# STM32-PROX.net
KiCad netlist of a schematic drawn in EAGLE
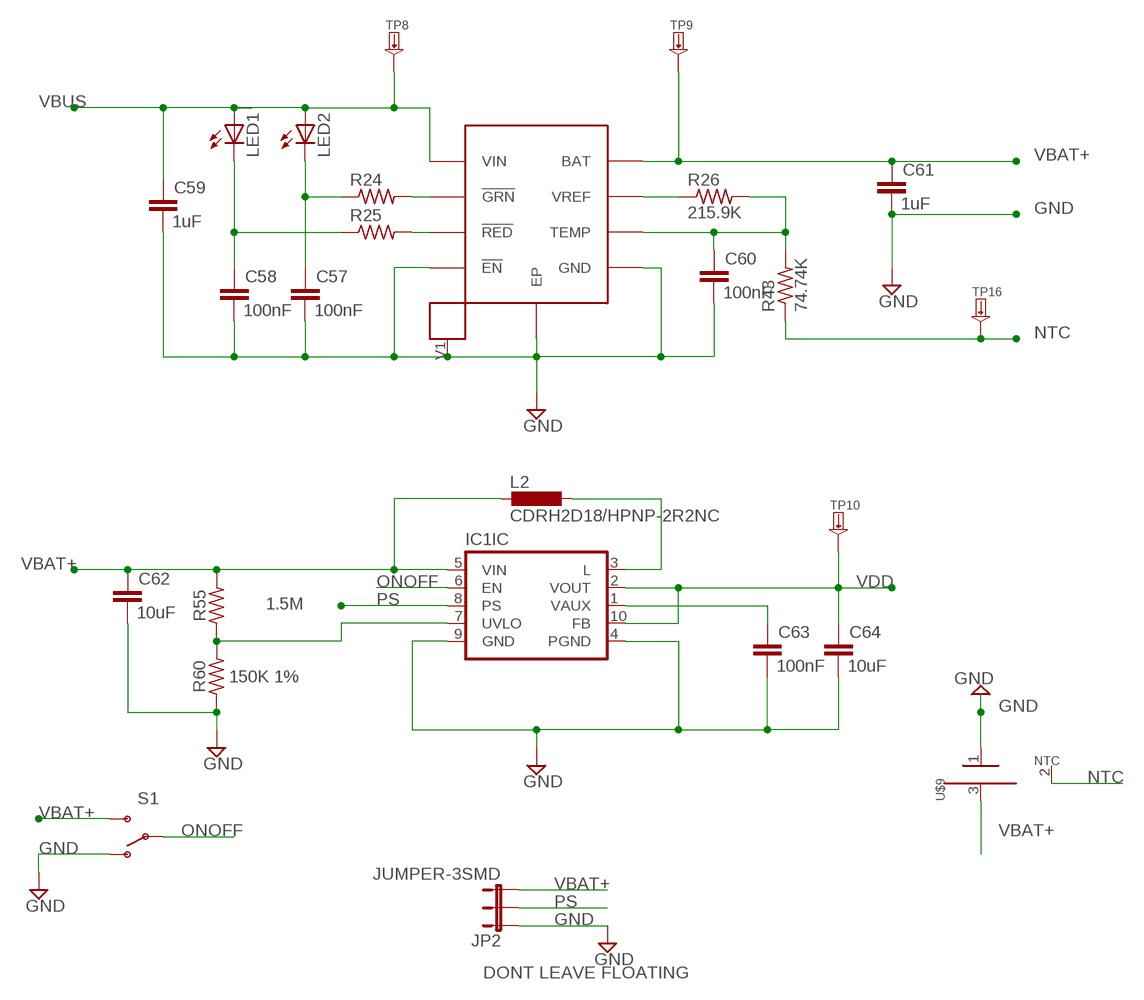
[diagram p0: schematic, sheet 1]
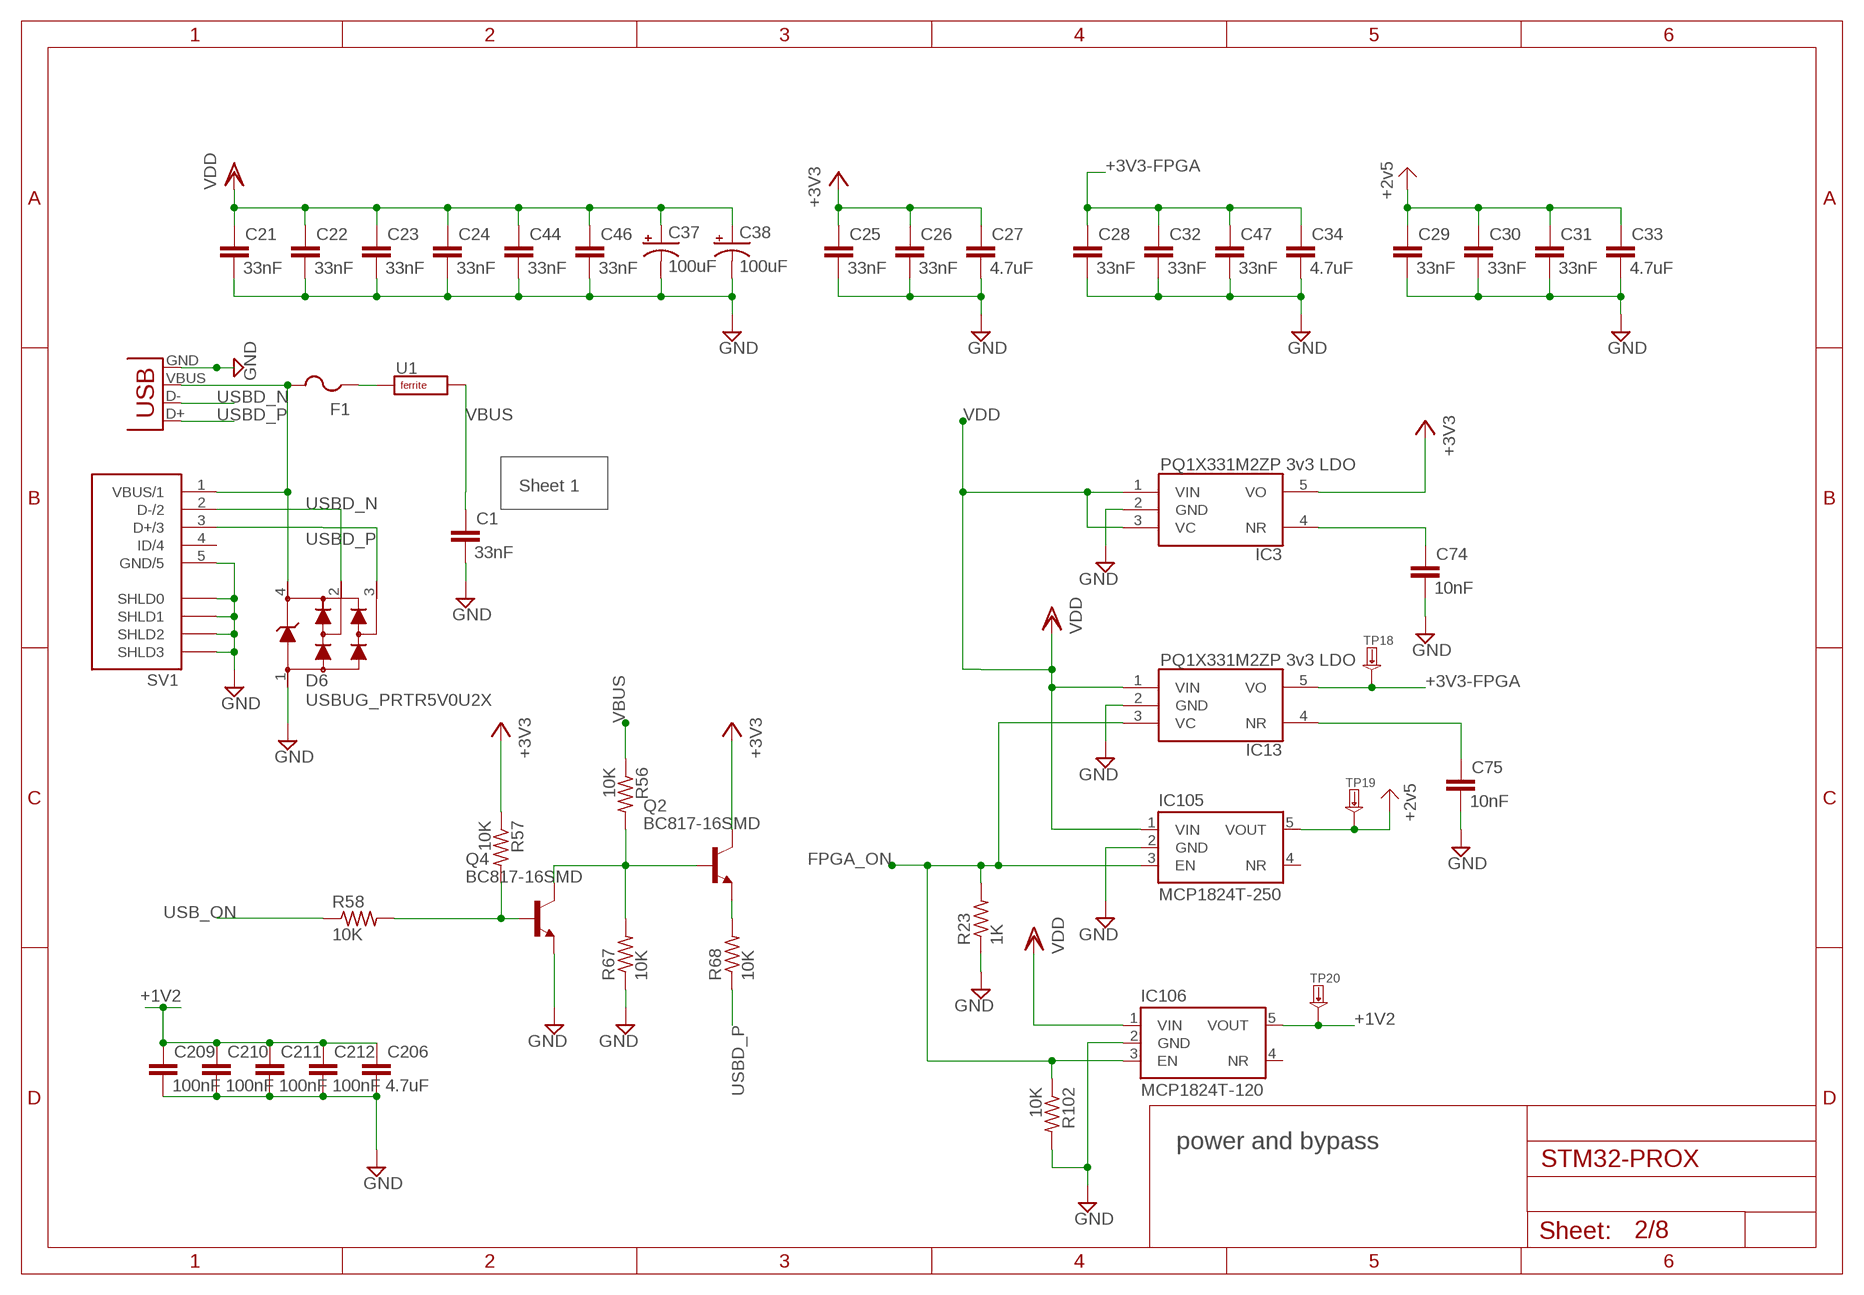
[diagram p1: schematic, sheet 2]
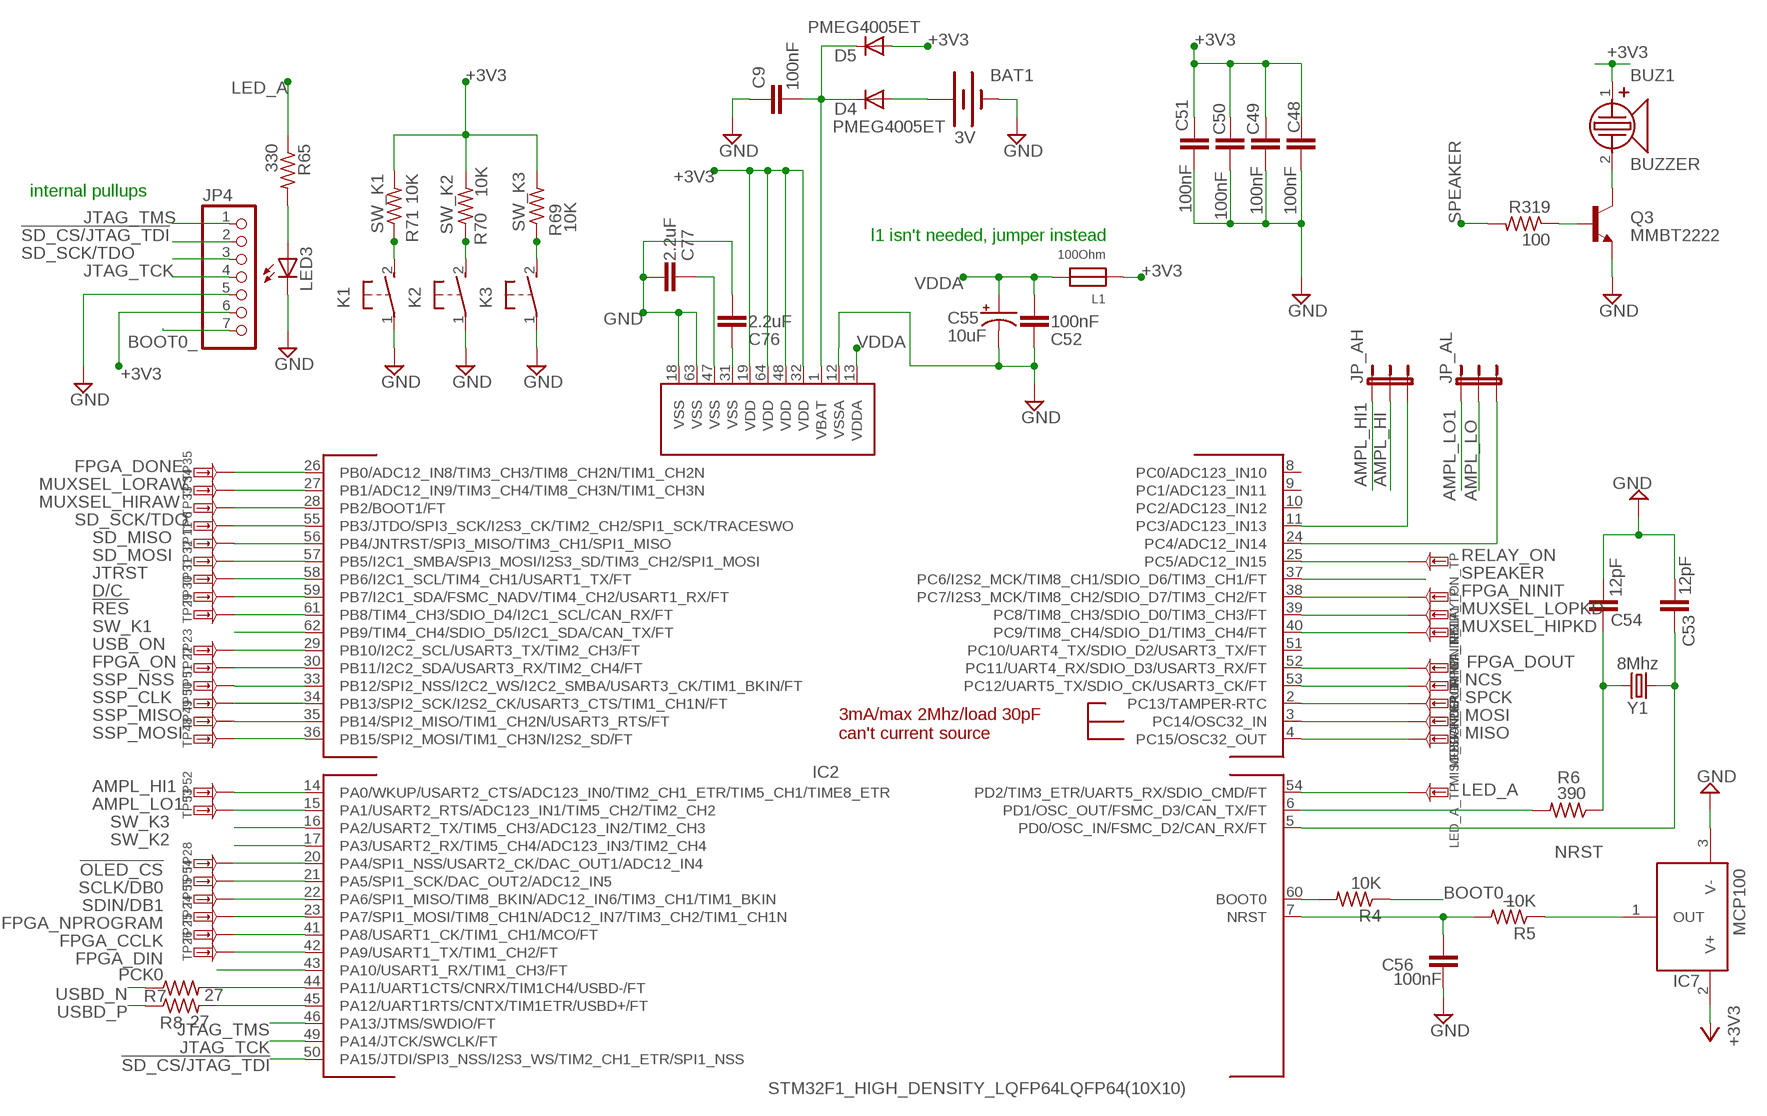
[diagram p2: schematic, sheet 3]
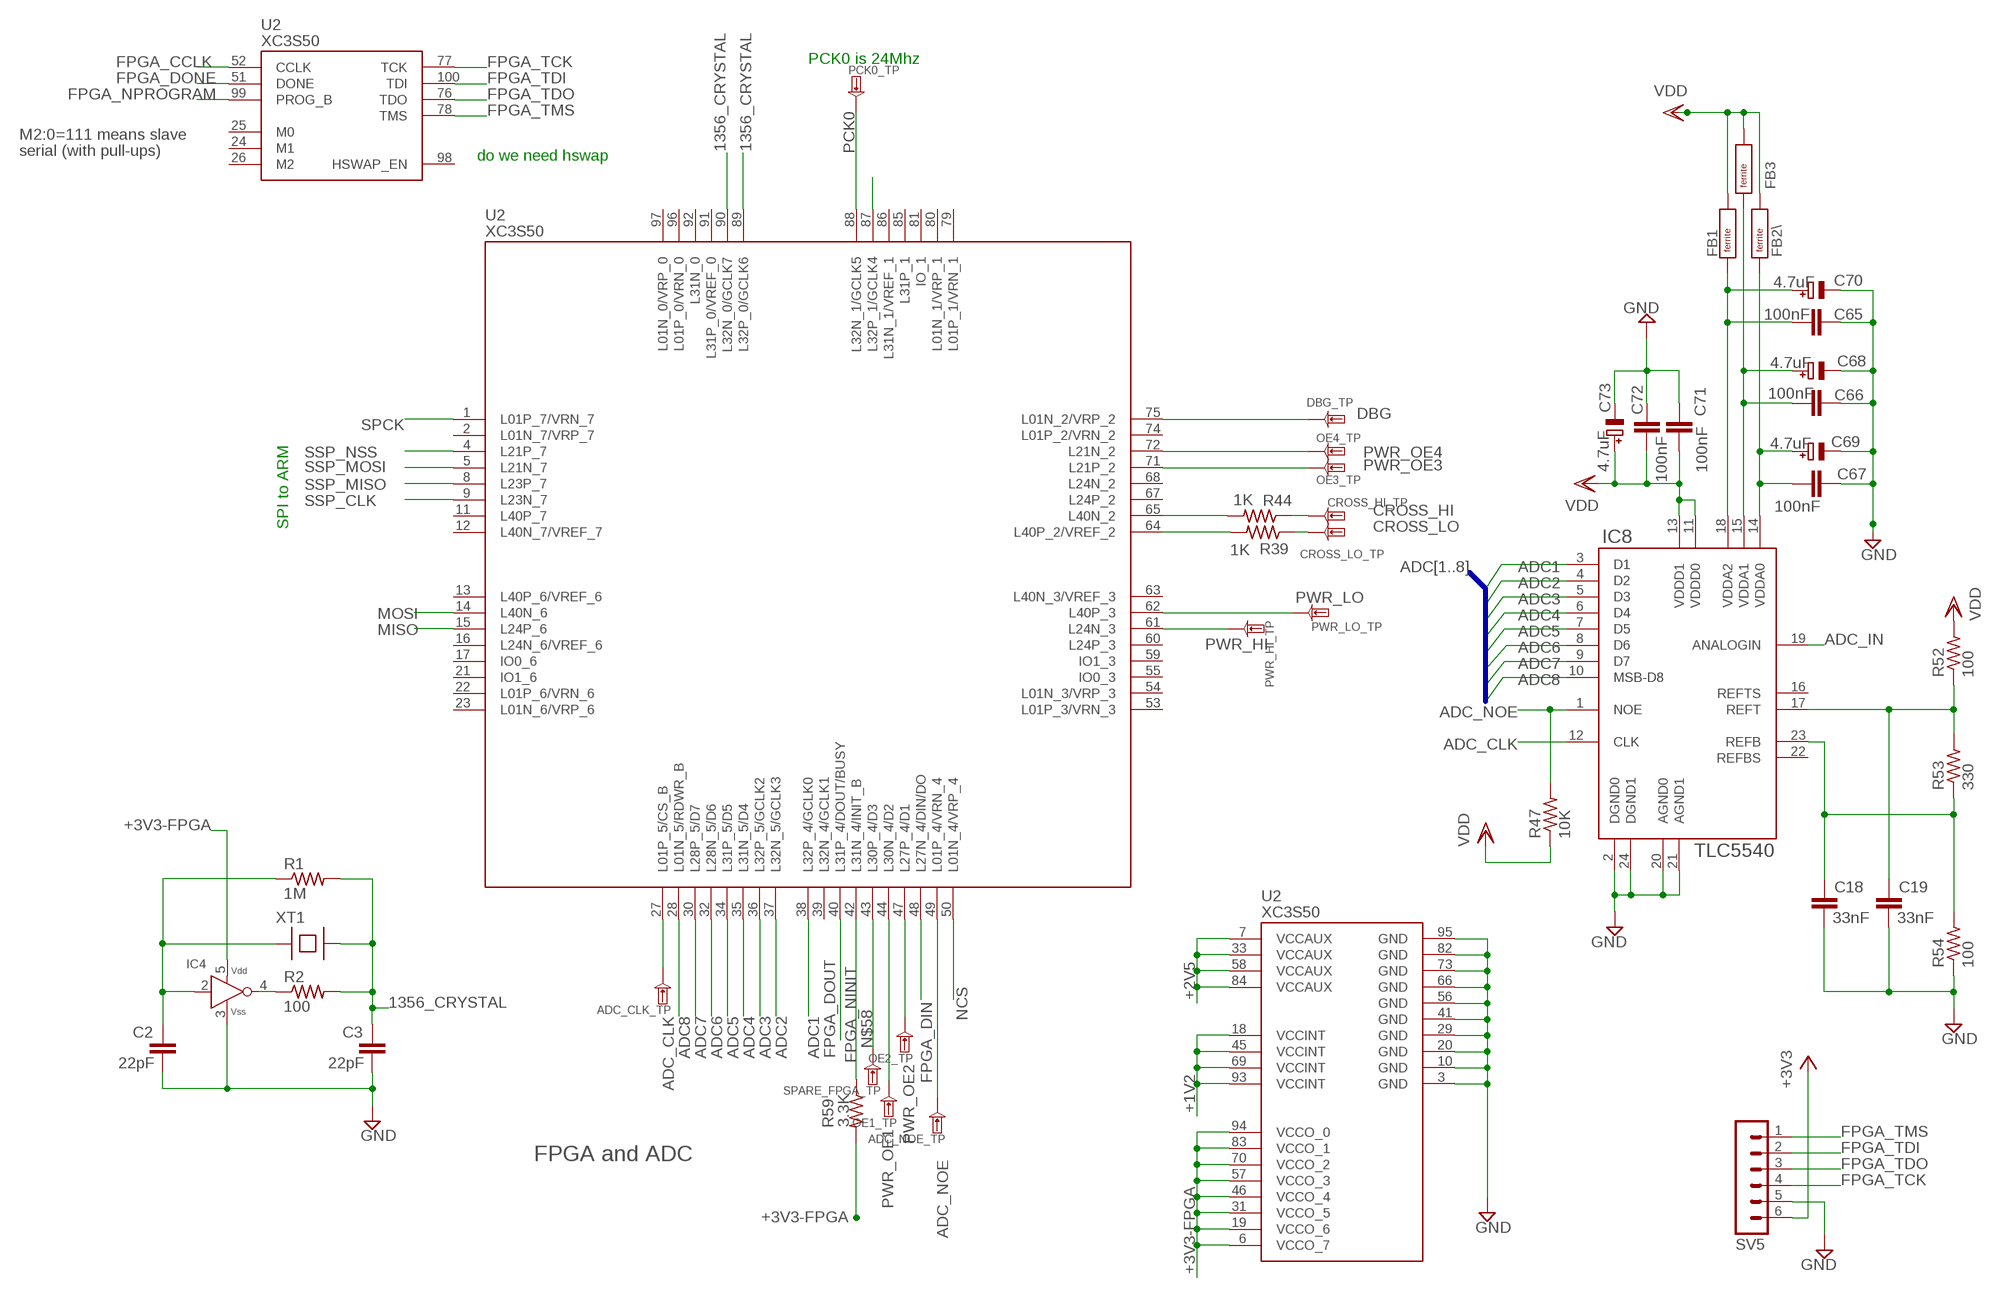
[diagram p3: schematic, sheet 4]
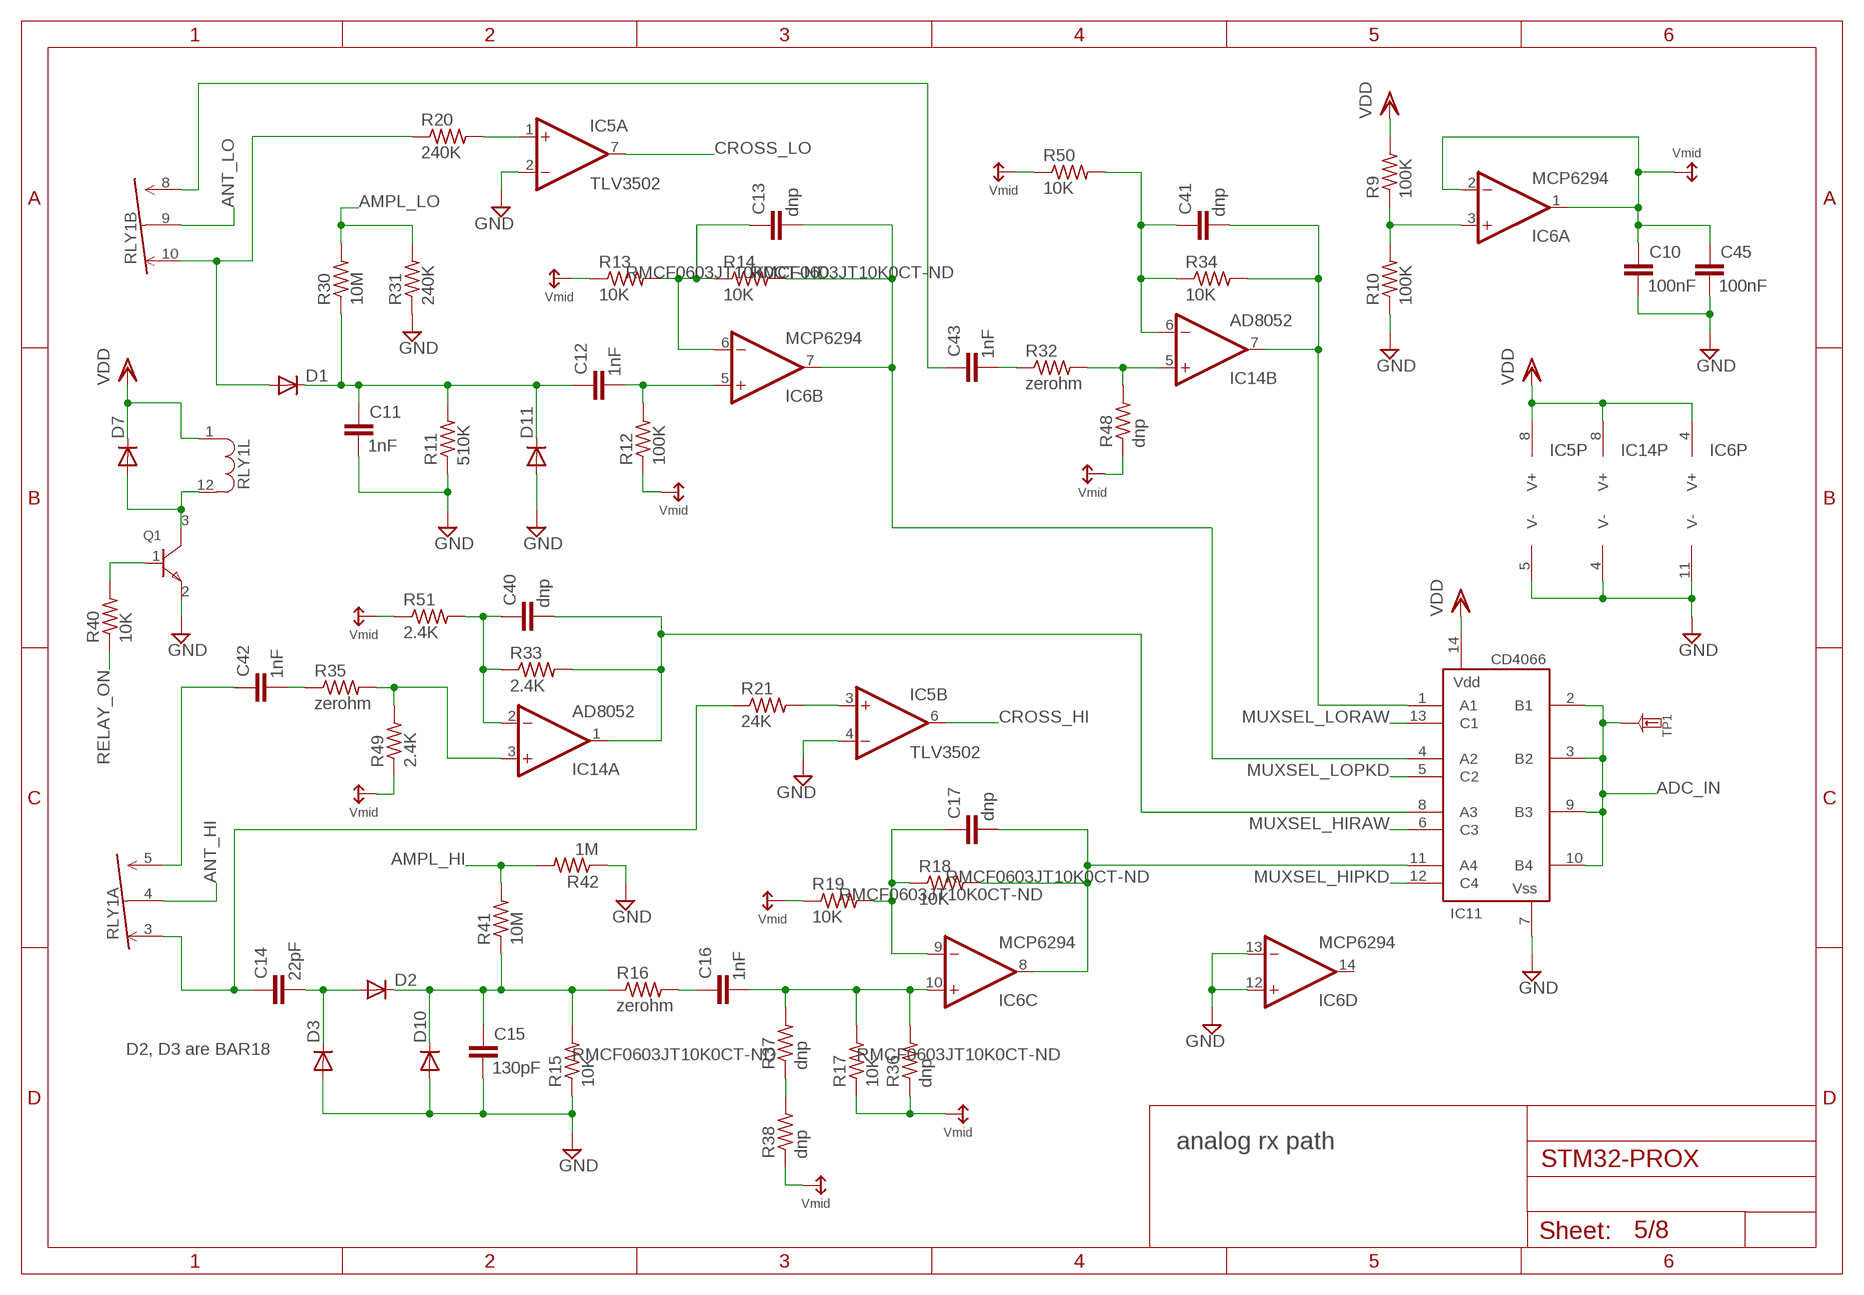
[diagram p4: schematic, sheet 5]
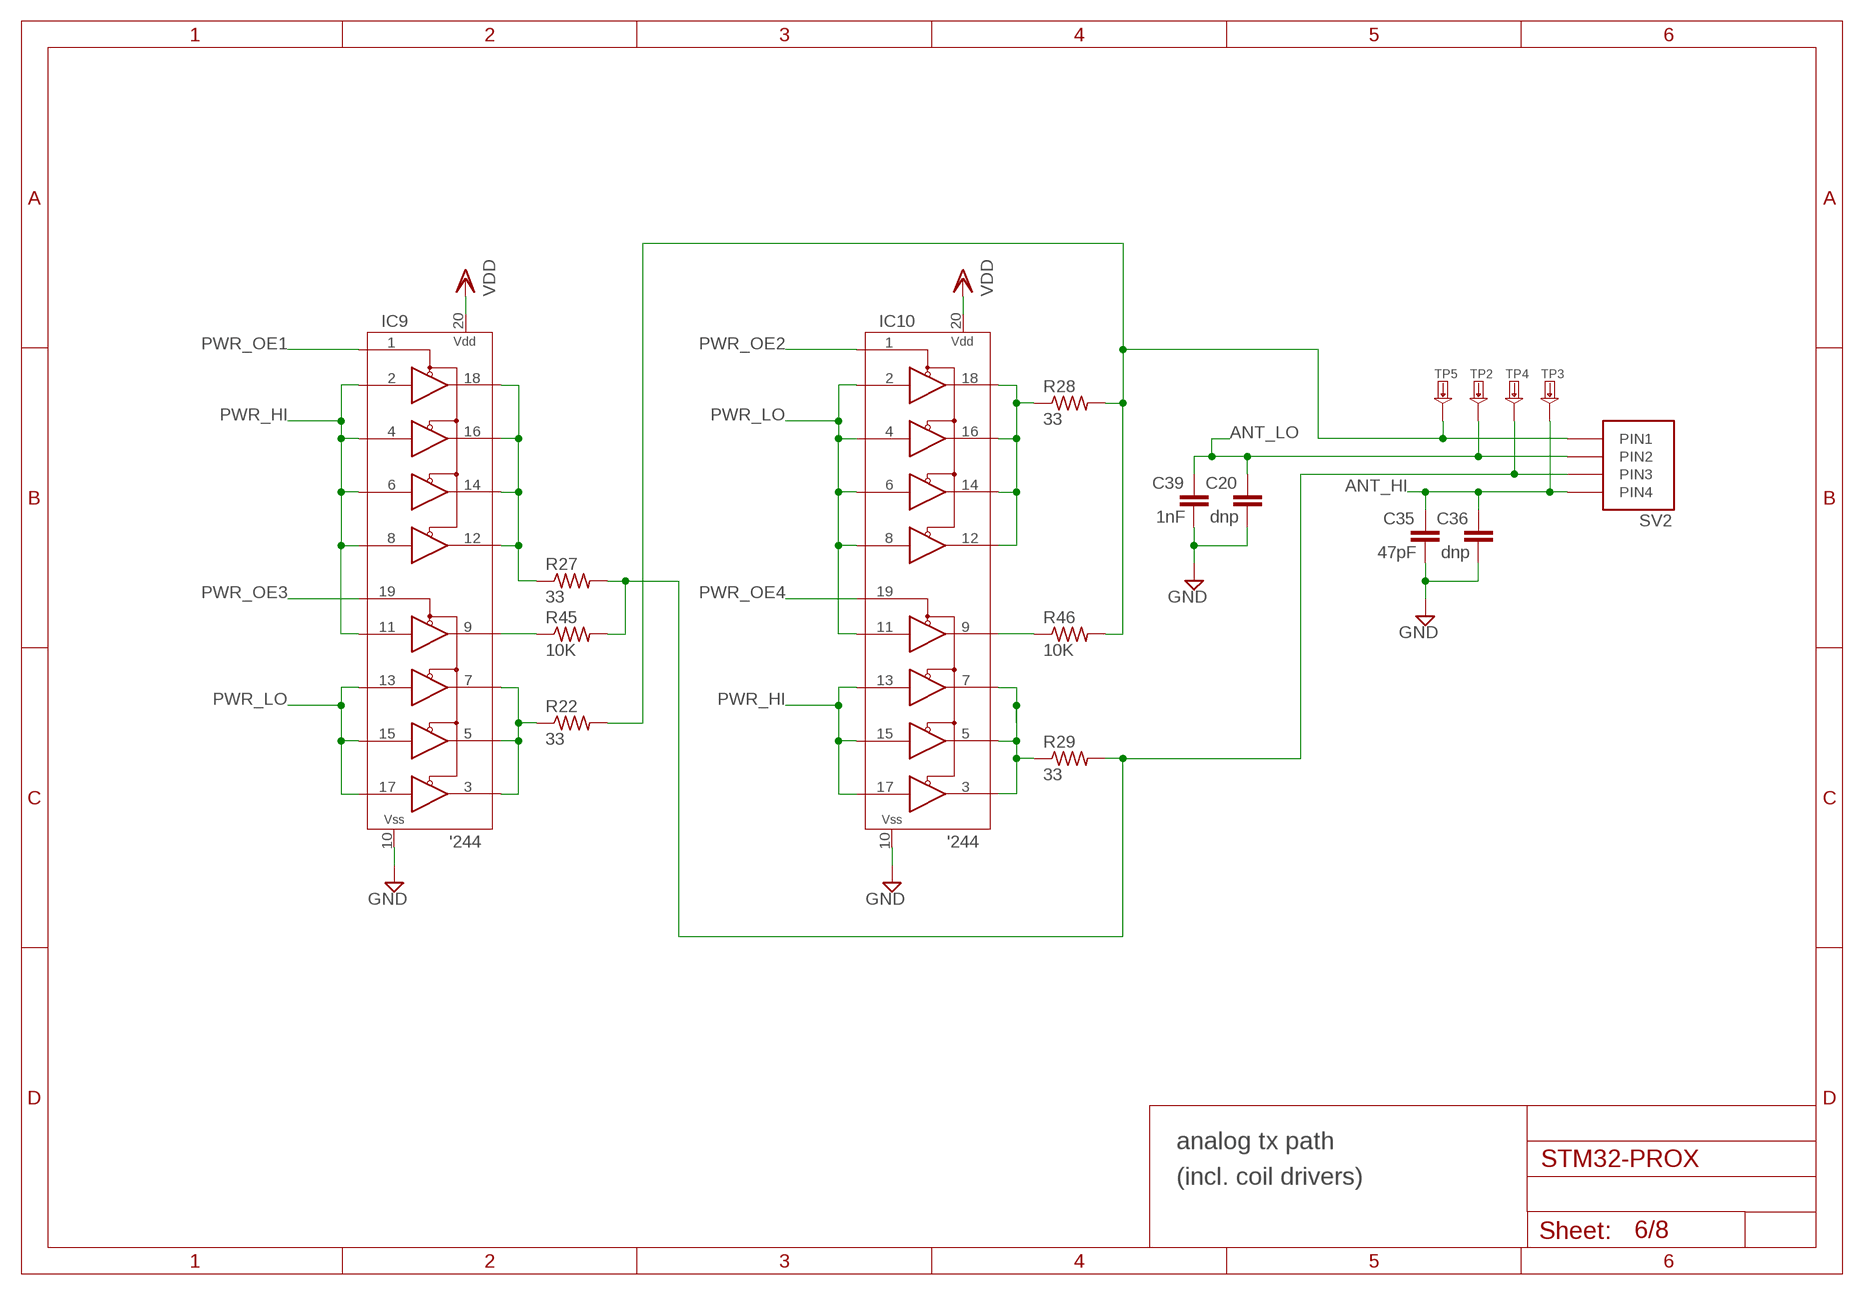
[diagram p5: schematic, sheet 6]
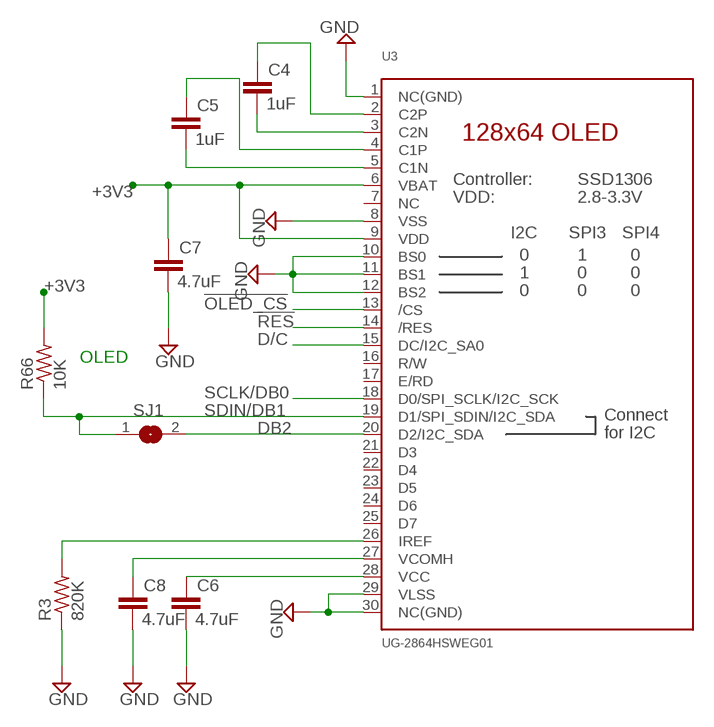
[diagram p6: schematic, sheet 7]
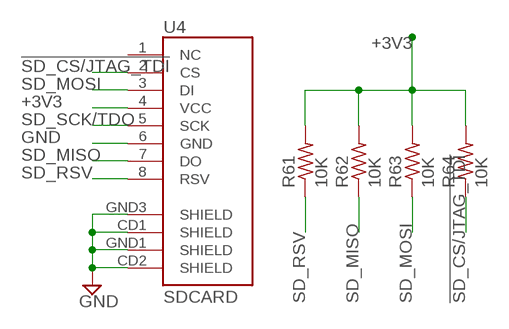
[diagram p7: schematic, sheet 8]

(export (version "E")
  (design (tool "Eeschema 10.0.6"))
  (components
    (comp (ref "BAT1")
      (value "3V")
      (footprint "eagle-import:NSL_SPARKFUN_BATTCON_12MM")
      (fields (field (name "MPN") "BK-885-TR"))
      (libsource (lib "eagle-import") (part "NSL_SPARKFUN_BATTERY12MM"))
    )
    (comp (ref "BUZ1")
      (value "BUZZER")
      (footprint "eagle-import:BUZZER")
      (fields (field (name "MF") "CCV-084B16"))
      (libsource (lib "eagle-import") (part "BUZZER"))
    )
    (comp (ref "C9")
      (value "100nF")
      (footprint "eagle-import:RLC_0603")
      (fields (field (name "MPN") "CL21F104ZBCNNNC"))
      (libsource (lib "eagle-import") (part "CAPACITORRLC_0603"))
    )
    (comp (ref "C48")
      (value "100nF")
      (footprint "eagle-import:RLC_0603")
      (fields (field (name "MPN") "CL21F104ZBCNNNC"))
      (libsource (lib "eagle-import") (part "CAPACITORRLC_0603"))
    )
    (comp (ref "C49")
      (value "100nF")
      (footprint "eagle-import:RLC_0603")
      (fields (field (name "MPN") "CL21F104ZBCNNNC"))
      (libsource (lib "eagle-import") (part "CAPACITORRLC_0603"))
    )
    (comp (ref "C50")
      (value "100nF")
      (footprint "eagle-import:RLC_0603")
      (fields (field (name "MPN") "CL21F104ZBCNNNC"))
      (libsource (lib "eagle-import") (part "CAPACITORRLC_0603"))
    )
    (comp (ref "C51")
      (value "100nF")
      (footprint "eagle-import:RLC_0603")
      (fields (field (name "MPN") "CL21F104ZBCNNNC"))
      (libsource (lib "eagle-import") (part "CAPACITORRLC_0603"))
    )
    (comp (ref "C52")
      (value "100nF")
      (footprint "eagle-import:RLC_0603")
      (fields (field (name "MPN") "CL21F104ZBCNNNC"))
      (libsource (lib "eagle-import") (part "CAPACITORRLC_0603"))
    )
    (comp (ref "C53")
      (value "12pF")
      (footprint "eagle-import:RLC_0603")
      (fields (field (name "MPN") "CL21C120JBANNNC"))
      (libsource (lib "eagle-import") (part "CAPACITORRLC_0603"))
    )
    (comp (ref "C54")
      (value "12pF")
      (footprint "eagle-import:RLC_0603")
      (fields (field (name "MPN") "CL21C120JBANNNC"))
      (libsource (lib "eagle-import") (part "CAPACITORRLC_0603"))
    )
    (comp (ref "C55")
      (value "10uF")
      (footprint "eagle-import:EIA3216-KIT")
      (fields (field (name "MF") "TAJA106M006RNJ"))
      (libsource (lib "eagle-import") (part "CAP_POL1206-KIT"))
    )
    (comp (ref "C56")
      (value "100nF")
      (footprint "eagle-import:RLC_0603")
      (fields (field (name "MPN") "CL21F104ZBCNNNC"))
      (libsource (lib "eagle-import") (part "CAPACITORRLC_0603"))
    )
    (comp (ref "C76")
      (value "2.2uF")
      (footprint "eagle-import:RLC_0603")
      (fields (field (name "MPN") "CL21F104ZBCNNNC"))
      (libsource (lib "eagle-import") (part "CAPACITORRLC_0603"))
    )
    (comp (ref "C77")
      (value "2.2uF")
      (footprint "eagle-import:RLC_0603")
      (fields (field (name "MPN") "CL21F104ZBCNNNC"))
      (libsource (lib "eagle-import") (part "CAPACITORRLC_0603"))
    )
    (comp (ref "D4")
      (value "PMEG4005ET")
      (footprint "eagle-import:SOT23-3")
      (fields (field (name "MPN") "PMEG4005ET,215"))
      (libsource (lib "eagle-import") (part "DIODESOT23"))
    )
    (comp (ref "D5")
      (value "PMEG4005ET")
      (footprint "eagle-import:SOT23-3")
      (fields (field (name "MPN") "PMEG4005ET,215"))
      (libsource (lib "eagle-import") (part "DIODESOT23"))
    )
    (comp (ref "FPGA_DOUT_TP")
      (value "TESTPAD")
      (footprint "eagle-import:SMD-TESTPOINT")
      (libsource (lib "eagle-import") (part "TESTPAD"))
    )
    (comp (ref "FPGA_NINIT_TP")
      (value "TESTPAD")
      (footprint "eagle-import:SMD-TESTPOINT")
      (libsource (lib "eagle-import") (part "TESTPAD"))
    )
    (comp (ref "FPGA_NINIT_TP1")
      (value "TESTPAD")
      (footprint "eagle-import:SMD-TESTPOINT")
      (libsource (lib "eagle-import") (part "TESTPAD"))
    )
    (comp (ref "FPGA_NINIT_TP2")
      (value "TESTPAD")
      (footprint "eagle-import:SMD-TESTPOINT")
      (libsource (lib "eagle-import") (part "TESTPAD"))
    )
    (comp (ref "IC2")
      (value "STM32F1_HIGH_DENSITY_LQFP64LQFP64(10X10)")
      (footprint "eagle-import:LQFP64A_PACKAGE")
      (libsource (lib "eagle-import") (part "STM32F1_HIGH_DENSITY_LQFP64LQFP64(10X10)"))
    )
    (comp (ref "IC7")
      (value "MCP100")
      (footprint "eagle-import:SOT23-3LEAD")
      (fields (field (name "MPN") "MCP100T-270I/TT"))
      (libsource (lib "eagle-import") (part "MCP100"))
    )
    (comp (ref "JP4")
      (value "HEADER-1X7ROUND")
      (footprint "eagle-import:1X07_ROUND")
      (libsource (lib "eagle-import") (part "HEADER-1X7ROUND"))
    )
    (comp (ref "JP_AH")
      (value "JUMPER-3SMD")
      (footprint "eagle-import:SJ_3")
      (libsource (lib "eagle-import") (part "JUMPER-3SMD"))
    )
    (comp (ref "JP_AL")
      (value "JUMPER-3SMD")
      (footprint "eagle-import:SJ_3")
      (libsource (lib "eagle-import") (part "JUMPER-3SMD"))
    )
    (comp (ref "K1")
      (value "5-XX")
      (footprint "eagle-import:B3F-5XX")
      (fields (field (name "MF") "PTS635SL50 LFS"))
      (libsource (lib "eagle-import") (part "5-XX"))
    )
    (comp (ref "K2")
      (value "5-XX")
      (footprint "eagle-import:B3F-5XX")
      (fields (field (name "MF") "PTS635SL50 LFS"))
      (libsource (lib "eagle-import") (part "5-XX"))
    )
    (comp (ref "K3")
      (value "5-XX")
      (footprint "eagle-import:B3F-5XX")
      (fields (field (name "MF") "PTS635SL50 LFS"))
      (libsource (lib "eagle-import") (part "5-XX"))
    )
    (comp (ref "L1")
      (value "100Ohm")
      (footprint "eagle-import:0603")
      (fields (field (name "MPN") "NONE"))
      (libsource (lib "eagle-import") (part "FERRITE1"))
    )
    (comp (ref "LED3")
      (value "LED_LEDSML0603")
      (footprint "eagle-import:LED_SML0603")
      (fields (field (name "MF") "LY Q976-P1S2-36"))
      (libsource (lib "eagle-import") (part "LED_LEDSML0603"))
    )
    (comp (ref "LED_A_TP")
      (value "TESTPAD")
      (footprint "eagle-import:SMD-TESTPOINT")
      (libsource (lib "eagle-import") (part "TESTPAD"))
    )
    (comp (ref "MISO_TP")
      (value "TESTPAD")
      (footprint "eagle-import:SMD-TESTPOINT")
      (libsource (lib "eagle-import") (part "TESTPAD"))
    )
    (comp (ref "MOSI_TP")
      (value "TESTPAD")
      (footprint "eagle-import:SMD-TESTPOINT")
      (libsource (lib "eagle-import") (part "TESTPAD"))
    )
    (comp (ref "NCS_TP")
      (value "TESTPAD")
      (footprint "eagle-import:SMD-TESTPOINT")
      (libsource (lib "eagle-import") (part "TESTPAD"))
    )
    (comp (ref "Q3")
      (value "MMBT2222")
      (footprint "eagle-import:SOT-23-3")
      (fields (field (name "MPN") "MMBT2222A-7-F"))
      (libsource (lib "eagle-import") (part "TRANSISTOR_NPNSOT23"))
    )
    (comp (ref "R4")
      (value "10K")
      (footprint "eagle-import:RLC_0603@1")
      (fields (field (name "DIGIKEY") "RMCF0603JT10K0CT-ND") (field (name "MPN") "RMCF0603JT10K0"))
      (libsource (lib "eagle-import") (part "RESISTORRLC_0603"))
    )
    (comp (ref "R5")
      (value "10K")
      (footprint "eagle-import:RLC_0603@1")
      (fields (field (name "DIGIKEY") "RMCF0603JT10K0CT-ND") (field (name "MPN") "RMCF0603JT10K0"))
      (libsource (lib "eagle-import") (part "RESISTORRLC_0603"))
    )
    (comp (ref "R6")
      (value "390")
      (footprint "eagle-import:RLC_0603@1")
      (fields (field (name "MPN") "RMCF0603JT390R"))
      (libsource (lib "eagle-import") (part "RESISTORRLC_0603"))
    )
    (comp (ref "R7")
      (value "27")
      (footprint "eagle-import:RLC_0603@1")
      (fields (field (name "MPN") "RMCF0603JT27R0"))
      (libsource (lib "eagle-import") (part "RESISTORRLC_0603"))
    )
    (comp (ref "R8")
      (value "27")
      (footprint "eagle-import:RLC_0603@1")
      (fields (field (name "MPN") "RMCF0603JT27R0"))
      (libsource (lib "eagle-import") (part "RESISTORRLC_0603"))
    )
    (comp (ref "R65")
      (value "330")
      (footprint "eagle-import:RLC_0603@1")
      (fields (field (name "MPN") "RMCF0603JT330R"))
      (libsource (lib "eagle-import") (part "RESISTORRLC_0603"))
    )
    (comp (ref "R69")
      (value "10K")
      (footprint "eagle-import:RLC_0603@1")
      (fields (field (name "MPN") "RMCF0603JT10K0"))
      (libsource (lib "eagle-import") (part "RESISTORRLC_0603"))
    )
    (comp (ref "R70")
      (value "10K")
      (footprint "eagle-import:RLC_0603@1")
      (fields (field (name "MPN") "RMCF0603JT10K0"))
      (libsource (lib "eagle-import") (part "RESISTORRLC_0603"))
    )
    (comp (ref "R71")
      (value "10K")
      (footprint "eagle-import:RLC_0603@1")
      (fields (field (name "MPN") "RMCF0603JT10K0"))
      (libsource (lib "eagle-import") (part "RESISTORRLC_0603"))
    )
    (comp (ref "R319")
      (value "100")
      (footprint "eagle-import:RLC_0603@1")
      (fields (field (name "MPN") "RMCF0603JT100R"))
      (libsource (lib "eagle-import") (part "RESISTORRLC_0603"))
    )
    (comp (ref "RELAY_ON_TP")
      (value "TESTPAD")
      (footprint "eagle-import:SMD-TESTPOINT")
      (libsource (lib "eagle-import") (part "TESTPAD"))
    )
    (comp (ref "SPCK_TP")
      (value "TESTPAD")
      (footprint "eagle-import:SMD-TESTPOINT")
      (libsource (lib "eagle-import") (part "TESTPAD"))
    )
    (comp (ref "TP6")
      (value "TESTPAD")
      (footprint "eagle-import:SMD-TESTPOINT")
      (libsource (lib "eagle-import") (part "TESTPAD"))
    )
    (comp (ref "TP11")
      (value "TESTPAD")
      (footprint "eagle-import:SMD-TESTPOINT")
      (libsource (lib "eagle-import") (part "TESTPAD"))
    )
    (comp (ref "TP22")
      (value "TESTPAD")
      (footprint "eagle-import:SMD-TESTPOINT")
      (libsource (lib "eagle-import") (part "TESTPAD"))
    )
    (comp (ref "TP23")
      (value "TESTPAD")
      (footprint "eagle-import:SMD-TESTPOINT")
      (libsource (lib "eagle-import") (part "TESTPAD"))
    )
    (comp (ref "TP24")
      (value "TESTPAD")
      (footprint "eagle-import:SMD-TESTPOINT")
      (libsource (lib "eagle-import") (part "TESTPAD"))
    )
    (comp (ref "TP25")
      (value "TESTPAD")
      (footprint "eagle-import:SMD-TESTPOINT")
      (libsource (lib "eagle-import") (part "TESTPAD"))
    )
    (comp (ref "TP26")
      (value "TESTPAD")
      (footprint "eagle-import:SMD-TESTPOINT")
      (libsource (lib "eagle-import") (part "TESTPAD"))
    )
    (comp (ref "TP28")
      (value "TESTPAD")
      (footprint "eagle-import:SMD-TESTPOINT")
      (libsource (lib "eagle-import") (part "TESTPAD"))
    )
    (comp (ref "TP29")
      (value "TESTPAD")
      (footprint "eagle-import:SMD-TESTPOINT")
      (libsource (lib "eagle-import") (part "TESTPAD"))
    )
    (comp (ref "TP30")
      (value "TESTPAD")
      (footprint "eagle-import:SMD-TESTPOINT")
      (libsource (lib "eagle-import") (part "TESTPAD"))
    )
    (comp (ref "TP31")
      (value "TESTPAD")
      (footprint "eagle-import:SMD-TESTPOINT")
      (libsource (lib "eagle-import") (part "TESTPAD"))
    )
    (comp (ref "TP32")
      (value "TESTPAD")
      (footprint "eagle-import:SMD-TESTPOINT")
      (libsource (lib "eagle-import") (part "TESTPAD"))
    )
    (comp (ref "TP33")
      (value "TESTPAD")
      (footprint "eagle-import:SMD-TESTPOINT")
      (libsource (lib "eagle-import") (part "TESTPAD"))
    )
    (comp (ref "TP34")
      (value "TESTPAD")
      (footprint "eagle-import:SMD-TESTPOINT")
      (libsource (lib "eagle-import") (part "TESTPAD"))
    )
    (comp (ref "TP35")
      (value "TESTPAD")
      (footprint "eagle-import:SMD-TESTPOINT")
      (libsource (lib "eagle-import") (part "TESTPAD"))
    )
    (comp (ref "TP48")
      (value "TESTPAD")
      (footprint "eagle-import:SMD-TESTPOINT")
      (libsource (lib "eagle-import") (part "TESTPAD"))
    )
    (comp (ref "TP49")
      (value "TESTPAD")
      (footprint "eagle-import:SMD-TESTPOINT")
      (libsource (lib "eagle-import") (part "TESTPAD"))
    )
    (comp (ref "TP50")
      (value "TESTPAD")
      (footprint "eagle-import:SMD-TESTPOINT")
      (libsource (lib "eagle-import") (part "TESTPAD"))
    )
    (comp (ref "TP51")
      (value "TESTPAD")
      (footprint "eagle-import:SMD-TESTPOINT")
      (libsource (lib "eagle-import") (part "TESTPAD"))
    )
    (comp (ref "TP52")
      (value "TESTPAD")
      (footprint "eagle-import:SMD-TESTPOINT")
      (libsource (lib "eagle-import") (part "TESTPAD"))
    )
    (comp (ref "TP53")
      (value "TESTPAD")
      (footprint "eagle-import:SMD-TESTPOINT")
      (libsource (lib "eagle-import") (part "TESTPAD"))
    )
    (comp (ref "TP54")
      (value "TESTPAD")
      (footprint "eagle-import:SMD-TESTPOINT")
      (libsource (lib "eagle-import") (part "TESTPAD"))
    )
    (comp (ref "TP55")
      (value "TESTPAD")
      (footprint "eagle-import:SMD-TESTPOINT")
      (libsource (lib "eagle-import") (part "TESTPAD"))
    )
    (comp (ref "Y1")
      (value "8Mhz")
      (footprint "eagle-import:CRYSTAL-TXC-7A")
      (fields (field (name "MPN") "7A-8.000MAAE-T"))
      (libsource (lib "eagle-import") (part "CRYSTALTXC-7A"))
    )
    (comp (ref "C20")
      (value "dnp")
      (footprint "eagle-import:RLC_0603")
      (libsource (lib "eagle-import") (part "CAPACITORRLC_0603"))
    )
    (comp (ref "C35")
      (value "47pF")
      (footprint "eagle-import:RLC_0603")
      (fields (field (name "MPN") "CL10C470JB8NNNC"))
      (libsource (lib "eagle-import") (part "CAPACITORRLC_0603"))
    )
    (comp (ref "C36")
      (value "dnp")
      (footprint "eagle-import:RLC_0603")
      (libsource (lib "eagle-import") (part "CAPACITORRLC_0603"))
    )
    (comp (ref "C39")
      (value "1nF")
      (footprint "eagle-import:RLC_0603")
      (fields (field (name "MPN") "GRM188R71H102KA01D"))
      (libsource (lib "eagle-import") (part "CAPACITORRLC_0603"))
    )
    (comp (ref "IC9")
      (value "74XX244")
      (footprint "eagle-import:TSSOP-20")
      (fields (field (name "MF") "74AC244TTR"))
      (libsource (lib "eagle-import") (part "74XX244-OCTAL-TRISTATE-BUFFERS"))
    )
    (comp (ref "IC10")
      (value "74XX244")
      (footprint "eagle-import:TSSOP-20")
      (fields (field (name "MF") "74AC244TTR"))
      (libsource (lib "eagle-import") (part "74XX244-OCTAL-TRISTATE-BUFFERS"))
    )
    (comp (ref "R22")
      (value "33")
      (footprint "eagle-import:RLC_0603@1")
      (fields (field (name "MPN") "RC0603JR-0733RL"))
      (libsource (lib "eagle-import") (part "RESISTORRLC_0603"))
    )
    (comp (ref "R27")
      (value "33")
      (footprint "eagle-import:RLC_0603@1")
      (fields (field (name "MPN") "RC0603JR-0733RL"))
      (libsource (lib "eagle-import") (part "RESISTORRLC_0603"))
    )
    (comp (ref "R28")
      (value "33")
      (footprint "eagle-import:RLC_0603@1")
      (fields (field (name "MPN") "RC0603JR-0733RL"))
      (libsource (lib "eagle-import") (part "RESISTORRLC_0603"))
    )
    (comp (ref "R29")
      (value "33")
      (footprint "eagle-import:RLC_0603@1")
      (fields (field (name "MPN") "RC0603JR-0733RL"))
      (libsource (lib "eagle-import") (part "RESISTORRLC_0603"))
    )
    (comp (ref "R45")
      (value "10K")
      (footprint "eagle-import:RLC_0603@1")
      (fields (field (name "MPN") "RMCF0603JT10K0"))
      (libsource (lib "eagle-import") (part "RESISTORRLC_0603"))
    )
    (comp (ref "R46")
      (value "10K")
      (footprint "eagle-import:RLC_0603@1")
      (fields (field (name "MPN") "RMCF0603JT10K0"))
      (libsource (lib "eagle-import") (part "RESISTORRLC_0603"))
    )
    (comp (ref "SV2")
      (value "HIROSE-MQ172-4POS")
      (footprint "eagle-import:HIROSE-MQ172-4POS")
      (fields (field (name "MF") "MQ172X-4PA(66)"))
      (libsource (lib "eagle-import") (part "HIROSE-MQ172-4POS"))
    )
    (comp (ref "TP2")
      (value "TESTPADKEYSTONE-SMD")
      (footprint "eagle-import:KEYSTONE-SMD-TESTPOINT-5015")
      (libsource (lib "eagle-import") (part "TESTPADKEYSTONE-SMD"))
    )
    (comp (ref "TP3")
      (value "TESTPADKEYSTONE-SMD")
      (footprint "eagle-import:KEYSTONE-SMD-TESTPOINT-5015")
      (libsource (lib "eagle-import") (part "TESTPADKEYSTONE-SMD"))
    )
    (comp (ref "TP4")
      (value "TESTPADKEYSTONE-SMD")
      (footprint "eagle-import:KEYSTONE-SMD-TESTPOINT-5015")
      (libsource (lib "eagle-import") (part "TESTPADKEYSTONE-SMD"))
    )
    (comp (ref "TP5")
      (value "TESTPADKEYSTONE-SMD")
      (footprint "eagle-import:KEYSTONE-SMD-TESTPOINT-5015")
      (libsource (lib "eagle-import") (part "TESTPADKEYSTONE-SMD"))
    )
    (comp (ref "C57")
      (value "100nF")
      (footprint "eagle-import:RLC_0603")
      (fields (field (name "MPN") "CL10B104KO8NNNC"))
      (libsource (lib "eagle-import") (part "CAPACITORRLC_0603"))
    )
    (comp (ref "C58")
      (value "100nF")
      (footprint "eagle-import:RLC_0603")
      (fields (field (name "MPN") "CL10B104KO8NNNC"))
      (libsource (lib "eagle-import") (part "CAPACITORRLC_0603"))
    )
    (comp (ref "C59")
      (value "1uF")
      (footprint "eagle-import:RLC_0603")
      (fields (field (name "MPN") "CC0603ZRY5V7BB105"))
      (libsource (lib "eagle-import") (part "CAPACITORRLC_0603"))
    )
    (comp (ref "C60")
      (value "100nF")
      (footprint "eagle-import:RLC_0603")
      (fields (field (name "MPN") "CL10B104KO8NNNC"))
      (libsource (lib "eagle-import") (part "CAPACITORRLC_0603"))
    )
    (comp (ref "C61")
      (value "1uF")
      (footprint "eagle-import:RLC_0603")
      (fields (field (name "MPN") "CC0603ZRY5V7BB105"))
      (libsource (lib "eagle-import") (part "CAPACITORRLC_0603"))
    )
    (comp (ref "C62")
      (value "10uF")
      (footprint "eagle-import:RLC_0603")
      (fields (field (name "MPN") "C1608X5R1C106M080AB"))
      (libsource (lib "eagle-import") (part "CAPACITORRLC_0603"))
    )
    (comp (ref "C63")
      (value "100nF")
      (footprint "eagle-import:RLC_0603")
      (fields (field (name "MPN") "CL10B104KO8NNNC"))
      (libsource (lib "eagle-import") (part "CAPACITORRLC_0603"))
    )
    (comp (ref "C64")
      (value "10uF")
      (footprint "eagle-import:RLC_0603")
      (fields (field (name "MPN") "C1608X5R1C106M080AB"))
      (libsource (lib "eagle-import") (part "CAPACITORRLC_0603"))
    )
    (comp (ref "IC1")
      (value "IC_TPS6120XQFN10")
      (footprint "eagle-import:QFN-10")
      (fields (field (name "MPN") "TPS61202DRCT"))
      (libsource (lib "eagle-import") (part "IC_TPS6120XQFN10"))
    )
    (comp (ref "JP2")
      (value "JUMPER-3SMD")
      (footprint "eagle-import:SJ_3")
      (fields (field (name "MPN") "NONE"))
      (libsource (lib "eagle-import") (part "JUMPER-3SMD"))
    )
    (comp (ref "L2")
      (value "CDRH2D18/HPNP-2R2NC")
      (footprint "eagle-import:CDRH2D18")
      (libsource (lib "eagle-import") (part "CDRH2D18"))
    )
    (comp (ref "LED1")
      (value "LED_LEDSML0603")
      (footprint "eagle-import:LED_SML0603")
      (fields (field (name "MF") "LG Q971-KN-1"))
      (libsource (lib "eagle-import") (part "LED_LEDSML0603"))
    )
    (comp (ref "LED2")
      (value "LED_LEDSML0603")
      (footprint "eagle-import:LED_SML0603")
      (fields (field (name "MF") "LS Q971-KN-1"))
      (libsource (lib "eagle-import") (part "LED_LEDSML0603"))
    )
    (comp (ref "R24")
      (value "RESISTORRLC_0603")
      (footprint "eagle-import:RLC_0603@1")
      (libsource (lib "eagle-import") (part "RESISTORRLC_0603"))
    )
    (comp (ref "R25")
      (value "RESISTORRLC_0603")
      (footprint "eagle-import:RLC_0603@1")
      (libsource (lib "eagle-import") (part "RESISTORRLC_0603"))
    )
    (comp (ref "R26")
      (value "215.9K")
      (footprint "eagle-import:RLC_0603@1")
      (fields (field (name "MPN") "CRCW0603215KFKEA"))
      (libsource (lib "eagle-import") (part "RESISTORRLC_0603"))
    )
    (comp (ref "R43")
      (value "74.74K")
      (footprint "eagle-import:RLC_0603@1")
      (fields (field (name "MPN") "RMCF0603JT75K0"))
      (libsource (lib "eagle-import") (part "RESISTORRLC_0603"))
    )
    (comp (ref "R55")
      (value "1.5M")
      (footprint "eagle-import:RLC_0603@1")
      (fields (field (name "MPN") "ESR03EZPJ155") (field (name "TOLERANCE") "5%"))
      (libsource (lib "eagle-import") (part "RESISTORRLC_0603"))
    )
    (comp (ref "R60")
      (value "150K 1%")
      (footprint "eagle-import:RLC_0603@1")
      (fields (field (name "MPN") "ESR03EZPF1503") (field (name "TOLERANCE") "1%"))
      (libsource (lib "eagle-import") (part "RESISTORRLC_0603"))
    )
    (comp (ref "S1")
      (value "SWITCH-SPDT-SMD-A")
      (footprint "eagle-import:SWITCH-SPST-SMD-A")
      (libsource (lib "eagle-import") (part "SWITCH-SPDT-SMD-A"))
    )
    (comp (ref "TP8")
      (value "TESTPAD0.7MM-ROUND-DRILLED")
      (footprint "eagle-import:TESTPAD-PTH-0.7MM")
      (fields (field (name "MPN") "NONE"))
      (libsource (lib "eagle-import") (part "TESTPAD0.7MM-ROUND-DRILLED"))
    )
    (comp (ref "TP9")
      (value "TESTPADKEYSTONE-SMD")
      (footprint "eagle-import:--MERGED_KEYSTONE-SMD-TESTPOINT-5015")
      (fields (field (name "MPN") "NONE"))
      (libsource (lib "eagle-import") (part "--MERGED_TESTPADKEYSTONE-SMD"))
    )
    (comp (ref "TP10")
      (value "TESTPADKEYSTONE-SMD")
      (footprint "eagle-import:--MERGED_KEYSTONE-SMD-TESTPOINT-5015")
      (fields (field (name "MPN") "NONE"))
      (libsource (lib "eagle-import") (part "--MERGED_TESTPADKEYSTONE-SMD"))
    )
    (comp (ref "TP16")
      (value "TESTPAD")
      (footprint "eagle-import:SMD-TESTPOINT")
      (libsource (lib "eagle-import") (part "TESTPAD"))
    )
    (comp (ref "U$7")
      (value "MC34674")
      (footprint "eagle-import:UDFN-EP")
      (fields
        (field (name "DIGIKEY") "MC34674AEPR2TR-ND")
        (field (name "MF") "MC34674AEPR2")
        (field (name "MOUSER") "841-MC34674AEPR2")
        (field (name "MPN") "MC34674AEPR2")
        (field (name "OC_NEWARK") "unknown")
        (field (name "PARTNO") "MC34674AEPR2")
      )
      (libsource (lib "eagle-import") (part "MC34674"))
    )
    (comp (ref "U$9")
      (value "BATT")
      (footprint "eagle-import:BATT")
      (fields (field (name "MF") "MC34674AEPR2"))
      (libsource (lib "eagle-import") (part "BATT"))
    )
    (comp (ref "ADC_CLK_TP")
      (value "TESTPAD")
      (footprint "eagle-import:SMD-TESTPOINT")
      (libsource (lib "eagle-import") (part "TESTPAD"))
    )
    (comp (ref "ADC_NOE_TP")
      (value "TESTPAD")
      (footprint "eagle-import:SMD-TESTPOINT")
      (libsource (lib "eagle-import") (part "TESTPAD"))
    )
    (comp (ref "C2")
      (value "22pF")
      (footprint "eagle-import:RLC_0603")
      (fields (field (name "MPN") "C1608C0G1H220J080AA"))
      (libsource (lib "eagle-import") (part "CAPACITORRLC_0603"))
    )
    (comp (ref "C3")
      (value "22pF")
      (footprint "eagle-import:RLC_0603")
      (fields (field (name "MPN") "C1608C0G1H220J080AA"))
      (libsource (lib "eagle-import") (part "CAPACITORRLC_0603"))
    )
    (comp (ref "C18")
      (value "33nF")
      (footprint "eagle-import:RLC_0603")
      (fields (field (name "MPN") "CC0603KRX7R9BB333"))
      (libsource (lib "eagle-import") (part "CAPACITORRLC_0603"))
    )
    (comp (ref "C19")
      (value "33nF")
      (footprint "eagle-import:RLC_0603")
      (fields (field (name "MPN") "CC0603KRX7R9BB333"))
      (libsource (lib "eagle-import") (part "CAPACITORRLC_0603"))
    )
    (comp (ref "C65")
      (value "100nF")
      (footprint "eagle-import:RLC_0603")
      (fields (field (name "MPN") "CC0603KRX7R9BB333"))
      (libsource (lib "eagle-import") (part "CAPACITORRLC_0603"))
    )
    (comp (ref "C66")
      (value "100nF")
      (footprint "eagle-import:RLC_0603")
      (fields (field (name "MPN") "CC0603KRX7R9BB333"))
      (libsource (lib "eagle-import") (part "CAPACITORRLC_0603"))
    )
    (comp (ref "C67")
      (value "100nF")
      (footprint "eagle-import:RLC_0603")
      (fields (field (name "MPN") "CC0603KRX7R9BB333"))
      (libsource (lib "eagle-import") (part "CAPACITORRLC_0603"))
    )
    (comp (ref "C68")
      (value "4.7uF")
      (footprint "eagle-import:EIA3216-18_A-R")
      (libsource (lib "eagle-import") (part "CAP_TANTALUMA/3216_REFLOW"))
    )
    (comp (ref "C69")
      (value "4.7uF")
      (footprint "eagle-import:EIA3216-18_A-R")
      (libsource (lib "eagle-import") (part "CAP_TANTALUMA/3216_REFLOW"))
    )
    (comp (ref "C70")
      (value "4.7uF")
      (footprint "eagle-import:EIA3216-18_A-R")
      (libsource (lib "eagle-import") (part "CAP_TANTALUMA/3216_REFLOW"))
    )
    (comp (ref "C71")
      (value "100nF")
      (footprint "eagle-import:RLC_0603")
      (fields (field (name "MPN") "CC0603KRX7R9BB333"))
      (libsource (lib "eagle-import") (part "CAPACITORRLC_0603"))
    )
    (comp (ref "C72")
      (value "100nF")
      (footprint "eagle-import:RLC_0603")
      (fields (field (name "MPN") "CC0603KRX7R9BB333"))
      (libsource (lib "eagle-import") (part "CAPACITORRLC_0603"))
    )
    (comp (ref "C73")
      (value "4.7uF")
      (footprint "eagle-import:EIA3216-18_A-R")
      (libsource (lib "eagle-import") (part "CAP_TANTALUMA/3216_REFLOW"))
    )
    (comp (ref "CROSS_HI_TP")
      (value "TESTPAD")
      (footprint "eagle-import:SMD-TESTPOINT")
      (libsource (lib "eagle-import") (part "TESTPAD"))
    )
    (comp (ref "CROSS_LO_TP")
      (value "TESTPAD")
      (footprint "eagle-import:SMD-TESTPOINT")
      (libsource (lib "eagle-import") (part "TESTPAD"))
    )
    (comp (ref "DBG_TP")
      (value "TESTPAD")
      (footprint "eagle-import:SMD-TESTPOINT")
      (libsource (lib "eagle-import") (part "TESTPAD"))
    )
    (comp (ref "FB1")
      (value "FERRITERLC_0603")
      (footprint "eagle-import:RLC_0603@1")
      (fields (field (name "PARTNO") "CIM10J601NC"))
      (libsource (lib "eagle-import") (part "FERRITERLC_0603"))
    )
    (comp (ref "FB2\\")
      (value "FERRITERLC_0603")
      (footprint "eagle-import:RLC_0603@1")
      (fields (field (name "PARTNO") "CIM10J601NC"))
      (libsource (lib "eagle-import") (part "FERRITERLC_0603"))
    )
    (comp (ref "FB3")
      (value "FERRITERLC_0603")
      (footprint "eagle-import:RLC_0603@1")
      (fields (field (name "PARTNO") "CIM10J601NC"))
      (libsource (lib "eagle-import") (part "FERRITERLC_0603"))
    )
    (comp (ref "IC4")
      (value "HCU-INVERTER")
      (footprint "eagle-import:SMV-5")
      (fields (field (name "MF") "NC7SZ04M5X"))
      (libsource (lib "eagle-import") (part "HCU-INVERTER"))
    )
    (comp (ref "IC8")
      (value "TLC5540")
      (footprint "eagle-import:TSSOP-24")
      (fields (field (name "MPN") "TLC5540IPW"))
      (libsource (lib "eagle-import") (part "TLC5540"))
    )
    (comp (ref "OE1_TP")
      (value "TESTPAD")
      (footprint "eagle-import:SMD-TESTPOINT")
      (libsource (lib "eagle-import") (part "TESTPAD"))
    )
    (comp (ref "OE2_TP")
      (value "TESTPAD")
      (footprint "eagle-import:SMD-TESTPOINT")
      (libsource (lib "eagle-import") (part "TESTPAD"))
    )
    (comp (ref "OE3_TP")
      (value "TESTPAD")
      (footprint "eagle-import:SMD-TESTPOINT")
      (libsource (lib "eagle-import") (part "TESTPAD"))
    )
    (comp (ref "OE4_TP")
      (value "TESTPAD")
      (footprint "eagle-import:SMD-TESTPOINT")
      (libsource (lib "eagle-import") (part "TESTPAD"))
    )
    (comp (ref "PCK0_TP")
      (value "TESTPAD")
      (footprint "eagle-import:SMD-TESTPOINT")
      (libsource (lib "eagle-import") (part "TESTPAD"))
    )
    (comp (ref "PWR_HI_TP")
      (value "TESTPAD")
      (footprint "eagle-import:SMD-TESTPOINT")
      (libsource (lib "eagle-import") (part "TESTPAD"))
    )
    (comp (ref "PWR_LO_TP")
      (value "TESTPAD")
      (footprint "eagle-import:SMD-TESTPOINT")
      (libsource (lib "eagle-import") (part "TESTPAD"))
    )
    (comp (ref "R1")
      (value "1M")
      (footprint "eagle-import:RLC_0603@1")
      (fields (field (name "MPN") "RC0603JR-071ML"))
      (libsource (lib "eagle-import") (part "RESISTORRLC_0603"))
    )
    (comp (ref "R2")
      (value "100")
      (footprint "eagle-import:RLC_0603@1")
      (fields (field (name "MPN") "RMCF0603JT100R"))
      (libsource (lib "eagle-import") (part "RESISTORRLC_0603"))
    )
    (comp (ref "R39")
      (value "1K")
      (footprint "eagle-import:RLC_0603@1")
      (fields (field (name "MPN") "RMCF0603JT1K00"))
      (libsource (lib "eagle-import") (part "RESISTORRLC_0603"))
    )
    (comp (ref "R44")
      (value "1K")
      (footprint "eagle-import:RLC_0603@1")
      (fields (field (name "MPN") "RMCF0603JT1K00"))
      (libsource (lib "eagle-import") (part "RESISTORRLC_0603"))
    )
    (comp (ref "R47")
      (value "10K")
      (footprint "eagle-import:RLC_0603@1")
      (fields (field (name "MPN") "RMCF0603JT10K0"))
      (libsource (lib "eagle-import") (part "RESISTORRLC_0603"))
    )
    (comp (ref "R52")
      (value "100")
      (footprint "eagle-import:RLC_0603@1")
      (fields (field (name "MPN") "RMCF0603JT100R"))
      (libsource (lib "eagle-import") (part "RESISTORRLC_0603"))
    )
    (comp (ref "R53")
      (value "330")
      (footprint "eagle-import:RLC_0603@1")
      (fields (field (name "MPN") "RMCF0603JT330R"))
      (libsource (lib "eagle-import") (part "RESISTORRLC_0603"))
    )
    (comp (ref "R54")
      (value "100")
      (footprint "eagle-import:RLC_0603@1")
      (fields (field (name "MPN") "RMCF0603JT100R"))
      (libsource (lib "eagle-import") (part "RESISTORRLC_0603"))
    )
    (comp (ref "R59")
      (value "3.3K")
      (footprint "eagle-import:RLC_0603@1")
      (fields (field (name "MPN") "RMCF0603JT3K30"))
      (libsource (lib "eagle-import") (part "RESISTORRLC_0603"))
    )
    (comp (ref "SPARE_FPGA_TP")
      (value "TESTPAD")
      (footprint "eagle-import:SMD-TESTPOINT")
      (libsource (lib "eagle-import") (part "TESTPAD"))
    )
    (comp (ref "SV5")
      (value "HEADER-MALE-6X1")
      (footprint "eagle-import:HEADER-MALE-6X1-0.100-UNKEYED")
      (libsource (lib "eagle-import") (part "HEADER-MALE-6X1"))
    )
    (comp (ref "U2")
      (value "XC3S50")
      (footprint "eagle-import:VQ100")
      (fields
        (field (name "MPN") "XC3S50-5VQ100C (not on bom)")
        (field (name "OC_NEWARK") "unknown")
        (field (name "PARTNO") "XC3S50-5VQ100C (not on bom)")
      )
      (libsource (lib "eagle-import") (part "XC3S50"))
    )
    (comp (ref "XT1")
      (value "XTAL-SMD-CITIZEN-CS10")
      (footprint "eagle-import:XTAL-SMD-CITIZEN-CS10")
      (fields (field (name "MF") "ABM3-13.560MHZ-B2-T"))
      (libsource (lib "eagle-import") (part "XTAL-SMD-CITIZEN-CS10"))
    )
    (comp (ref "C1")
      (value "33nF")
      (footprint "eagle-import:RLC_0603")
      (fields (field (name "MPN") "CC0603KRX7R9BB333"))
      (libsource (lib "eagle-import") (part "CAPACITORRLC_0603"))
    )
    (comp (ref "C21")
      (value "33nF")
      (footprint "eagle-import:RLC_0603")
      (fields (field (name "MPN") "CC0603KRX7R9BB333"))
      (libsource (lib "eagle-import") (part "CAPACITORRLC_0603"))
    )
    (comp (ref "C22")
      (value "33nF")
      (footprint "eagle-import:RLC_0603")
      (fields (field (name "MPN") "CC0603KRX7R9BB333"))
      (libsource (lib "eagle-import") (part "CAPACITORRLC_0603"))
    )
    (comp (ref "C23")
      (value "33nF")
      (footprint "eagle-import:RLC_0603")
      (fields (field (name "MPN") "CC0603KRX7R9BB333"))
      (libsource (lib "eagle-import") (part "CAPACITORRLC_0603"))
    )
    (comp (ref "C24")
      (value "33nF")
      (footprint "eagle-import:RLC_0603")
      (fields (field (name "MPN") "CC0603KRX7R9BB333"))
      (libsource (lib "eagle-import") (part "CAPACITORRLC_0603"))
    )
    (comp (ref "C25")
      (value "33nF")
      (footprint "eagle-import:RLC_0603")
      (fields (field (name "MPN") "CC0603KRX7R9BB333"))
      (libsource (lib "eagle-import") (part "CAPACITORRLC_0603"))
    )
    (comp (ref "C26")
      (value "33nF")
      (footprint "eagle-import:RLC_0603")
      (fields (field (name "MPN") "CC0603KRX7R9BB333"))
      (libsource (lib "eagle-import") (part "CAPACITORRLC_0603"))
    )
    (comp (ref "C27")
      (value "4.7uF")
      (footprint "eagle-import:RLC_1210")
      (fields (field (name "MPN") "CL32B475KOINNNE"))
      (libsource (lib "eagle-import") (part "CAPACITOR1210"))
    )
    (comp (ref "C28")
      (value "33nF")
      (footprint "eagle-import:RLC_0603")
      (fields (field (name "MPN") "CC0603KRX7R9BB333"))
      (libsource (lib "eagle-import") (part "CAPACITORRLC_0603"))
    )
    (comp (ref "C29")
      (value "33nF")
      (footprint "eagle-import:RLC_0603")
      (fields (field (name "MPN") "CC0603KRX7R9BB333"))
      (libsource (lib "eagle-import") (part "CAPACITORRLC_0603"))
    )
    (comp (ref "C30")
      (value "33nF")
      (footprint "eagle-import:RLC_0603")
      (fields (field (name "MPN") "CC0603KRX7R9BB333"))
      (libsource (lib "eagle-import") (part "CAPACITORRLC_0603"))
    )
    (comp (ref "C31")
      (value "33nF")
      (footprint "eagle-import:RLC_0603")
      (fields (field (name "MPN") "CC0603KRX7R9BB333"))
      (libsource (lib "eagle-import") (part "CAPACITORRLC_0603"))
    )
    (comp (ref "C32")
      (value "33nF")
      (footprint "eagle-import:RLC_0603")
      (fields (field (name "MPN") "CC0603KRX7R9BB333"))
      (libsource (lib "eagle-import") (part "CAPACITORRLC_0603"))
    )
    (comp (ref "C33")
      (value "4.7uF")
      (footprint "eagle-import:RLC_1210")
      (fields (field (name "MPN") "CL32B475KOINNNE"))
      (libsource (lib "eagle-import") (part "CAPACITOR1210"))
    )
    (comp (ref "C34")
      (value "4.7uF")
      (footprint "eagle-import:RLC_1210")
      (fields (field (name "MPN") "CL32B475KOINNNE"))
      (libsource (lib "eagle-import") (part "CAPACITOR1210"))
    )
    (comp (ref "C37")
      (value "100uF")
      (footprint "eagle-import:D_7343-31R")
      (fields (field (name "MPN") "T491D107K010AT"))
      (libsource (lib "eagle-import") (part "CPOL-USD/7343-31R"))
    )
    (comp (ref "C38")
      (value "100uF")
      (footprint "eagle-import:D_7343-31R")
      (fields (field (name "MPN") "T491D107K010AT"))
      (libsource (lib "eagle-import") (part "CPOL-USD/7343-31R"))
    )
    (comp (ref "C44")
      (value "33nF")
      (footprint "eagle-import:RLC_0603")
      (fields (field (name "MPN") "CC0603KRX7R9BB333"))
      (libsource (lib "eagle-import") (part "CAPACITORRLC_0603"))
    )
    (comp (ref "C46")
      (value "33nF")
      (footprint "eagle-import:RLC_0603")
      (fields (field (name "MPN") "CC0603KRX7R9BB333"))
      (libsource (lib "eagle-import") (part "CAPACITORRLC_0603"))
    )
    (comp (ref "C47")
      (value "33nF")
      (footprint "eagle-import:RLC_0603")
      (fields (field (name "MPN") "CC0603KRX7R9BB333"))
      (libsource (lib "eagle-import") (part "CAPACITORRLC_0603"))
    )
    (comp (ref "C74")
      (value "10nF")
      (footprint "eagle-import:RLC_0603")
      (fields (field (name "MPN") "CC0603KRX7R9BB333"))
      (libsource (lib "eagle-import") (part "CAPACITORRLC_0603"))
    )
    (comp (ref "C75")
      (value "10nF")
      (footprint "eagle-import:RLC_0603")
      (fields (field (name "MPN") "CC0603KRX7R9BB333"))
      (libsource (lib "eagle-import") (part "CAPACITORRLC_0603"))
    )
    (comp (ref "C206")
      (value "4.7uF")
      (footprint "eagle-import:RLC_0603")
      (fields (field (name "MPN") "EMK107ABJ475KA-T"))
      (libsource (lib "eagle-import") (part "CAPACITORRLC_0603"))
    )
    (comp (ref "C209")
      (value "100nF")
      (footprint "eagle-import:RLC_0603")
      (fields (field (name "MPN") "CL10B104KO8NNNC"))
      (libsource (lib "eagle-import") (part "CAPACITORRLC_0603"))
    )
    (comp (ref "C210")
      (value "100nF")
      (footprint "eagle-import:RLC_0603")
      (fields (field (name "MPN") "CL10B104KO8NNNC"))
      (libsource (lib "eagle-import") (part "CAPACITORRLC_0603"))
    )
    (comp (ref "C211")
      (value "100nF")
      (footprint "eagle-import:RLC_0603")
      (fields (field (name "MPN") "CL10B104KO8NNNC"))
      (libsource (lib "eagle-import") (part "CAPACITORRLC_0603"))
    )
    (comp (ref "C212")
      (value "100nF")
      (footprint "eagle-import:RLC_0603")
      (fields (field (name "MPN") "CL10B104KO8NNNC"))
      (libsource (lib "eagle-import") (part "CAPACITORRLC_0603"))
    )
    (comp (ref "D6")
      (value "USBUG_PRTR5V0U2X")
      (footprint "eagle-import:USBUG_SOT143B")
      (libsource (lib "eagle-import") (part "USBUG_PRTR5V0U2X"))
    )
    (comp (ref "F1")
      (value "PTCFUSE-1812")
      (footprint "eagle-import:1812")
      (fields (field (name "MPN") "MICROSMD050F-2"))
      (libsource (lib "eagle-import") (part "PTCFUSE-1812"))
    )
    (comp (ref "IC3")
      (value "PQ1X331M2ZP-3V3-LDO-SOT-23-5")
      (footprint "eagle-import:SOT-23-5")
      (fields (field (name "MPN") "LP2985-33DBVR"))
      (libsource (lib "eagle-import") (part "PQ1X331M2ZP-3V3-LDO-SOT-23-5"))
    )
    (comp (ref "IC13")
      (value "PQ1X331M2ZP-3V3-LDO-SOT-23-5")
      (footprint "eagle-import:SOT-23-5")
      (fields (field (name "MPN") "LP2985-33DBVR"))
      (libsource (lib "eagle-import") (part "PQ1X331M2ZP-3V3-LDO-SOT-23-5"))
    )
    (comp (ref "IC105")
      (value "MCP1824T-250")
      (footprint "eagle-import:SOT-23-5")
      (fields (field (name "MPN") "MCP1824T-2502E/OT"))
      (libsource (lib "eagle-import") (part "TPS79925"))
    )
    (comp (ref "IC106")
      (value "MCP1824T-120")
      (footprint "eagle-import:SOT-23-5")
      (fields (field (name "MPN") "MCP1824T-1202E/OT"))
      (libsource (lib "eagle-import") (part "TPS79912"))
    )
    (comp (ref "Q2")
      (value "BC817-16SMD")
      (footprint "eagle-import:SOT23-BEC")
      (libsource (lib "eagle-import") (part "BC817SMD-16"))
    )
    (comp (ref "Q4")
      (value "BC817-16SMD")
      (footprint "eagle-import:SOT23-BEC")
      (libsource (lib "eagle-import") (part "BC817SMD-16"))
    )
    (comp (ref "R23")
      (value "1K")
      (footprint "eagle-import:RLC_0603@1")
      (fields (field (name "MPN") "RMCF0603JT1K00"))
      (libsource (lib "eagle-import") (part "RESISTORRLC_0603"))
    )
    (comp (ref "R56")
      (value "10K")
      (footprint "eagle-import:RLC_0603@1")
      (fields (field (name "MPN") "RMCF0603JT10K0"))
      (libsource (lib "eagle-import") (part "RESISTORRLC_0603"))
    )
    (comp (ref "R57")
      (value "10K")
      (footprint "eagle-import:RLC_0603@1")
      (fields (field (name "MPN") "RMCF0603JT10K0"))
      (libsource (lib "eagle-import") (part "RESISTORRLC_0603"))
    )
    (comp (ref "R58")
      (value "10K")
      (footprint "eagle-import:RLC_0603@1")
      (fields (field (name "MPN") "RMCF0603JT10K0"))
      (libsource (lib "eagle-import") (part "RESISTORRLC_0603"))
    )
    (comp (ref "R67")
      (value "10K")
      (footprint "eagle-import:RLC_0603@1")
      (fields (field (name "MPN") "RMCF0603JT10K0"))
      (libsource (lib "eagle-import") (part "RESISTORRLC_0603"))
    )
    (comp (ref "R68")
      (value "10K")
      (footprint "eagle-import:RLC_0603@1")
      (fields (field (name "MPN") "RMCF0603JT10K0"))
      (libsource (lib "eagle-import") (part "RESISTORRLC_0603"))
    )
    (comp (ref "R102")
      (value "10K")
      (footprint "eagle-import:RLC_0603@1")
      (fields (field (name "MPN") "RMCF0603JT10K0"))
      (libsource (lib "eagle-import") (part "RESISTORRLC_0603"))
    )
    (comp (ref "SV1")
      (value "USB-MINIB")
      (footprint "eagle-import:USB-MINIB-SMD")
      (libsource (lib "eagle-import") (part "USB-MINIB"))
    )
    (comp (ref "TP18")
      (value "TESTPAD")
      (footprint "eagle-import:SMD-TESTPOINT")
      (libsource (lib "eagle-import") (part "TESTPAD"))
    )
    (comp (ref "TP19")
      (value "TESTPAD")
      (footprint "eagle-import:SMD-TESTPOINT")
      (libsource (lib "eagle-import") (part "TESTPAD"))
    )
    (comp (ref "TP20")
      (value "TESTPAD")
      (footprint "eagle-import:SMD-TESTPOINT")
      (libsource (lib "eagle-import") (part "TESTPAD"))
    )
    (comp (ref "U1")
      (value "FERRITE0805")
      (footprint "eagle-import:RLC_0805")
      (fields (field (name "MF") "MPZ2012S300A"))
      (libsource (lib "eagle-import") (part "FERRITE0805"))
    )
    (comp (ref "USB-MICRO")
      (value "USB-MICROB")
      (footprint "eagle-import:USB-MICROB")
      (fields (field (name "MF") "1981568-1"))
      (libsource (lib "eagle-import") (part "USB-MICROB"))
    )
    (comp (ref "C10")
      (value "100nF")
      (footprint "eagle-import:RLC_0603")
      (fields (field (name "MPN") "CL10B104KO8NNNC"))
      (libsource (lib "eagle-import") (part "CAPACITORRLC_0603"))
    )
    (comp (ref "C11")
      (value "1nF")
      (footprint "eagle-import:RLC_0603")
      (fields (field (name "MPN") "GRM188R71H102KA01D"))
      (libsource (lib "eagle-import") (part "CAPACITORRLC_0603"))
    )
    (comp (ref "C12")
      (value "1nF")
      (footprint "eagle-import:RLC_0603")
      (fields (field (name "MPN") "GRM188R71H102KA01D"))
      (libsource (lib "eagle-import") (part "CAPACITORRLC_0603"))
    )
    (comp (ref "C13")
      (value "dnp")
      (footprint "eagle-import:RLC_0603")
      (libsource (lib "eagle-import") (part "CAPACITORRLC_0603"))
    )
    (comp (ref "C14")
      (value "22pF")
      (footprint "eagle-import:RLC_0603")
      (fields (field (name "MPN") "C1608C0G1H220J080AA"))
      (libsource (lib "eagle-import") (part "CAPACITORRLC_0603"))
    )
    (comp (ref "C15")
      (value "130pF")
      (footprint "eagle-import:RLC_0603")
      (fields (field (name "MPN") "GRM1885C1H131JA01D"))
      (libsource (lib "eagle-import") (part "CAPACITORRLC_0603"))
    )
    (comp (ref "C16")
      (value "1nF")
      (footprint "eagle-import:RLC_0603")
      (fields (field (name "MPN") "GRM188R71H102KA01D"))
      (libsource (lib "eagle-import") (part "CAPACITORRLC_0603"))
    )
    (comp (ref "C17")
      (value "dnp")
      (footprint "eagle-import:RLC_0603")
      (libsource (lib "eagle-import") (part "CAPACITORRLC_0603"))
    )
    (comp (ref "C40")
      (value "dnp")
      (footprint "eagle-import:RLC_0603")
      (libsource (lib "eagle-import") (part "CAPACITORRLC_0603"))
    )
    (comp (ref "C41")
      (value "dnp")
      (footprint "eagle-import:RLC_0603")
      (libsource (lib "eagle-import") (part "CAPACITORRLC_0603"))
    )
    (comp (ref "C42")
      (value "1nF")
      (footprint "eagle-import:RLC_0603")
      (fields (field (name "MPN") "GRM188R71H102KA01D"))
      (libsource (lib "eagle-import") (part "CAPACITORRLC_0603"))
    )
    (comp (ref "C43")
      (value "1nF")
      (footprint "eagle-import:RLC_0603")
      (fields (field (name "MPN") "GRM188R71H102KA01D"))
      (libsource (lib "eagle-import") (part "CAPACITORRLC_0603"))
    )
    (comp (ref "C45")
      (value "100nF")
      (footprint "eagle-import:RLC_0603")
      (fields (field (name "MPN") "CL10B104KO8NNNC"))
      (libsource (lib "eagle-import") (part "CAPACITORRLC_0603"))
    )
    (comp (ref "D1")
      (value "DIODE-SMD-SOT23")
      (footprint "eagle-import:SOT23-3LEAD")
      (fields (field (name "MF") "BAS 21 E6327"))
      (libsource (lib "eagle-import") (part "DIODE-SMD-SOT23"))
    )
    (comp (ref "D2")
      (value "DIODE-SMD-SOT23")
      (footprint "eagle-import:SOT23-3LEAD")
      (fields (field (name "MF") "BAS 21 E6327"))
      (libsource (lib "eagle-import") (part "DIODE-SMD-SOT23"))
    )
    (comp (ref "D3")
      (value "DIODE-SMD-SOT23")
      (footprint "eagle-import:SOT23-3LEAD")
      (fields (field (name "MF") "BAS 21 E6327"))
      (libsource (lib "eagle-import") (part "DIODE-SMD-SOT23"))
    )
    (comp (ref "D7")
      (value "DIODE-SMD-SOT23")
      (footprint "eagle-import:SOT23-3LEAD")
      (libsource (lib "eagle-import") (part "DIODE-SMD-SOT23"))
    )
    (comp (ref "D10")
      (value "DIODE-SMD-SOT23")
      (footprint "eagle-import:SOT23-3LEAD")
      (libsource (lib "eagle-import") (part "DIODE-SMD-SOT23"))
    )
    (comp (ref "D11")
      (value "DIODE-SMD-SOT23")
      (footprint "eagle-import:SOT23-3LEAD")
      (libsource (lib "eagle-import") (part "DIODE-SMD-SOT23"))
    )
    (comp (ref "IC5")
      (value "TLV3502")
      (footprint "eagle-import:SOT-23-8-OR-MSOP-8")
      (fields
        (field (name "DIGIKEY") "296-18147-1-ND")
        (field (name "MPN") "TLV3502AIDCNT")
        (field (name "OC_NEWARK") "unknown")
        (field (name "PARTNO") "TLV3502AIDCNT")
      )
      (libsource (lib "eagle-import") (part "COMP-TLV3502SOT-23-8-OR-MSOP-8"))
    )
    (comp (ref "IC6")
      (value "MCP6294")
      (footprint "eagle-import:TSSOP-14")
      (fields
        (field (name "DIGIKEY") "MCP6294-E/ST-ND")
        (field (name "MPN") "MCP6294-E/ST")
        (field (name "OC_NEWARK") "unknown")
        (field (name "PARTNO") "MCP6294-E/ST")
      )
      (libsource (lib "eagle-import") (part "OPAMP-TLC2274"))
    )
    (comp (ref "IC11")
      (value "CD4066")
      (footprint "eagle-import:TSSOP-14")
      (fields (field (name "MPN") "CD4066BPWR"))
      (libsource (lib "eagle-import") (part "CD4066"))
    )
    (comp (ref "IC14")
      (value "AD8052")
      (footprint "eagle-import:MSOP8")
      (fields
        (field (name "MPN") "AD8052ARMZ")
        (field (name "DIGIKEY") "AD8052ARMZ-ND")
        (field (name "OC_NEWARK") "unknown")
        (field (name "PARTNO") "AD8052ARMZ")
      )
      (libsource (lib "eagle-import") (part "OPAMP-AD8052"))
    )
    (comp (ref "Q1")
      (value "NPN-SOT23-2N3904")
      (footprint "eagle-import:SOT23-3LEAD")
      (fields (field (name "MF") "PMBT3904,215"))
      (libsource (lib "eagle-import") (part "NPN-SOT23-2N3904"))
    )
    (comp (ref "R9")
      (value "100K")
      (footprint "eagle-import:RLC_0603@1")
      (fields (field (name "MPN") "RC0603JR-07100KL"))
      (libsource (lib "eagle-import") (part "RESISTORRLC_0603"))
    )
    (comp (ref "R10")
      (value "100K")
      (footprint "eagle-import:RLC_0603@1")
      (fields (field (name "MPN") "RC0603JR-07100KL"))
      (libsource (lib "eagle-import") (part "RESISTORRLC_0603"))
    )
    (comp (ref "R11")
      (value "510K")
      (footprint "eagle-import:RLC_0603@1")
      (fields (field (name "MPN") "ERJ-3GEYJ514V"))
      (libsource (lib "eagle-import") (part "RESISTORRLC_0603"))
    )
    (comp (ref "R12")
      (value "100K")
      (footprint "eagle-import:RLC_0603@1")
      (fields (field (name "MPN") "RC0603JR-07100KL"))
      (libsource (lib "eagle-import") (part "RESISTORRLC_0603"))
    )
    (comp (ref "R13")
      (value "10K")
      (footprint "eagle-import:RLC_0603@1")
      (fields (field (name "DIGIKEY") "RMCF0603JT10K0CT-ND") (field (name "MPN") "RMCF0603JT10K0"))
      (libsource (lib "eagle-import") (part "RESISTORRLC_0603"))
    )
    (comp (ref "R14")
      (value "10K")
      (footprint "eagle-import:RLC_0603@1")
      (fields (field (name "DIGIKEY") "RMCF0603JT10K0CT-ND") (field (name "MPN") "RMCF0603JT10K0"))
      (libsource (lib "eagle-import") (part "RESISTORRLC_0603"))
    )
    (comp (ref "R15")
      (value "10K")
      (footprint "eagle-import:RLC_0603@1")
      (fields (field (name "DIGIKEY") "RMCF0603JT10K0CT-ND") (field (name "MPN") "RMCF0603JT10K0"))
      (libsource (lib "eagle-import") (part "RESISTORRLC_0603"))
    )
    (comp (ref "R16")
      (value "zerohm")
      (footprint "eagle-import:RLC_0603@1")
      (libsource (lib "eagle-import") (part "RESISTORRLC_0603"))
    )
    (comp (ref "R17")
      (value "10K")
      (footprint "eagle-import:RLC_0603@1")
      (fields (field (name "DIGIKEY") "RMCF0603JT10K0CT-ND") (field (name "MPN") "RMCF0603JT10K0"))
      (libsource (lib "eagle-import") (part "RESISTORRLC_0603"))
    )
    (comp (ref "R18")
      (value "10K")
      (footprint "eagle-import:RLC_0603@1")
      (fields (field (name "DIGIKEY") "RMCF0603JT10K0CT-ND") (field (name "MPN") "RMCF0603JT10K0"))
      (libsource (lib "eagle-import") (part "RESISTORRLC_0603"))
    )
    (comp (ref "R19")
      (value "10K")
      (footprint "eagle-import:RLC_0603@1")
      (fields (field (name "DIGIKEY") "RMCF0603JT10K0CT-ND") (field (name "MPN") "RMCF0603JT10K0"))
      (libsource (lib "eagle-import") (part "RESISTORRLC_0603"))
    )
    (comp (ref "R20")
      (value "240K")
      (footprint "eagle-import:RLC_0603@1")
      (fields (field (name "MPN") "RC1608J244CS"))
      (libsource (lib "eagle-import") (part "RESISTORRLC_0603"))
    )
    (comp (ref "R21")
      (value "24K")
      (footprint "eagle-import:RLC_0603@1")
      (fields (field (name "MPN") "RC0603JR-0724KL"))
      (libsource (lib "eagle-import") (part "RESISTORRLC_0603"))
    )
    (comp (ref "R30")
      (value "10M")
      (footprint "eagle-import:RLC_0603@1")
      (fields (field (name "MPN") "RC0603JR-0710ML"))
      (libsource (lib "eagle-import") (part "RESISTORRLC_0603"))
    )
    (comp (ref "R31")
      (value "240K")
      (footprint "eagle-import:RLC_0603@1")
      (fields (field (name "MPN") "RC1608J244CS"))
      (libsource (lib "eagle-import") (part "RESISTORRLC_0603"))
    )
    (comp (ref "R32")
      (value "zerohm")
      (footprint "eagle-import:RLC_0603@1")
      (libsource (lib "eagle-import") (part "RESISTORRLC_0603"))
    )
    (comp (ref "R33")
      (value "2.4K")
      (footprint "eagle-import:RLC_0603@1")
      (fields (field (name "MPN") "RC0603FR-072K4L"))
      (libsource (lib "eagle-import") (part "RESISTORRLC_0603"))
    )
    (comp (ref "R34")
      (value "10K")
      (footprint "eagle-import:RLC_0603@1")
      (fields (field (name "MPN") "RMCF0603JT10K0"))
      (libsource (lib "eagle-import") (part "RESISTORRLC_0603"))
    )
    (comp (ref "R35")
      (value "zerohm")
      (footprint "eagle-import:RLC_0603@1")
      (libsource (lib "eagle-import") (part "RESISTORRLC_0603"))
    )
    (comp (ref "R36")
      (value "dnp")
      (footprint "eagle-import:RLC_0603@1")
      (libsource (lib "eagle-import") (part "RESISTORRLC_0603"))
    )
    (comp (ref "R37")
      (value "dnp")
      (footprint "eagle-import:RLC_0603@1")
      (libsource (lib "eagle-import") (part "RESISTORRLC_0603"))
    )
    (comp (ref "R38")
      (value "dnp")
      (footprint "eagle-import:RLC_0603@1")
      (libsource (lib "eagle-import") (part "RESISTORRLC_0603"))
    )
    (comp (ref "R40")
      (value "10K")
      (footprint "eagle-import:RLC_0603@1")
      (fields (field (name "MPN") "RMCF0603JT10K0"))
      (libsource (lib "eagle-import") (part "RESISTORRLC_0603"))
    )
    (comp (ref "R41")
      (value "10M")
      (footprint "eagle-import:RLC_0603@1")
      (fields (field (name "MPN") "RC0603JR-0710ML"))
      (libsource (lib "eagle-import") (part "RESISTORRLC_0603"))
    )
    (comp (ref "R42")
      (value "1M")
      (footprint "eagle-import:RLC_0603@1")
      (fields (field (name "MPN") "RC0603JR-071ML"))
      (libsource (lib "eagle-import") (part "RESISTORRLC_0603"))
    )
    (comp (ref "R48")
      (value "dnp")
      (footprint "eagle-import:RLC_0603@1")
      (libsource (lib "eagle-import") (part "RESISTORRLC_0603"))
    )
    (comp (ref "R49")
      (value "2.4K")
      (footprint "eagle-import:RLC_0603@1")
      (fields (field (name "MPN") "RC0603FR-072K4L"))
      (libsource (lib "eagle-import") (part "RESISTORRLC_0603"))
    )
    (comp (ref "R50")
      (value "10K")
      (footprint "eagle-import:RLC_0603@1")
      (fields (field (name "MPN") "RMCF0603JT10K0"))
      (libsource (lib "eagle-import") (part "RESISTORRLC_0603"))
    )
    (comp (ref "R51")
      (value "2.4K")
      (footprint "eagle-import:RLC_0603@1")
      (fields (field (name "MPN") "RC0603FR-072K4L"))
      (libsource (lib "eagle-import") (part "RESISTORRLC_0603"))
    )
    (comp (ref "RLY1")
      (value "G6S-2H")
      (footprint "eagle-import:G6S-2F")
      (libsource (lib "eagle-import") (part "G6S-2H"))
    )
    (comp (ref "TP1")
      (value "TESTPAD")
      (footprint "eagle-import:SMD-TESTPOINT")
      (libsource (lib "eagle-import") (part "TESTPAD"))
    )
    (comp (ref "R61")
      (value "10K")
      (footprint "eagle-import:RLC_0603@1")
      (fields (field (name "MPN") "RMCF0603JT10K0"))
      (libsource (lib "eagle-import") (part "RESISTORRLC_0603"))
    )
    (comp (ref "R62")
      (value "10K")
      (footprint "eagle-import:RLC_0603@1")
      (fields (field (name "MPN") "RMCF0603JT10K0"))
      (libsource (lib "eagle-import") (part "RESISTORRLC_0603"))
    )
    (comp (ref "R63")
      (value "10K")
      (footprint "eagle-import:RLC_0603@1")
      (fields (field (name "MPN") "RMCF0603JT10K0"))
      (libsource (lib "eagle-import") (part "RESISTORRLC_0603"))
    )
    (comp (ref "R64")
      (value "10K")
      (footprint "eagle-import:RLC_0603@1")
      (fields (field (name "MPN") "RMCF0603JT10K0"))
      (libsource (lib "eagle-import") (part "RESISTORRLC_0603"))
    )
    (comp (ref "U4")
      (value "SDCARD")
      (footprint "eagle-import:MICRO-SD-SOCKET-PP")
      (libsource (lib "eagle-import") (part "USD-SOCKETNEW"))
    )
    (comp (ref "C4")
      (value "1uF")
      (footprint "eagle-import:RLC_0603")
      (fields (field (name "MPN") "CC0805ZRY5V8BB105"))
      (libsource (lib "eagle-import") (part "CAPACITORRLC_0603"))
    )
    (comp (ref "C5")
      (value "1uF")
      (footprint "eagle-import:RLC_0603")
      (fields (field (name "MPN") "CC0805ZRY5V8BB105"))
      (libsource (lib "eagle-import") (part "CAPACITORRLC_0603"))
    )
    (comp (ref "C6")
      (value "4.7uF")
      (footprint "eagle-import:RLC_0603")
      (fields (field (name "MPN") "CL21A475KOFNNNE"))
      (libsource (lib "eagle-import") (part "CAPACITORRLC_0603"))
    )
    (comp (ref "C7")
      (value "4.7uF")
      (footprint "eagle-import:RLC_0603")
      (fields (field (name "MPN") "CL21A475KOFNNNE"))
      (libsource (lib "eagle-import") (part "CAPACITORRLC_0603"))
    )
    (comp (ref "C8")
      (value "4.7uF")
      (footprint "eagle-import:RLC_0603")
      (fields (field (name "MPN") "CL21A475KOFNNNE"))
      (libsource (lib "eagle-import") (part "CAPACITORRLC_0603"))
    )
    (comp (ref "R3")
      (value "820K")
      (footprint "eagle-import:RLC_0603@1")
      (fields (field (name "MPN") "RC0603JR-07820KL"))
      (libsource (lib "eagle-import") (part "RESISTORRLC_0603"))
    )
    (comp (ref "R66")
      (value "10K")
      (footprint "eagle-import:RLC_0603@1")
      (fields (field (name "MPN") "RC0603JR-07820KL"))
      (libsource (lib "eagle-import") (part "RESISTORRLC_0603"))
    )
    (comp (ref "SJ1")
      (value "SOLDERJUMPERREFLOW")
      (footprint "eagle-import:SOLDERJUMPER_REFLOW")
      (fields (field (name "MPN") "NONE"))
      (libsource (lib "eagle-import") (part "SOLDERJUMPERREFLOW"))
    )
    (comp (ref "U3")
      (value "UG-2864HSWEG01")
      (footprint "eagle-import:MICROBUILDER_UG-2864HSWEG01_0.96IN_WRAPAROUND")
      (libsource (lib "eagle-import") (part "MICROBUILDER_DISP_OLED_UG-2864HSWEG010.96{dblquote}"))
    )
  )
  (nets
    (net (code "1") (name "+1V2") (class "Default")
      (node (ref "C206") (pin "1") (pinfunction "1_1") (pintype "passive"))
      (node (ref "C209") (pin "1") (pinfunction "1_1") (pintype "passive"))
      (node (ref "C210") (pin "1") (pinfunction "1_1") (pintype "passive"))
      (node (ref "C211") (pin "1") (pinfunction "1_1") (pintype "passive"))
      (node (ref "C212") (pin "1") (pinfunction "1_1") (pintype "passive"))
      (node (ref "IC106") (pin "5") (pinfunction "VOUT_5") (pintype "bidirectional"))
      (node (ref "TP20") (pin "1") (pinfunction "P$1_1") (pintype "bidirectional"))
      (node (ref "U2") (pin "18") (pinfunction "VCCINT_18") (pintype "power_in"))
      (node (ref "U2") (pin "45") (pinfunction "VCCINT_45") (pintype "power_in"))
      (node (ref "U2") (pin "69") (pinfunction "VCCINT_69") (pintype "power_in"))
      (node (ref "U2") (pin "93") (pinfunction "VCCINT_93") (pintype "power_in"))
    )
    (net (code "2") (name "+2V5") (class "Default")
      (node (ref "C29") (pin "1") (pinfunction "1_1") (pintype "passive"))
      (node (ref "C30") (pin "1") (pinfunction "1_1") (pintype "passive"))
      (node (ref "C31") (pin "1") (pinfunction "1_1") (pintype "passive"))
      (node (ref "C33") (pin "1") (pinfunction "1_1") (pintype "passive"))
      (node (ref "IC105") (pin "5") (pinfunction "VOUT_5") (pintype "bidirectional"))
      (node (ref "TP19") (pin "1") (pinfunction "P$1_1") (pintype "bidirectional"))
      (node (ref "U2") (pin "33") (pinfunction "VCCAUX_33") (pintype "power_in"))
      (node (ref "U2") (pin "58") (pinfunction "VCCAUX_58") (pintype "power_in"))
      (node (ref "U2") (pin "7") (pinfunction "VCCAUX_7") (pintype "power_in"))
      (node (ref "U2") (pin "84") (pinfunction "VCCAUX_84") (pintype "power_in"))
    )
    (net (code "3") (name "+3V3") (class "Default")
      (node (ref "BUZ1") (pin "1") (pinfunction "1_1") (pintype "passive"))
      (node (ref "C25") (pin "1") (pinfunction "1_1") (pintype "passive"))
      (node (ref "C26") (pin "1") (pinfunction "1_1") (pintype "passive"))
      (node (ref "C27") (pin "1") (pinfunction "1_1") (pintype "passive"))
      (node (ref "C48") (pin "1") (pinfunction "1_1") (pintype "passive"))
      (node (ref "C49") (pin "1") (pinfunction "1_1") (pintype "passive"))
      (node (ref "C50") (pin "1") (pinfunction "1_1") (pintype "passive"))
      (node (ref "C51") (pin "1") (pinfunction "1_1") (pintype "passive"))
      (node (ref "C7") (pin "1") (pinfunction "1_1") (pintype "passive"))
      (node (ref "D5") (pin "1") (pinfunction "A_1") (pintype "passive"))
      (node (ref "IC2") (pin "19") (pinfunction "VDD_19") (pintype "power_in"))
      (node (ref "IC2") (pin "32") (pinfunction "VDD_32") (pintype "power_in"))
      (node (ref "IC2") (pin "48") (pinfunction "VDD_48") (pintype "power_in"))
      (node (ref "IC2") (pin "64") (pinfunction "VDD_64") (pintype "power_in"))
      (node (ref "IC3") (pin "5") (pinfunction "VO_5") (pintype "bidirectional"))
      (node (ref "IC7") (pin "2") (pinfunction "V+_2") (pintype "bidirectional"))
      (node (ref "JP4") (pin "6") (pinfunction "6_6") (pintype "passive"))
      (node (ref "L1") (pin "1") (pinfunction "P$1_1") (pintype "bidirectional"))
      (node (ref "Q2") (pin "C") (pinfunction "C_C") (pintype "passive"))
      (node (ref "R57") (pin "1") (pinfunction "1_1") (pintype "passive"))
      (node (ref "R61") (pin "2") (pinfunction "2_2") (pintype "passive"))
      (node (ref "R62") (pin "2") (pinfunction "2_2") (pintype "passive"))
      (node (ref "R63") (pin "2") (pinfunction "2_2") (pintype "passive"))
      (node (ref "R64") (pin "2") (pinfunction "2_2") (pintype "passive"))
      (node (ref "R66") (pin "2") (pinfunction "2_2") (pintype "passive"))
      (node (ref "R69") (pin "2") (pinfunction "2_2") (pintype "passive"))
      (node (ref "R70") (pin "2") (pinfunction "2_2") (pintype "passive"))
      (node (ref "R71") (pin "2") (pinfunction "2_2") (pintype "passive"))
      (node (ref "SV5") (pin "6") (pinfunction "6_6") (pintype "passive"))
      (node (ref "U3") (pin "6") (pinfunction "VBAT_6") (pintype "input"))
      (node (ref "U3") (pin "9") (pinfunction "VDD_9") (pintype "power_in"))
      (node (ref "U4") (pin "4") (pinfunction "VCC_4") (pintype "bidirectional"))
    )
    (net (code "4") (name "+3V3-FPGA") (class "Default")
      (node (ref "C28") (pin "1") (pinfunction "1_1") (pintype "passive"))
      (node (ref "C32") (pin "1") (pinfunction "1_1") (pintype "passive"))
      (node (ref "C34") (pin "1") (pinfunction "1_1") (pintype "passive"))
      (node (ref "C47") (pin "1") (pinfunction "1_1") (pintype "passive"))
      (node (ref "IC13") (pin "5") (pinfunction "VO_5") (pintype "bidirectional"))
      (node (ref "IC4") (pin "5") (pinfunction "VDD_5") (pintype "bidirectional"))
      (node (ref "R59") (pin "2") (pinfunction "2_2") (pintype "passive"))
      (node (ref "TP18") (pin "1") (pinfunction "P$1_1") (pintype "bidirectional"))
      (node (ref "U2") (pin "19") (pinfunction "VCCO_6_19") (pintype "bidirectional"))
      (node (ref "U2") (pin "31") (pinfunction "VCCO_5_31") (pintype "bidirectional"))
      (node (ref "U2") (pin "46") (pinfunction "VCCO_4_46") (pintype "bidirectional"))
      (node (ref "U2") (pin "57") (pinfunction "VCCO_3_57") (pintype "bidirectional"))
      (node (ref "U2") (pin "6") (pinfunction "VCCO_7_6") (pintype "bidirectional"))
      (node (ref "U2") (pin "70") (pinfunction "VCCO_2_70") (pintype "bidirectional"))
      (node (ref "U2") (pin "83") (pinfunction "VCCO_1_83") (pintype "bidirectional"))
      (node (ref "U2") (pin "94") (pinfunction "VCCO_0_94") (pintype "bidirectional"))
    )
    (net (code "6") (name "1356_CRYSTAL") (class "Default")
      (node (ref "C3") (pin "1") (pinfunction "1_1") (pintype "passive"))
      (node (ref "R1") (pin "2") (pinfunction "2_2") (pintype "passive"))
      (node (ref "R2") (pin "2") (pinfunction "2_2") (pintype "passive"))
      (node (ref "U2") (pin "89") (pinfunction "L32P_0/GCLK6_89") (pintype "bidirectional"))
      (node (ref "U2") (pin "90") (pinfunction "L32N_0/GCLK7_90") (pintype "bidirectional"))
      (node (ref "XT1") (pin "B") (pinfunction "B_B") (pintype "bidirectional"))
    )
    (net (code "7") (name "ADC1") (class "Default")
      (node (ref "IC8") (pin "3") (pinfunction "D1_3") (pintype "bidirectional"))
      (node (ref "U2") (pin "38") (pinfunction "L32P_4/GCLK0_38") (pintype "bidirectional"))
    )
    (net (code "8") (name "ADC2") (class "Default")
      (node (ref "IC8") (pin "4") (pinfunction "D2_4") (pintype "bidirectional"))
      (node (ref "U2") (pin "37") (pinfunction "L32N_5/GCLK3_37") (pintype "bidirectional"))
    )
    (net (code "9") (name "ADC3") (class "Default")
      (node (ref "IC8") (pin "5") (pinfunction "D3_5") (pintype "bidirectional"))
      (node (ref "U2") (pin "36") (pinfunction "L32P_5/GCLK2_36") (pintype "bidirectional"))
    )
    (net (code "10") (name "ADC4") (class "Default")
      (node (ref "IC8") (pin "6") (pinfunction "D4_6") (pintype "bidirectional"))
      (node (ref "U2") (pin "35") (pinfunction "L31N_5/D4_35") (pintype "bidirectional"))
    )
    (net (code "11") (name "ADC5") (class "Default")
      (node (ref "IC8") (pin "7") (pinfunction "D5_7") (pintype "bidirectional"))
      (node (ref "U2") (pin "34") (pinfunction "L31P_5/D5_34") (pintype "bidirectional"))
    )
    (net (code "12") (name "ADC6") (class "Default")
      (node (ref "IC8") (pin "8") (pinfunction "D6_8") (pintype "bidirectional"))
      (node (ref "U2") (pin "32") (pinfunction "L28N_5/D6_32") (pintype "bidirectional"))
    )
    (net (code "13") (name "ADC7") (class "Default")
      (node (ref "IC8") (pin "9") (pinfunction "D7_9") (pintype "bidirectional"))
      (node (ref "U2") (pin "30") (pinfunction "L28P_5/D7_30") (pintype "bidirectional"))
    )
    (net (code "14") (name "ADC8") (class "Default")
      (node (ref "IC8") (pin "10") (pinfunction "MSB-D8_10") (pintype "bidirectional"))
      (node (ref "U2") (pin "28") (pinfunction "L01N_5/RDWR_B_28") (pintype "bidirectional"))
    )
    (net (code "15") (name "ADC_CLK") (class "Default")
      (node (ref "ADC_CLK_TP") (pin "1") (pinfunction "P$1_1") (pintype "bidirectional"))
      (node (ref "IC8") (pin "12") (pinfunction "CLK_12") (pintype "bidirectional"))
      (node (ref "U2") (pin "27") (pinfunction "L01P_5/CS_B_27") (pintype "bidirectional"))
    )
    (net (code "16") (name "ADC_IN") (class "Default")
      (node (ref "IC11") (pin "10") (pinfunction "B4_10") (pintype "passive"))
      (node (ref "IC11") (pin "2") (pinfunction "B1_2") (pintype "passive"))
      (node (ref "IC11") (pin "3") (pinfunction "B2_3") (pintype "passive"))
      (node (ref "IC11") (pin "9") (pinfunction "B3_9") (pintype "passive"))
      (node (ref "IC8") (pin "19") (pinfunction "ANALOGIN_19") (pintype "bidirectional"))
      (node (ref "TP1") (pin "1") (pinfunction "P$1_1") (pintype "bidirectional"))
    )
    (net (code "17") (name "ADC_NOE") (class "Default")
      (node (ref "ADC_NOE_TP") (pin "1") (pinfunction "P$1_1") (pintype "bidirectional"))
      (node (ref "IC8") (pin "1") (pinfunction "NOE_1") (pintype "bidirectional"))
      (node (ref "R47") (pin "2") (pinfunction "2_2") (pintype "passive"))
      (node (ref "U2") (pin "49") (pinfunction "L01P_4/VRN_4_49") (pintype "bidirectional"))
    )
    (net (code "18") (name "AMPL_HI") (class "Default")
      (node (ref "JP_AH") (pin "2") (pinfunction "2_2") (pintype "passive"))
      (node (ref "R41") (pin "2") (pinfunction "2_2") (pintype "passive"))
      (node (ref "R42") (pin "2") (pinfunction "2_2") (pintype "passive"))
    )
    (net (code "19") (name "AMPL_HI1") (class "Default")
      (node (ref "IC2") (pin "14") (pinfunction "PA0/WKUP/USART2_CTS/ADC123_IN0/TIM2_CH1_ETR/TIM5_CH1/TIME8_ETR_14") (pintype "bidirectional"))
      (node (ref "JP_AH") (pin "1") (pinfunction "1_1") (pintype "passive"))
      (node (ref "TP52") (pin "1") (pinfunction "P$1_1") (pintype "bidirectional"))
    )
    (net (code "20") (name "AMPL_LO") (class "Default")
      (node (ref "JP_AL") (pin "2") (pinfunction "2_2") (pintype "passive"))
      (node (ref "R30") (pin "2") (pinfunction "2_2") (pintype "passive"))
      (node (ref "R31") (pin "2") (pinfunction "2_2") (pintype "passive"))
    )
    (net (code "21") (name "AMPL_LO1") (class "Default")
      (node (ref "IC2") (pin "15") (pinfunction "PA1/USART2_RTS/ADC123_IN1/TIM5_CH2/TIM2_CH2_15") (pintype "bidirectional"))
      (node (ref "JP_AL") (pin "1") (pinfunction "1_1") (pintype "passive"))
      (node (ref "TP53") (pin "1") (pinfunction "P$1_1") (pintype "bidirectional"))
    )
    (net (code "22") (name "ANT_HI") (class "Default")
      (node (ref "C35") (pin "1") (pinfunction "1_1") (pintype "passive"))
      (node (ref "C36") (pin "1") (pinfunction "1_1") (pintype "passive"))
      (node (ref "RLY1") (pin "4") (pinfunction "COM_4") (pintype "passive"))
      (node (ref "SV2") (pin "4") (pinfunction "PIN4_4") (pintype "passive"))
      (node (ref "TP3") (pin "1") (pinfunction "P$1_1") (pintype "bidirectional"))
    )
    (net (code "23") (name "ANT_LO") (class "Default")
      (node (ref "C20") (pin "1") (pinfunction "1_1") (pintype "passive"))
      (node (ref "C39") (pin "1") (pinfunction "1_1") (pintype "passive"))
      (node (ref "RLY1") (pin "9") (pinfunction "COM_9") (pintype "passive"))
      (node (ref "SV2") (pin "2") (pinfunction "PIN2_2") (pintype "passive"))
      (node (ref "TP2") (pin "1") (pinfunction "P$1_1") (pintype "bidirectional"))
    )
    (net (code "24") (name "BOOT0_") (class "Default")
      (node (ref "JP4") (pin "7") (pinfunction "7_7") (pintype "passive"))
      (node (ref "R4") (pin "1") (pinfunction "1_1") (pintype "passive"))
    )
    (net (code "25") (name "CROSS_HI") (class "Default")
      (node (ref "CROSS_HI_TP") (pin "1") (pinfunction "P$1_1") (pintype "bidirectional"))
      (node (ref "IC5") (pin "6") (pinfunction "OUT_6") (pintype "output"))
      (node (ref "R44") (pin "1") (pinfunction "1_1") (pintype "passive"))
    )
    (net (code "26") (name "CROSS_LO") (class "Default")
      (node (ref "CROSS_LO_TP") (pin "1") (pinfunction "P$1_1") (pintype "bidirectional"))
      (node (ref "IC5") (pin "7") (pinfunction "OUT_7") (pintype "output"))
      (node (ref "R39") (pin "1") (pinfunction "1_1") (pintype "passive"))
    )
    (net (code "27") (name "DB2") (class "Default")
      (node (ref "SJ1") (pin "2") (pinfunction "2_2") (pintype "passive"))
      (node (ref "U3") (pin "20") (pinfunction "D2/I2C_SDA_20") (pintype "bidirectional"))
    )
    (net (code "28") (name "DBG") (class "Default")
      (node (ref "DBG_TP") (pin "1") (pinfunction "P$1_1") (pintype "bidirectional"))
      (node (ref "U2") (pin "75") (pinfunction "L01N_2/VRP_2_75") (pintype "bidirectional"))
    )
    (net (code "29") (name "D{slash}C") (class "Default")
      (node (ref "IC2") (pin "59") (pinfunction "PB7/I2C1_SDA/FSMC_NADV/TIM4_CH2/USART1_RX/FT_59") (pintype "bidirectional"))
      (node (ref "TP30") (pin "1") (pinfunction "P$1_1") (pintype "bidirectional"))
      (node (ref "U3") (pin "15") (pinfunction "DC/I2C_SA0_15") (pintype "input"))
    )
    (net (code "30") (name "FPGA_CCLK") (class "Default")
      (node (ref "IC2") (pin "41") (pinfunction "PA8/USART1_CK/TIM1_CH1/MCO/FT_41") (pintype "bidirectional"))
      (node (ref "TP25") (pin "1") (pinfunction "P$1_1") (pintype "bidirectional"))
      (node (ref "U2") (pin "52") (pinfunction "CCLK_52") (pintype "bidirectional"))
    )
    (net (code "31") (name "FPGA_DIN") (class "Default")
      (node (ref "IC2") (pin "42") (pinfunction "PA9/USART1_TX/TIM1_CH2/FT_42") (pintype "bidirectional"))
      (node (ref "TP26") (pin "1") (pinfunction "P$1_1") (pintype "bidirectional"))
      (node (ref "U2") (pin "48") (pinfunction "L27N_4/DIN/DO_48") (pintype "bidirectional"))
    )
    (net (code "32") (name "FPGA_DONE") (class "Default")
      (node (ref "IC2") (pin "26") (pinfunction "PB0/ADC12_IN8/TIM3_CH3/TIM8_CH2N/TIM1_CH2N_26") (pintype "bidirectional"))
      (node (ref "TP35") (pin "1") (pinfunction "P$1_1") (pintype "bidirectional"))
      (node (ref "U2") (pin "51") (pinfunction "DONE_51") (pintype "bidirectional"))
    )
    (net (code "33") (name "FPGA_DOUT") (class "Default")
      (node (ref "FPGA_DOUT_TP") (pin "1") (pinfunction "P$1_1") (pintype "bidirectional"))
      (node (ref "IC2") (pin "52") (pinfunction "PC11/UART4_RX/SDIO_D3/USART3_RX/FT_52") (pintype "bidirectional"))
      (node (ref "U2") (pin "40") (pinfunction "L31P_4/DOUT/BUSY_40") (pintype "bidirectional"))
    )
    (net (code "34") (name "FPGA_NINIT") (class "Default")
      (node (ref "FPGA_NINIT_TP") (pin "1") (pinfunction "P$1_1") (pintype "bidirectional"))
      (node (ref "IC2") (pin "38") (pinfunction "PC7/I2S3_MCK/TIM8_CH2/SDIO_D7/TIM3_CH2/FT_38") (pintype "bidirectional"))
      (node (ref "R59") (pin "1") (pinfunction "1_1") (pintype "passive"))
      (node (ref "U2") (pin "42") (pinfunction "L31N_4/INIT_B_42") (pintype "bidirectional"))
    )
    (net (code "35") (name "FPGA_NPROGRAM") (class "Default")
      (node (ref "IC2") (pin "23") (pinfunction "PA7/SPI1_MOSI/TIM8_CH1N/ADC12_IN7/TIM3_CH2/TIM1_CH1N_23") (pintype "bidirectional"))
      (node (ref "TP24") (pin "1") (pinfunction "P$1_1") (pintype "bidirectional"))
      (node (ref "U2") (pin "99") (pinfunction "PROG_B_99") (pintype "bidirectional"))
    )
    (net (code "36") (name "FPGA_ON") (class "Default")
      (node (ref "IC105") (pin "3") (pinfunction "EN_3") (pintype "bidirectional"))
      (node (ref "IC106") (pin "3") (pinfunction "EN_3") (pintype "bidirectional"))
      (node (ref "IC13") (pin "3") (pinfunction "VC_3") (pintype "bidirectional"))
      (node (ref "IC2") (pin "30") (pinfunction "PB11/I2C2_SDA/USART3_RX/TIM2_CH4/FT_30") (pintype "bidirectional"))
      (node (ref "R102") (pin "1") (pinfunction "1_1") (pintype "passive"))
      (node (ref "R23") (pin "2") (pinfunction "2_2") (pintype "passive"))
      (node (ref "TP22") (pin "1") (pinfunction "P$1_1") (pintype "bidirectional"))
    )
    (net (code "37") (name "FPGA_TCK") (class "Default")
      (node (ref "SV5") (pin "4") (pinfunction "4_4") (pintype "passive"))
      (node (ref "U2") (pin "77") (pinfunction "TCK_77") (pintype "bidirectional"))
    )
    (net (code "38") (name "FPGA_TDI") (class "Default")
      (node (ref "SV5") (pin "2") (pinfunction "2_2") (pintype "passive"))
      (node (ref "U2") (pin "100") (pinfunction "TDI_100") (pintype "bidirectional"))
    )
    (net (code "39") (name "FPGA_TDO") (class "Default")
      (node (ref "SV5") (pin "3") (pinfunction "3_3") (pintype "passive"))
      (node (ref "U2") (pin "76") (pinfunction "TDO_76") (pintype "bidirectional"))
    )
    (net (code "40") (name "FPGA_TMS") (class "Default")
      (node (ref "SV5") (pin "1") (pinfunction "1_1") (pintype "passive"))
      (node (ref "U2") (pin "78") (pinfunction "TMS_78") (pintype "bidirectional"))
    )
    (net (code "41") (name "GND") (class "Default")
      (node (ref "BAT1") (pin "GND") (pinfunction "-_GND") (pintype "power_in"))
      (node (ref "C1") (pin "2") (pinfunction "2_2") (pintype "passive"))
      (node (ref "C10") (pin "2") (pinfunction "2_2") (pintype "passive"))
      (node (ref "C11") (pin "2") (pinfunction "2_2") (pintype "passive"))
      (node (ref "C15") (pin "2") (pinfunction "2_2") (pintype "passive"))
      (node (ref "C18") (pin "2") (pinfunction "2_2") (pintype "passive"))
      (node (ref "C19") (pin "2") (pinfunction "2_2") (pintype "passive"))
      (node (ref "C2") (pin "2") (pinfunction "2_2") (pintype "passive"))
      (node (ref "C20") (pin "2") (pinfunction "2_2") (pintype "passive"))
      (node (ref "C206") (pin "2") (pinfunction "2_2") (pintype "passive"))
      (node (ref "C209") (pin "2") (pinfunction "2_2") (pintype "passive"))
      (node (ref "C21") (pin "2") (pinfunction "2_2") (pintype "passive"))
      (node (ref "C210") (pin "2") (pinfunction "2_2") (pintype "passive"))
      (node (ref "C211") (pin "2") (pinfunction "2_2") (pintype "passive"))
      (node (ref "C212") (pin "2") (pinfunction "2_2") (pintype "passive"))
      (node (ref "C22") (pin "2") (pinfunction "2_2") (pintype "passive"))
      (node (ref "C23") (pin "2") (pinfunction "2_2") (pintype "passive"))
      (node (ref "C24") (pin "2") (pinfunction "2_2") (pintype "passive"))
      (node (ref "C25") (pin "2") (pinfunction "2_2") (pintype "passive"))
      (node (ref "C26") (pin "2") (pinfunction "2_2") (pintype "passive"))
      (node (ref "C27") (pin "2") (pinfunction "2_2") (pintype "passive"))
      (node (ref "C28") (pin "2") (pinfunction "2_2") (pintype "passive"))
      (node (ref "C29") (pin "2") (pinfunction "2_2") (pintype "passive"))
      (node (ref "C3") (pin "2") (pinfunction "2_2") (pintype "passive"))
      (node (ref "C30") (pin "2") (pinfunction "2_2") (pintype "passive"))
      (node (ref "C31") (pin "2") (pinfunction "2_2") (pintype "passive"))
      (node (ref "C32") (pin "2") (pinfunction "2_2") (pintype "passive"))
      (node (ref "C33") (pin "2") (pinfunction "2_2") (pintype "passive"))
      (node (ref "C34") (pin "2") (pinfunction "2_2") (pintype "passive"))
      (node (ref "C35") (pin "2") (pinfunction "2_2") (pintype "passive"))
      (node (ref "C36") (pin "2") (pinfunction "2_2") (pintype "passive"))
      (node (ref "C37") (pin "-") (pinfunction "-_-") (pintype "passive"))
      (node (ref "C38") (pin "-") (pinfunction "-_-") (pintype "passive"))
      (node (ref "C39") (pin "2") (pinfunction "2_2") (pintype "passive"))
      (node (ref "C44") (pin "2") (pinfunction "2_2") (pintype "passive"))
      (node (ref "C45") (pin "2") (pinfunction "2_2") (pintype "passive"))
      (node (ref "C46") (pin "2") (pinfunction "2_2") (pintype "passive"))
      (node (ref "C47") (pin "2") (pinfunction "2_2") (pintype "passive"))
      (node (ref "C48") (pin "2") (pinfunction "2_2") (pintype "passive"))
      (node (ref "C49") (pin "2") (pinfunction "2_2") (pintype "passive"))
      (node (ref "C50") (pin "2") (pinfunction "2_2") (pintype "passive"))
      (node (ref "C51") (pin "2") (pinfunction "2_2") (pintype "passive"))
      (node (ref "C52") (pin "2") (pinfunction "2_2") (pintype "passive"))
      (node (ref "C53") (pin "1") (pinfunction "1_1") (pintype "passive"))
      (node (ref "C54") (pin "1") (pinfunction "1_1") (pintype "passive"))
      (node (ref "C55") (pin "C") (pinfunction "-_C") (pintype "passive"))
      (node (ref "C56") (pin "2") (pinfunction "2_2") (pintype "passive"))
      (node (ref "C57") (pin "2") (pinfunction "2_2") (pintype "passive"))
      (node (ref "C58") (pin "2") (pinfunction "2_2") (pintype "passive"))
      (node (ref "C59") (pin "2") (pinfunction "2_2") (pintype "passive"))
      (node (ref "C6") (pin "2") (pinfunction "2_2") (pintype "passive"))
      (node (ref "C60") (pin "2") (pinfunction "2_2") (pintype "passive"))
      (node (ref "C61") (pin "2") (pinfunction "2_2") (pintype "passive"))
      (node (ref "C62") (pin "2") (pinfunction "2_2") (pintype "passive"))
      (node (ref "C63") (pin "2") (pinfunction "2_2") (pintype "passive"))
      (node (ref "C64") (pin "2") (pinfunction "2_2") (pintype "passive"))
      (node (ref "C65") (pin "2") (pinfunction "2_2") (pintype "passive"))
      (node (ref "C66") (pin "2") (pinfunction "2_2") (pintype "passive"))
      (node (ref "C67") (pin "2") (pinfunction "2_2") (pintype "passive"))
      (node (ref "C68") (pin "-") (pinfunction "-_-") (pintype "passive"))
      (node (ref "C69") (pin "-") (pinfunction "-_-") (pintype "passive"))
      (node (ref "C7") (pin "2") (pinfunction "2_2") (pintype "passive"))
      (node (ref "C70") (pin "-") (pinfunction "-_-") (pintype "passive"))
      (node (ref "C71") (pin "2") (pinfunction "2_2") (pintype "passive"))
      (node (ref "C72") (pin "2") (pinfunction "2_2") (pintype "passive"))
      (node (ref "C73") (pin "-") (pinfunction "-_-") (pintype "passive"))
      (node (ref "C74") (pin "2") (pinfunction "2_2") (pintype "passive"))
      (node (ref "C75") (pin "2") (pinfunction "2_2") (pintype "passive"))
      (node (ref "C76") (pin "1") (pinfunction "1_1") (pintype "passive"))
      (node (ref "C77") (pin "1") (pinfunction "1_1") (pintype "passive"))
      (node (ref "C8") (pin "2") (pinfunction "2_2") (pintype "passive"))
      (node (ref "C9") (pin "1") (pinfunction "1_1") (pintype "passive"))
      (node (ref "D10") (pin "1") (pinfunction "A_1") (pintype "passive"))
      (node (ref "D11") (pin "1") (pinfunction "A_1") (pintype "passive"))
      (node (ref "D3") (pin "1") (pinfunction "A_1") (pintype "passive"))
      (node (ref "D6") (pin "1") (pinfunction "P$1_1") (pintype "passive"))
      (node (ref "IC1") (pin "4") (pinfunction "PGND_4") (pintype "power_in"))
      (node (ref "IC1") (pin "9") (pinfunction "GND_9") (pintype "power_in"))
      (node (ref "IC10") (pin "10") (pinfunction "VSS_10") (pintype "bidirectional"))
      (node (ref "IC105") (pin "2") (pinfunction "GND_2") (pintype "bidirectional"))
      (node (ref "IC106") (pin "2") (pinfunction "GND_2") (pintype "bidirectional"))
      (node (ref "IC11") (pin "7") (pinfunction "VSS_7") (pintype "bidirectional"))
      (node (ref "IC13") (pin "2") (pinfunction "GND_2") (pintype "bidirectional"))
      (node (ref "IC14") (pin "4") (pinfunction "V-_4") (pintype "bidirectional"))
      (node (ref "IC2") (pin "12") (pinfunction "VSSA_12") (pintype "power_in"))
      (node (ref "IC2") (pin "18") (pinfunction "VSS_18") (pintype "power_in"))
      (node (ref "IC2") (pin "63") (pinfunction "VSS_63") (pintype "power_in"))
      (node (ref "IC3") (pin "2") (pinfunction "GND_2") (pintype "bidirectional"))
      (node (ref "IC4") (pin "3") (pinfunction "VSS_3") (pintype "bidirectional"))
      (node (ref "IC5") (pin "2") (pinfunction "-IN_2") (pintype "input"))
      (node (ref "IC5") (pin "4") (pinfunction "-IN_4") (pintype "input"))
      (node (ref "IC5") (pin "5") (pinfunction "V-_5") (pintype "bidirectional"))
      (node (ref "IC6") (pin "11") (pinfunction "V-_11") (pintype "bidirectional"))
      (node (ref "IC6") (pin "12") (pinfunction "+IN_12") (pintype "input"))
      (node (ref "IC6") (pin "13") (pinfunction "-IN_13") (pintype "input"))
      (node (ref "IC7") (pin "3") (pinfunction "V-_3") (pintype "bidirectional"))
      (node (ref "IC8") (pin "2") (pinfunction "DGND0_2") (pintype "bidirectional"))
      (node (ref "IC8") (pin "20") (pinfunction "AGND0_20") (pintype "bidirectional"))
      (node (ref "IC8") (pin "21") (pinfunction "AGND1_21") (pintype "bidirectional"))
      (node (ref "IC8") (pin "24") (pinfunction "DGND1_24") (pintype "bidirectional"))
      (node (ref "IC9") (pin "10") (pinfunction "VSS_10") (pintype "bidirectional"))
      (node (ref "JP2") (pin "1") (pinfunction "1_1") (pintype "passive"))
      (node (ref "JP4") (pin "5") (pinfunction "5_5") (pintype "passive"))
      (node (ref "K1") (pin "1") (pinfunction "P_1") (pintype "passive"))
      (node (ref "K2") (pin "1") (pinfunction "P_1") (pintype "passive"))
      (node (ref "K3") (pin "1") (pinfunction "P_1") (pintype "passive"))
      (node (ref "LED3") (pin "C") (pinfunction "C_C") (pintype "passive"))
      (node (ref "Q1") (pin "2") (pinfunction "E_2") (pintype "bidirectional"))
      (node (ref "Q3") (pin "2") (pinfunction "E_2") (pintype "passive"))
      (node (ref "Q4") (pin "E") (pinfunction "E_E") (pintype "passive"))
      (node (ref "R10") (pin "1") (pinfunction "1_1") (pintype "passive"))
      (node (ref "R102") (pin "2") (pinfunction "2_2") (pintype "passive"))
      (node (ref "R11") (pin "1") (pinfunction "1_1") (pintype "passive"))
      (node (ref "R15") (pin "1") (pinfunction "1_1") (pintype "passive"))
      (node (ref "R23") (pin "1") (pinfunction "1_1") (pintype "passive"))
      (node (ref "R3") (pin "1") (pinfunction "1_1") (pintype "passive"))
      (node (ref "R31") (pin "1") (pinfunction "1_1") (pintype "passive"))
      (node (ref "R42") (pin "1") (pinfunction "1_1") (pintype "passive"))
      (node (ref "R54") (pin "1") (pinfunction "1_1") (pintype "passive"))
      (node (ref "R60") (pin "1") (pinfunction "1_1") (pintype "passive"))
      (node (ref "R67") (pin "1") (pinfunction "1_1") (pintype "passive"))
      (node (ref "S1") (pin "1") (pinfunction "O_1") (pintype "passive"))
      (node (ref "SV1") (pin "5") (pinfunction "GND/5_5") (pintype "bidirectional"))
      (node (ref "SV1") (pin "TAB0") (pinfunction "SHLD0_TAB0") (pintype "bidirectional"))
      (node (ref "SV1") (pin "TAB1") (pinfunction "SHLD1_TAB1") (pintype "bidirectional"))
      (node (ref "SV1") (pin "TAB2") (pinfunction "SHLD2_TAB2") (pintype "bidirectional"))
      (node (ref "SV1") (pin "TAB3") (pinfunction "SHLD3_TAB3") (pintype "bidirectional"))
      (node (ref "SV5") (pin "5") (pinfunction "5_5") (pintype "passive"))
      (node (ref "U$7") (pin "4") (pinfunction "~{EN}_4") (pintype "bidirectional"))
      (node (ref "U$7") (pin "5") (pinfunction "GND_5") (pintype "power_in"))
      (node (ref "U$7") (pin "9") (pinfunction "EP_9") (pintype "power_in"))
      (node (ref "U$7") (pin "V1") (pinfunction "V1_V1") (pintype "power_in"))
      (node (ref "U$9") (pin "1") (pinfunction "NEG_1") (pintype "power_in"))
      (node (ref "U2") (pin "10") (pinfunction "GND_10") (pintype "power_in"))
      (node (ref "U2") (pin "20") (pinfunction "GND_20") (pintype "power_in"))
      (node (ref "U2") (pin "29") (pinfunction "GND_29") (pintype "power_in"))
      (node (ref "U2") (pin "3") (pinfunction "GND_3") (pintype "power_in"))
      (node (ref "U2") (pin "41") (pinfunction "GND_41") (pintype "power_in"))
      (node (ref "U2") (pin "56") (pinfunction "GND_56") (pintype "power_in"))
      (node (ref "U2") (pin "66") (pinfunction "GND_66") (pintype "power_in"))
      (node (ref "U2") (pin "73") (pinfunction "GND_73") (pintype "power_in"))
      (node (ref "U2") (pin "82") (pinfunction "GND_82") (pintype "power_in"))
      (node (ref "U2") (pin "95") (pinfunction "GND_95") (pintype "power_in"))
      (node (ref "U3") (pin "1") (pinfunction "NC(GND)_1") (pintype "input"))
      (node (ref "U3") (pin "10") (pinfunction "BS0_10") (pintype "input"))
      (node (ref "U3") (pin "11") (pinfunction "BS1_11") (pintype "input"))
      (node (ref "U3") (pin "12") (pinfunction "BS2_12") (pintype "input"))
      (node (ref "U3") (pin "29") (pinfunction "VLSS_29") (pintype "power_in"))
      (node (ref "U3") (pin "30") (pinfunction "NC(GND)_30") (pintype "input"))
      (node (ref "U3") (pin "8") (pinfunction "VSS_8") (pintype "power_in"))
      (node (ref "U4") (pin "6") (pinfunction "GND_6") (pintype "bidirectional"))
      (node (ref "U4") (pin "CD1") (pinfunction "SHIELD_CD1") (pintype "bidirectional"))
      (node (ref "U4") (pin "CD2") (pinfunction "SHIELD_CD2") (pintype "bidirectional"))
      (node (ref "U4") (pin "GND1") (pinfunction "SHIELD_GND1") (pintype "bidirectional"))
      (node (ref "U4") (pin "GND3") (pinfunction "SHIELD_GND3") (pintype "bidirectional"))
      (node (ref "USB-MICRO") (pin "GND") (pinfunction "GND_GND") (pintype "bidirectional"))
    )
    (net (code "42") (name "JTAG_TCK") (class "Default")
      (node (ref "IC2") (pin "49") (pinfunction "PA14/JTCK/SWCLK/FT_49") (pintype "input"))
      (node (ref "JP4") (pin "4") (pinfunction "4_4") (pintype "passive"))
    )
    (net (code "43") (name "JTAG_TMS") (class "Default")
      (node (ref "IC2") (pin "46") (pinfunction "PA13/JTMS/SWDIO/FT_46") (pintype "input"))
      (node (ref "JP4") (pin "1") (pinfunction "1_1") (pintype "passive"))
    )
    (net (code "44") (name "JTRST") (class "Default")
      (node (ref "IC2") (pin "58") (pinfunction "PB6/I2C1_SCL/TIM4_CH1/USART1_TX/FT_58") (pintype "bidirectional"))
      (node (ref "TP31") (pin "1") (pinfunction "P$1_1") (pintype "bidirectional"))
    )
    (net (code "45") (name "LED_A") (class "Default")
      (node (ref "IC2") (pin "54") (pinfunction "PD2/TIM3_ETR/UART5_RX/SDIO_CMD/FT_54") (pintype "bidirectional"))
      (node (ref "LED_A_TP") (pin "1") (pinfunction "P$1_1") (pintype "bidirectional"))
      (node (ref "R65") (pin "1") (pinfunction "1_1") (pintype "passive"))
    )
    (net (code "46") (name "MISO") (class "Default")
      (node (ref "IC2") (pin "4") (pinfunction "PC15/OSC32_OUT_4") (pintype "bidirectional"))
      (node (ref "MISO_TP") (pin "1") (pinfunction "P$1_1") (pintype "bidirectional"))
      (node (ref "U2") (pin "15") (pinfunction "L24P_6_15") (pintype "bidirectional"))
    )
    (net (code "47") (name "MOSI") (class "Default")
      (node (ref "IC2") (pin "3") (pinfunction "PC14/OSC32_IN_3") (pintype "bidirectional"))
      (node (ref "MOSI_TP") (pin "1") (pinfunction "P$1_1") (pintype "bidirectional"))
      (node (ref "U2") (pin "14") (pinfunction "L40N_6_14") (pintype "bidirectional"))
    )
    (net (code "48") (name "MUXSEL_HIPKD") (class "Default")
      (node (ref "FPGA_NINIT_TP2") (pin "1") (pinfunction "P$1_1") (pintype "bidirectional"))
      (node (ref "IC11") (pin "12") (pinfunction "C4_12") (pintype "input"))
      (node (ref "IC2") (pin "40") (pinfunction "PC9/TIM8_CH4/SDIO_D1/TIM3_CH4/FT_40") (pintype "bidirectional"))
    )
    (net (code "49") (name "MUXSEL_HIRAW") (class "Default")
      (node (ref "IC11") (pin "6") (pinfunction "C3_6") (pintype "input"))
      (node (ref "IC2") (pin "28") (pinfunction "PB2/BOOT1/FT_28") (pintype "bidirectional"))
      (node (ref "TP33") (pin "1") (pinfunction "P$1_1") (pintype "bidirectional"))
    )
    (net (code "50") (name "MUXSEL_LOPKD") (class "Default")
      (node (ref "FPGA_NINIT_TP1") (pin "1") (pinfunction "P$1_1") (pintype "bidirectional"))
      (node (ref "IC11") (pin "5") (pinfunction "C2_5") (pintype "input"))
      (node (ref "IC2") (pin "39") (pinfunction "PC8/TIM8_CH3/SDIO_D0/TIM3_CH3/FT_39") (pintype "bidirectional"))
    )
    (net (code "51") (name "MUXSEL_LORAW") (class "Default")
      (node (ref "IC11") (pin "13") (pinfunction "C1_13") (pintype "input"))
      (node (ref "IC2") (pin "27") (pinfunction "PB1/ADC12_IN9/TIM3_CH4/TIM8_CH3N/TIM1_CH3N_27") (pintype "bidirectional"))
      (node (ref "TP34") (pin "1") (pinfunction "P$1_1") (pintype "bidirectional"))
    )
    (net (code "52") (name "N$58") (class "Default")
      (node (ref "SPARE_FPGA_TP") (pin "1") (pinfunction "P$1_1") (pintype "bidirectional"))
      (node (ref "U2") (pin "43") (pinfunction "L30P_4/D3_43") (pintype "bidirectional"))
    )
    (net (code "53") (name "NCS") (class "Default")
      (node (ref "IC2") (pin "53") (pinfunction "PC12/UART5_TX/SDIO_CK/USART3_CK/FT_53") (pintype "bidirectional"))
      (node (ref "NCS_TP") (pin "1") (pinfunction "P$1_1") (pintype "bidirectional"))
      (node (ref "U2") (pin "50") (pinfunction "L01N_4/VRP_4_50") (pintype "bidirectional"))
    )
    (net (code "54") (name "NRST") (class "Default")
      (node (ref "C56") (pin "1") (pinfunction "1_1") (pintype "passive"))
      (node (ref "IC2") (pin "7") (pinfunction "NRST_7") (pintype "input"))
      (node (ref "R5") (pin "2") (pinfunction "2_2") (pintype "passive"))
    )
    (net (code "55") (name "NTC") (class "Default")
      (node (ref "R43") (pin "1") (pinfunction "1_1") (pintype "passive"))
      (node (ref "TP16") (pin "1") (pinfunction "P$1_1") (pintype "bidirectional"))
      (node (ref "U$9") (pin "2") (pinfunction "NTC_2") (pintype "power_in"))
    )
    (net (code "56") (name "Net-(BAT1-+)") (class "Default")
      (node (ref "BAT1") (pin "PWR@1") (pinfunction "+_PWR@1") (pintype "power_in"))
      (node (ref "D4") (pin "1") (pinfunction "A_1") (pintype "passive"))
    )
    (net (code "57") (name "Net-(C16-Pad1)") (class "Default")
      (node (ref "C16") (pin "1") (pinfunction "1_1") (pintype "passive"))
      (node (ref "R16") (pin "2") (pinfunction "2_2") (pintype "passive"))
    )
    (net (code "58") (name "Net-(C42-Pad2)") (class "Default")
      (node (ref "C42") (pin "2") (pinfunction "2_2") (pintype "passive"))
      (node (ref "R35") (pin "1") (pinfunction "1_1") (pintype "passive"))
    )
    (net (code "59") (name "Net-(C43-Pad2)") (class "Default")
      (node (ref "C43") (pin "2") (pinfunction "2_2") (pintype "passive"))
      (node (ref "R32") (pin "1") (pinfunction "1_1") (pintype "passive"))
    )
    (net (code "60") (name "Net-(C57-Pad1)") (class "Default")
      (node (ref "C57") (pin "1") (pinfunction "1_1") (pintype "passive"))
      (node (ref "LED2") (pin "C") (pinfunction "C_C") (pintype "passive"))
      (node (ref "R24") (pin "1") (pinfunction "1_1") (pintype "passive"))
    )
    (net (code "61") (name "Net-(C58-Pad1)") (class "Default")
      (node (ref "C58") (pin "1") (pinfunction "1_1") (pintype "passive"))
      (node (ref "LED1") (pin "C") (pinfunction "C_C") (pintype "passive"))
      (node (ref "R25") (pin "1") (pinfunction "1_1") (pintype "passive"))
    )
    (net (code "62") (name "Net-(C76-Pad2)") (class "Default")
      (node (ref "C76") (pin "2") (pinfunction "2_2") (pintype "passive"))
      (node (ref "IC2") (pin "31") (pinfunction "VSS_31") (pintype "power_in"))
    )
    (net (code "63") (name "Net-(C77-Pad2)") (class "Default")
      (node (ref "C77") (pin "2") (pinfunction "2_2") (pintype "passive"))
      (node (ref "IC2") (pin "47") (pinfunction "VSS_47") (pintype "power_in"))
    )
    (net (code "64") (name "Net-(D1-A)") (class "Default")
      (node (ref "D1") (pin "1") (pinfunction "A_1") (pintype "passive"))
      (node (ref "R20") (pin "1") (pinfunction "1_1") (pintype "passive"))
      (node (ref "RLY1") (pin "10") (pinfunction "NC_10") (pintype "passive"))
    )
    (net (code "65") (name "Net-(D1-C)") (class "Default")
      (node (ref "C11") (pin "1") (pinfunction "1_1") (pintype "passive"))
      (node (ref "C12") (pin "1") (pinfunction "1_1") (pintype "passive"))
      (node (ref "D1") (pin "3") (pinfunction "C_3") (pintype "passive"))
      (node (ref "D11") (pin "3") (pinfunction "C_3") (pintype "passive"))
      (node (ref "R11") (pin "2") (pinfunction "2_2") (pintype "passive"))
      (node (ref "R30") (pin "1") (pinfunction "1_1") (pintype "passive"))
    )
    (net (code "66") (name "Net-(D2-A)") (class "Default")
      (node (ref "C14") (pin "2") (pinfunction "2_2") (pintype "passive"))
      (node (ref "D2") (pin "1") (pinfunction "A_1") (pintype "passive"))
      (node (ref "D3") (pin "3") (pinfunction "C_3") (pintype "passive"))
    )
    (net (code "67") (name "Net-(D4-C)") (class "Default")
      (node (ref "C9") (pin "2") (pinfunction "2_2") (pintype "passive"))
      (node (ref "D4") (pin "3") (pinfunction "C_3") (pintype "passive"))
      (node (ref "D5") (pin "3") (pinfunction "C_3") (pintype "passive"))
      (node (ref "IC2") (pin "1") (pinfunction "VBAT_1") (pintype "passive"))
    )
    (net (code "68") (name "Net-(D6-P$4)") (class "Default")
      (node (ref "D6") (pin "4") (pinfunction "P$4_4") (pintype "passive"))
      (node (ref "F1") (pin "2") (pinfunction "2_2") (pintype "passive"))
      (node (ref "SV1") (pin "1") (pinfunction "VBUS/1_1") (pintype "bidirectional"))
      (node (ref "USB-MICRO") (pin "VBUS") (pinfunction "VBUS_VBUS") (pintype "bidirectional"))
    )
    (net (code "69") (name "Net-(D7-A)") (class "Default")
      (node (ref "D7") (pin "1") (pinfunction "A_1") (pintype "passive"))
      (node (ref "Q1") (pin "3") (pinfunction "C_3") (pintype "bidirectional"))
      (node (ref "RLY1") (pin "12") (pinfunction "P$2_12") (pintype "passive"))
    )
    (net (code "70") (name "Net-(D10-C)") (class "Default")
      (node (ref "C15") (pin "1") (pinfunction "1_1") (pintype "passive"))
      (node (ref "D10") (pin "3") (pinfunction "C_3") (pintype "passive"))
      (node (ref "D2") (pin "3") (pinfunction "C_3") (pintype "passive"))
      (node (ref "R15") (pin "2") (pinfunction "2_2") (pintype "passive"))
      (node (ref "R16") (pin "1") (pinfunction "1_1") (pintype "passive"))
      (node (ref "R41") (pin "1") (pinfunction "1_1") (pintype "passive"))
    )
    (net (code "71") (name "Net-(FB1-A)") (class "Default")
      (node (ref "C65") (pin "1") (pinfunction "1_1") (pintype "passive"))
      (node (ref "C70") (pin "+") (pinfunction "+_+") (pintype "passive"))
      (node (ref "FB1") (pin "1") (pinfunction "A_1") (pintype "bidirectional"))
      (node (ref "IC8") (pin "18") (pinfunction "VDDA2_18") (pintype "bidirectional"))
    )
    (net (code "72") (name "Net-(FB2\\-A)") (class "Default")
      (node (ref "C67") (pin "1") (pinfunction "1_1") (pintype "passive"))
      (node (ref "C69") (pin "+") (pinfunction "+_+") (pintype "passive"))
      (node (ref "FB2\\") (pin "1") (pinfunction "A_1") (pintype "bidirectional"))
      (node (ref "IC8") (pin "14") (pinfunction "VDDA0_14") (pintype "bidirectional"))
    )
    (net (code "73") (name "Net-(FB3-A)") (class "Default")
      (node (ref "C66") (pin "1") (pinfunction "1_1") (pintype "passive"))
      (node (ref "C68") (pin "+") (pinfunction "+_+") (pintype "passive"))
      (node (ref "FB3") (pin "1") (pinfunction "A_1") (pintype "bidirectional"))
      (node (ref "IC8") (pin "15") (pinfunction "VDDA1_15") (pintype "bidirectional"))
    )
    (net (code "74") (name "Net-(IC1B-L)") (class "Default")
      (node (ref "IC1") (pin "3") (pinfunction "L_3") (pintype "input"))
      (node (ref "L2") (pin "P$2") (pinfunction "2_P$2") (pintype "passive"))
    )
    (net (code "75") (name "Net-(IC1B-UVLO)") (class "Default")
      (node (ref "IC1") (pin "7") (pinfunction "UVLO_7") (pintype "input"))
      (node (ref "R55") (pin "1") (pinfunction "1_1") (pintype "passive"))
      (node (ref "R60") (pin "2") (pinfunction "2_2") (pintype "passive"))
    )
    (net (code "76") (name "Net-(IC1B-VAUX)") (class "Default")
      (node (ref "C63") (pin "1") (pinfunction "1_1") (pintype "passive"))
      (node (ref "IC1") (pin "1") (pinfunction "VAUX_1") (pintype "bidirectional"))
    )
    (net (code "77") (name "Net-(IC2-BOOT0)") (class "Default")
      (node (ref "IC2") (pin "60") (pinfunction "BOOT0_60") (pintype "input"))
      (node (ref "R4") (pin "2") (pinfunction "2_2") (pintype "passive"))
    )
    (net (code "78") (name "Net-(IC2-PA11{slash}UART1CTS{slash}CNRX{slash}TIM1CH4{slash}USBD-{slash}FT)") (class "Default")
      (node (ref "IC2") (pin "44") (pinfunction "PA11/UART1CTS/CNRX/TIM1CH4/USBD-/FT_44") (pintype "bidirectional"))
      (node (ref "R7") (pin "2") (pinfunction "2_2") (pintype "passive"))
    )
    (net (code "79") (name "Net-(IC2-PA12{slash}UART1RTS{slash}CNTX{slash}TIM1ETR{slash}USBD+{slash}FT)") (class "Default")
      (node (ref "IC2") (pin "45") (pinfunction "PA12/UART1RTS/CNTX/TIM1ETR/USBD+/FT_45") (pintype "bidirectional"))
      (node (ref "R8") (pin "2") (pinfunction "2_2") (pintype "passive"))
    )
    (net (code "80") (name "Net-(IC2-PC3{slash}ADC123_IN13)") (class "Default")
      (node (ref "IC2") (pin "11") (pinfunction "PC3/ADC123_IN13_11") (pintype "bidirectional"))
      (node (ref "JP_AH") (pin "3") (pinfunction "3_3") (pintype "passive"))
    )
    (net (code "81") (name "Net-(IC2-PC4{slash}ADC12_IN14)") (class "Default")
      (node (ref "IC2") (pin "24") (pinfunction "PC4/ADC12_IN14_24") (pintype "bidirectional"))
      (node (ref "JP_AL") (pin "3") (pinfunction "3_3") (pintype "passive"))
    )
    (net (code "82") (name "Net-(IC2-PD0{slash}OSC_IN{slash}FSMC_D2{slash}CAN_RX{slash}FT)") (class "Default")
      (node (ref "C53") (pin "2") (pinfunction "2_2") (pintype "passive"))
      (node (ref "IC2") (pin "5") (pinfunction "PD0/OSC_IN/FSMC_D2/CAN_RX/FT_5") (pintype "bidirectional"))
      (node (ref "Y1") (pin "P$1") (pinfunction "1_P$1") (pintype "passive"))
    )
    (net (code "83") (name "Net-(IC2-PD1{slash}OSC_OUT{slash}FSMC_D3{slash}CAN_TX{slash}FT)") (class "Default")
      (node (ref "IC2") (pin "6") (pinfunction "PD1/OSC_OUT/FSMC_D3/CAN_TX/FT_6") (pintype "bidirectional"))
      (node (ref "R6") (pin "2") (pinfunction "2_2") (pintype "passive"))
    )
    (net (code "84") (name "Net-(IC3-NR)") (class "Default")
      (node (ref "C74") (pin "1") (pinfunction "1_1") (pintype "passive"))
      (node (ref "IC3") (pin "4") (pinfunction "NR_4") (pintype "bidirectional"))
    )
    (net (code "85") (name "Net-(IC4-A)") (class "Default")
      (node (ref "C2") (pin "1") (pinfunction "1_1") (pintype "passive"))
      (node (ref "IC4") (pin "2") (pinfunction "A_2") (pintype "bidirectional"))
      (node (ref "R1") (pin "1") (pinfunction "1_1") (pintype "passive"))
      (node (ref "XT1") (pin "A") (pinfunction "A_A") (pintype "bidirectional"))
    )
    (net (code "86") (name "Net-(IC4-Y)") (class "Default")
      (node (ref "IC4") (pin "4") (pinfunction "Y_4") (pintype "bidirectional"))
      (node (ref "R2") (pin "1") (pinfunction "1_1") (pintype "passive"))
    )
    (net (code "87") (name "Net-(IC5A-+IN)") (class "Default")
      (node (ref "IC5") (pin "1") (pinfunction "+IN_1") (pintype "input"))
      (node (ref "R20") (pin "2") (pinfunction "2_2") (pintype "passive"))
    )
    (net (code "88") (name "Net-(IC5B-+IN)") (class "Default")
      (node (ref "IC5") (pin "3") (pinfunction "+IN_3") (pintype "input"))
      (node (ref "R21") (pin "2") (pinfunction "2_2") (pintype "passive"))
    )
    (net (code "89") (name "Net-(IC6A-+IN)") (class "Default")
      (node (ref "IC6") (pin "3") (pinfunction "+IN_3") (pintype "input"))
      (node (ref "R10") (pin "2") (pinfunction "2_2") (pintype "passive"))
      (node (ref "R9") (pin "1") (pinfunction "1_1") (pintype "passive"))
    )
    (net (code "90") (name "Net-(IC6B-+IN)") (class "Default")
      (node (ref "C12") (pin "2") (pinfunction "2_2") (pintype "passive"))
      (node (ref "IC6") (pin "5") (pinfunction "+IN_5") (pintype "input"))
      (node (ref "R12") (pin "2") (pinfunction "2_2") (pintype "passive"))
    )
    (net (code "91") (name "Net-(IC6B--IN)") (class "Default")
      (node (ref "C13") (pin "1") (pinfunction "1_1") (pintype "passive"))
      (node (ref "IC6") (pin "6") (pinfunction "-IN_6") (pintype "input"))
      (node (ref "R13") (pin "2") (pinfunction "2_2") (pintype "passive"))
      (node (ref "R14") (pin "1") (pinfunction "1_1") (pintype "passive"))
    )
    (net (code "92") (name "Net-(IC6C-+IN)") (class "Default")
      (node (ref "C16") (pin "2") (pinfunction "2_2") (pintype "passive"))
      (node (ref "IC6") (pin "10") (pinfunction "+IN_10") (pintype "input"))
      (node (ref "R17") (pin "2") (pinfunction "2_2") (pintype "passive"))
      (node (ref "R36") (pin "2") (pinfunction "2_2") (pintype "passive"))
      (node (ref "R37") (pin "2") (pinfunction "2_2") (pintype "passive"))
    )
    (net (code "93") (name "Net-(IC6C--IN)") (class "Default")
      (node (ref "C17") (pin "1") (pinfunction "1_1") (pintype "passive"))
      (node (ref "IC6") (pin "9") (pinfunction "-IN_9") (pintype "input"))
      (node (ref "R18") (pin "1") (pinfunction "1_1") (pintype "passive"))
      (node (ref "R19") (pin "2") (pinfunction "2_2") (pintype "passive"))
    )
    (net (code "94") (name "Net-(IC7-OUT)") (class "Default")
      (node (ref "IC7") (pin "1") (pinfunction "OUT_1") (pintype "bidirectional"))
      (node (ref "R5") (pin "1") (pinfunction "1_1") (pintype "passive"))
    )
    (net (code "95") (name "Net-(IC8-REFB)") (class "Default")
      (node (ref "C18") (pin "1") (pinfunction "1_1") (pintype "passive"))
      (node (ref "IC8") (pin "23") (pinfunction "REFB_23") (pintype "bidirectional"))
      (node (ref "R53") (pin "1") (pinfunction "1_1") (pintype "passive"))
      (node (ref "R54") (pin "2") (pinfunction "2_2") (pintype "passive"))
    )
    (net (code "96") (name "Net-(IC8-REFT)") (class "Default")
      (node (ref "C19") (pin "1") (pinfunction "1_1") (pintype "passive"))
      (node (ref "IC8") (pin "17") (pinfunction "REFT_17") (pintype "bidirectional"))
      (node (ref "R52") (pin "1") (pinfunction "1_1") (pintype "passive"))
      (node (ref "R53") (pin "2") (pinfunction "2_2") (pintype "passive"))
    )
    (net (code "97") (name "Net-(IC9-1Y1)") (class "Default")
      (node (ref "IC9") (pin "12") (pinfunction "1Y4_12") (pintype "bidirectional"))
      (node (ref "IC9") (pin "14") (pinfunction "1Y3_14") (pintype "bidirectional"))
      (node (ref "IC9") (pin "16") (pinfunction "1Y2_16") (pintype "bidirectional"))
      (node (ref "IC9") (pin "18") (pinfunction "1Y1_18") (pintype "bidirectional"))
      (node (ref "R27") (pin "1") (pinfunction "1_1") (pintype "passive"))
    )
    (net (code "98") (name "Net-(IC9-2Y1)") (class "Default")
      (node (ref "IC9") (pin "9") (pinfunction "2Y1_9") (pintype "bidirectional"))
      (node (ref "R45") (pin "1") (pinfunction "1_1") (pintype "passive"))
    )
    (net (code "99") (name "Net-(IC9-2Y2)") (class "Default")
      (node (ref "IC9") (pin "3") (pinfunction "2Y4_3") (pintype "bidirectional"))
      (node (ref "IC9") (pin "5") (pinfunction "2Y3_5") (pintype "bidirectional"))
      (node (ref "IC9") (pin "7") (pinfunction "2Y2_7") (pintype "bidirectional"))
      (node (ref "R22") (pin "1") (pinfunction "1_1") (pintype "passive"))
    )
    (net (code "100") (name "Net-(IC10-1Y1)") (class "Default")
      (node (ref "IC10") (pin "12") (pinfunction "1Y4_12") (pintype "bidirectional"))
      (node (ref "IC10") (pin "14") (pinfunction "1Y3_14") (pintype "bidirectional"))
      (node (ref "IC10") (pin "16") (pinfunction "1Y2_16") (pintype "bidirectional"))
      (node (ref "IC10") (pin "18") (pinfunction "1Y1_18") (pintype "bidirectional"))
      (node (ref "R28") (pin "1") (pinfunction "1_1") (pintype "passive"))
    )
    (net (code "101") (name "Net-(IC10-2Y1)") (class "Default")
      (node (ref "IC10") (pin "9") (pinfunction "2Y1_9") (pintype "bidirectional"))
      (node (ref "R46") (pin "1") (pinfunction "1_1") (pintype "passive"))
    )
    (net (code "102") (name "Net-(IC10-2Y2)") (class "Default")
      (node (ref "IC10") (pin "3") (pinfunction "2Y4_3") (pintype "bidirectional"))
      (node (ref "IC10") (pin "5") (pinfunction "2Y3_5") (pintype "bidirectional"))
      (node (ref "IC10") (pin "7") (pinfunction "2Y2_7") (pintype "bidirectional"))
      (node (ref "R29") (pin "1") (pinfunction "1_1") (pintype "passive"))
    )
    (net (code "103") (name "Net-(IC11-A1)") (class "Default")
      (node (ref "C41") (pin "2") (pinfunction "2_2") (pintype "passive"))
      (node (ref "IC11") (pin "1") (pinfunction "A1_1") (pintype "passive"))
      (node (ref "IC14") (pin "7") (pinfunction "OUT_7") (pintype "output"))
      (node (ref "R34") (pin "2") (pinfunction "2_2") (pintype "passive"))
    )
    (net (code "104") (name "Net-(IC11-A2)") (class "Default")
      (node (ref "C13") (pin "2") (pinfunction "2_2") (pintype "passive"))
      (node (ref "IC11") (pin "4") (pinfunction "A2_4") (pintype "passive"))
      (node (ref "IC6") (pin "7") (pinfunction "OUT_7") (pintype "output"))
      (node (ref "R14") (pin "2") (pinfunction "2_2") (pintype "passive"))
    )
    (net (code "105") (name "Net-(IC11-A3)") (class "Default")
      (node (ref "C40") (pin "2") (pinfunction "2_2") (pintype "passive"))
      (node (ref "IC11") (pin "8") (pinfunction "A3_8") (pintype "passive"))
      (node (ref "IC14") (pin "1") (pinfunction "OUT_1") (pintype "output"))
      (node (ref "R33") (pin "2") (pinfunction "2_2") (pintype "passive"))
    )
    (net (code "106") (name "Net-(IC11-A4)") (class "Default")
      (node (ref "C17") (pin "2") (pinfunction "2_2") (pintype "passive"))
      (node (ref "IC11") (pin "11") (pinfunction "A4_11") (pintype "passive"))
      (node (ref "IC6") (pin "8") (pinfunction "OUT_8") (pintype "output"))
      (node (ref "R18") (pin "2") (pinfunction "2_2") (pintype "passive"))
    )
    (net (code "107") (name "Net-(IC13-NR)") (class "Default")
      (node (ref "C75") (pin "1") (pinfunction "1_1") (pintype "passive"))
      (node (ref "IC13") (pin "4") (pinfunction "NR_4") (pintype "bidirectional"))
    )
    (net (code "108") (name "Net-(IC14A-+IN)") (class "Default")
      (node (ref "IC14") (pin "3") (pinfunction "+IN_3") (pintype "input"))
      (node (ref "R35") (pin "2") (pinfunction "2_2") (pintype "passive"))
      (node (ref "R49") (pin "2") (pinfunction "2_2") (pintype "passive"))
    )
    (net (code "109") (name "Net-(IC14A--IN)") (class "Default")
      (node (ref "C40") (pin "1") (pinfunction "1_1") (pintype "passive"))
      (node (ref "IC14") (pin "2") (pinfunction "-IN_2") (pintype "input"))
      (node (ref "R33") (pin "1") (pinfunction "1_1") (pintype "passive"))
      (node (ref "R51") (pin "2") (pinfunction "2_2") (pintype "passive"))
    )
    (net (code "110") (name "Net-(IC14B-+IN)") (class "Default")
      (node (ref "IC14") (pin "5") (pinfunction "+IN_5") (pintype "input"))
      (node (ref "R32") (pin "2") (pinfunction "2_2") (pintype "passive"))
      (node (ref "R48") (pin "2") (pinfunction "2_2") (pintype "passive"))
    )
    (net (code "111") (name "Net-(IC14B--IN)") (class "Default")
      (node (ref "C41") (pin "1") (pinfunction "1_1") (pintype "passive"))
      (node (ref "IC14") (pin "6") (pinfunction "-IN_6") (pintype "input"))
      (node (ref "R34") (pin "1") (pinfunction "1_1") (pintype "passive"))
      (node (ref "R50") (pin "2") (pinfunction "2_2") (pintype "passive"))
    )
    (net (code "112") (name "Net-(LED3-PadA)") (class "Default")
      (node (ref "LED3") (pin "A") (pinfunction "A_A") (pintype "passive"))
      (node (ref "R65") (pin "2") (pinfunction "2_2") (pintype "passive"))
    )
    (net (code "113") (name "Net-(Q1-B)") (class "Default")
      (node (ref "Q1") (pin "1") (pinfunction "B_1") (pintype "bidirectional"))
      (node (ref "R40") (pin "2") (pinfunction "2_2") (pintype "passive"))
    )
    (net (code "114") (name "Net-(Q2-PadB)") (class "Default")
      (node (ref "Q2") (pin "B") (pinfunction "B_B") (pintype "passive"))
      (node (ref "Q4") (pin "C") (pinfunction "C_C") (pintype "passive"))
      (node (ref "R56") (pin "2") (pinfunction "2_2") (pintype "passive"))
      (node (ref "R67") (pin "2") (pinfunction "2_2") (pintype "passive"))
    )
    (net (code "115") (name "Net-(Q2-PadE)") (class "Default")
      (node (ref "Q2") (pin "E") (pinfunction "E_E") (pintype "passive"))
      (node (ref "R68") (pin "2") (pinfunction "2_2") (pintype "passive"))
    )
    (net (code "116") (name "Net-(Q3-B)") (class "Default")
      (node (ref "Q3") (pin "1") (pinfunction "B_1") (pintype "passive"))
      (node (ref "R319") (pin "1") (pinfunction "1_1") (pintype "passive"))
    )
    (net (code "117") (name "Net-(Q3-C)") (class "Default")
      (node (ref "BUZ1") (pin "2") (pinfunction "2_2") (pintype "passive"))
      (node (ref "Q3") (pin "3") (pinfunction "C_3") (pintype "passive"))
    )
    (net (code "118") (name "Net-(Q4-PadB)") (class "Default")
      (node (ref "Q4") (pin "B") (pinfunction "B_B") (pintype "passive"))
      (node (ref "R57") (pin "2") (pinfunction "2_2") (pintype "passive"))
      (node (ref "R58") (pin "2") (pinfunction "2_2") (pintype "passive"))
    )
    (net (code "119") (name "Net-(R37-Pad1)") (class "Default")
      (node (ref "R37") (pin "1") (pinfunction "1_1") (pintype "passive"))
      (node (ref "R38") (pin "2") (pinfunction "2_2") (pintype "passive"))
    )
    (net (code "120") (name "Net-(RLY1A-NC)") (class "Default")
      (node (ref "C14") (pin "1") (pinfunction "1_1") (pintype "passive"))
      (node (ref "R21") (pin "1") (pinfunction "1_1") (pintype "passive"))
      (node (ref "RLY1") (pin "3") (pinfunction "NC_3") (pintype "passive"))
    )
    (net (code "121") (name "Net-(RLY1A-NO)") (class "Default")
      (node (ref "C42") (pin "1") (pinfunction "1_1") (pintype "passive"))
      (node (ref "RLY1") (pin "5") (pinfunction "NO_5") (pintype "passive"))
    )
    (net (code "122") (name "Net-(RLY1B-NO)") (class "Default")
      (node (ref "C43") (pin "1") (pinfunction "1_1") (pintype "passive"))
      (node (ref "RLY1") (pin "8") (pinfunction "NO_8") (pintype "passive"))
    )
    (net (code "123") (name "Net-(SV2-PIN1)") (class "Default")
      (node (ref "R22") (pin "2") (pinfunction "2_2") (pintype "passive"))
      (node (ref "R28") (pin "2") (pinfunction "2_2") (pintype "passive"))
      (node (ref "R46") (pin "2") (pinfunction "2_2") (pintype "passive"))
      (node (ref "SV2") (pin "1") (pinfunction "PIN1_1") (pintype "passive"))
      (node (ref "TP5") (pin "1") (pinfunction "P$1_1") (pintype "bidirectional"))
    )
    (net (code "124") (name "Net-(SV2-PIN3)") (class "Default")
      (node (ref "R27") (pin "2") (pinfunction "2_2") (pintype "passive"))
      (node (ref "R29") (pin "2") (pinfunction "2_2") (pintype "passive"))
      (node (ref "R45") (pin "2") (pinfunction "2_2") (pintype "passive"))
      (node (ref "SV2") (pin "3") (pinfunction "PIN3_3") (pintype "passive"))
      (node (ref "TP4") (pin "1") (pinfunction "P$1_1") (pintype "bidirectional"))
    )
    (net (code "125") (name "Net-(U$7A-TEMP)") (class "Default")
      (node (ref "C60") (pin "1") (pinfunction "1_1") (pintype "passive"))
      (node (ref "R26") (pin "2") (pinfunction "2_2") (pintype "passive"))
      (node (ref "R43") (pin "2") (pinfunction "2_2") (pintype "passive"))
      (node (ref "U$7") (pin "6") (pinfunction "TEMP_6") (pintype "bidirectional"))
    )
    (net (code "126") (name "Net-(U$7A-VREF)") (class "Default")
      (node (ref "R26") (pin "1") (pinfunction "1_1") (pintype "passive"))
      (node (ref "U$7") (pin "7") (pinfunction "VREF_7") (pintype "bidirectional"))
    )
    (net (code "127") (name "Net-(U$7A-~{GRN})") (class "Default")
      (node (ref "R24") (pin "2") (pinfunction "2_2") (pintype "passive"))
      (node (ref "U$7") (pin "2") (pinfunction "~{GRN}_2") (pintype "bidirectional"))
    )
    (net (code "128") (name "Net-(U$7A-~{RED})") (class "Default")
      (node (ref "R25") (pin "2") (pinfunction "2_2") (pintype "passive"))
      (node (ref "U$7") (pin "3") (pinfunction "~{RED}_3") (pintype "bidirectional"))
    )
    (net (code "129") (name "Net-(U1-A)") (class "Default")
      (node (ref "F1") (pin "1") (pinfunction "1_1") (pintype "passive"))
      (node (ref "U1") (pin "1") (pinfunction "A_1") (pintype "bidirectional"))
    )
    (net (code "130") (name "Net-(U2A-L40N_2)") (class "Default")
      (node (ref "R44") (pin "2") (pinfunction "2_2") (pintype "passive"))
      (node (ref "U2") (pin "65") (pinfunction "L40N_2_65") (pintype "bidirectional"))
    )
    (net (code "131") (name "Net-(U2A-L40P_2{slash}VREF_2)") (class "Default")
      (node (ref "R39") (pin "2") (pinfunction "2_2") (pintype "passive"))
      (node (ref "U2") (pin "64") (pinfunction "L40P_2/VREF_2_64") (pintype "bidirectional"))
    )
    (net (code "132") (name "Net-(U3-C1N)") (class "Default")
      (node (ref "C5") (pin "2") (pinfunction "2_2") (pintype "passive"))
      (node (ref "U3") (pin "5") (pinfunction "C1N_5") (pintype "input"))
    )
    (net (code "133") (name "Net-(U3-C1P)") (class "Default")
      (node (ref "C5") (pin "1") (pinfunction "1_1") (pintype "passive"))
      (node (ref "U3") (pin "4") (pinfunction "C1P_4") (pintype "input"))
    )
    (net (code "134") (name "Net-(U3-C2N)") (class "Default")
      (node (ref "C4") (pin "2") (pinfunction "2_2") (pintype "passive"))
      (node (ref "U3") (pin "3") (pinfunction "C2N_3") (pintype "input"))
    )
    (net (code "135") (name "Net-(U3-C2P)") (class "Default")
      (node (ref "C4") (pin "1") (pinfunction "1_1") (pintype "passive"))
      (node (ref "U3") (pin "2") (pinfunction "C2P_2") (pintype "input"))
    )
    (net (code "136") (name "Net-(U3-IREF)") (class "Default")
      (node (ref "R3") (pin "2") (pinfunction "2_2") (pintype "passive"))
      (node (ref "U3") (pin "26") (pinfunction "IREF_26") (pintype "input"))
    )
    (net (code "137") (name "Net-(U3-VCC)") (class "Default")
      (node (ref "C6") (pin "1") (pinfunction "1_1") (pintype "passive"))
      (node (ref "U3") (pin "28") (pinfunction "VCC_28") (pintype "power_in"))
    )
    (net (code "138") (name "Net-(U3-VCOMH)") (class "Default")
      (node (ref "C8") (pin "1") (pinfunction "1_1") (pintype "passive"))
      (node (ref "U3") (pin "27") (pinfunction "VCOMH_27") (pintype "output"))
    )
    (net (code "139") (name "Net-(Y1-2)") (class "Default")
      (node (ref "C54") (pin "2") (pinfunction "2_2") (pintype "passive"))
      (node (ref "R6") (pin "1") (pinfunction "1_1") (pintype "passive"))
      (node (ref "Y1") (pin "P$2") (pinfunction "2_P$2") (pintype "passive"))
    )
    (net (code "140") (name "ONOFF") (class "Default")
      (node (ref "IC1") (pin "6") (pinfunction "EN_6") (pintype "input"))
      (node (ref "S1") (pin "2") (pinfunction "P_2") (pintype "passive"))
    )
    (net (code "141") (name "PCK0") (class "Default")
      (node (ref "IC2") (pin "43") (pinfunction "PA10/USART1_RX/TIM1_CH3/FT_43") (pintype "bidirectional"))
      (node (ref "PCK0_TP") (pin "1") (pinfunction "P$1_1") (pintype "bidirectional"))
      (node (ref "U2") (pin "88") (pinfunction "L32N_1/GCLK5_88") (pintype "bidirectional"))
    )
    (net (code "142") (name "PS") (class "Default")
      (node (ref "IC1") (pin "8") (pinfunction "PS_8") (pintype "input"))
      (node (ref "JP2") (pin "2") (pinfunction "2_2") (pintype "passive"))
    )
    (net (code "143") (name "PWR_HI") (class "Default")
      (node (ref "IC10") (pin "13") (pinfunction "2A2_13") (pintype "bidirectional"))
      (node (ref "IC10") (pin "15") (pinfunction "2A3_15") (pintype "bidirectional"))
      (node (ref "IC10") (pin "17") (pinfunction "2A4_17") (pintype "bidirectional"))
      (node (ref "IC9") (pin "11") (pinfunction "2A1_11") (pintype "bidirectional"))
      (node (ref "IC9") (pin "2") (pinfunction "1A1_2") (pintype "bidirectional"))
      (node (ref "IC9") (pin "4") (pinfunction "1A2_4") (pintype "bidirectional"))
      (node (ref "IC9") (pin "6") (pinfunction "1A3_6") (pintype "bidirectional"))
      (node (ref "IC9") (pin "8") (pinfunction "1A4_8") (pintype "bidirectional"))
      (node (ref "PWR_HI_TP") (pin "1") (pinfunction "P$1_1") (pintype "bidirectional"))
      (node (ref "U2") (pin "61") (pinfunction "L24N_3_61") (pintype "bidirectional"))
    )
    (net (code "144") (name "PWR_LO") (class "Default")
      (node (ref "IC10") (pin "11") (pinfunction "2A1_11") (pintype "bidirectional"))
      (node (ref "IC10") (pin "2") (pinfunction "1A1_2") (pintype "bidirectional"))
      (node (ref "IC10") (pin "4") (pinfunction "1A2_4") (pintype "bidirectional"))
      (node (ref "IC10") (pin "6") (pinfunction "1A3_6") (pintype "bidirectional"))
      (node (ref "IC10") (pin "8") (pinfunction "1A4_8") (pintype "bidirectional"))
      (node (ref "IC9") (pin "13") (pinfunction "2A2_13") (pintype "bidirectional"))
      (node (ref "IC9") (pin "15") (pinfunction "2A3_15") (pintype "bidirectional"))
      (node (ref "IC9") (pin "17") (pinfunction "2A4_17") (pintype "bidirectional"))
      (node (ref "PWR_LO_TP") (pin "1") (pinfunction "P$1_1") (pintype "bidirectional"))
      (node (ref "U2") (pin "62") (pinfunction "L40P_3_62") (pintype "bidirectional"))
    )
    (net (code "145") (name "PWR_OE1") (class "Default")
      (node (ref "IC9") (pin "1") (pinfunction "1NOE_1") (pintype "bidirectional"))
      (node (ref "OE1_TP") (pin "1") (pinfunction "P$1_1") (pintype "bidirectional"))
      (node (ref "U2") (pin "44") (pinfunction "L30N_4/D2_44") (pintype "bidirectional"))
    )
    (net (code "146") (name "PWR_OE2") (class "Default")
      (node (ref "IC10") (pin "1") (pinfunction "1NOE_1") (pintype "bidirectional"))
      (node (ref "OE2_TP") (pin "1") (pinfunction "P$1_1") (pintype "bidirectional"))
      (node (ref "U2") (pin "47") (pinfunction "L27P_4/D1_47") (pintype "bidirectional"))
    )
    (net (code "147") (name "PWR_OE3") (class "Default")
      (node (ref "IC9") (pin "19") (pinfunction "2NOE_19") (pintype "bidirectional"))
      (node (ref "OE3_TP") (pin "1") (pinfunction "P$1_1") (pintype "bidirectional"))
      (node (ref "U2") (pin "71") (pinfunction "L21P_2_71") (pintype "bidirectional"))
    )
    (net (code "148") (name "PWR_OE4") (class "Default")
      (node (ref "IC10") (pin "19") (pinfunction "2NOE_19") (pintype "bidirectional"))
      (node (ref "OE4_TP") (pin "1") (pinfunction "P$1_1") (pintype "bidirectional"))
      (node (ref "U2") (pin "72") (pinfunction "L21N_2_72") (pintype "bidirectional"))
    )
    (net (code "149") (name "RELAY_ON") (class "Default")
      (node (ref "IC2") (pin "25") (pinfunction "PC5/ADC12_IN15_25") (pintype "bidirectional"))
      (node (ref "R40") (pin "1") (pinfunction "1_1") (pintype "passive"))
      (node (ref "RELAY_ON_TP") (pin "1") (pinfunction "P$1_1") (pintype "bidirectional"))
    )
    (net (code "150") (name "SCLK{slash}DB0") (class "Default")
      (node (ref "IC2") (pin "21") (pinfunction "PA5/SPI1_SCK/DAC_OUT2/ADC12_IN5_21") (pintype "bidirectional"))
      (node (ref "TP54") (pin "1") (pinfunction "P$1_1") (pintype "bidirectional"))
      (node (ref "U3") (pin "18") (pinfunction "D0/SPI_SCLK/I2C_SCK_18") (pintype "bidirectional"))
    )
    (net (code "151") (name "SDIN{slash}DB1") (class "Default")
      (node (ref "IC2") (pin "22") (pinfunction "PA6/SPI1_MISO/TIM8_BKIN/ADC12_IN6/TIM3_CH1/TIM1_BKIN_22") (pintype "bidirectional"))
      (node (ref "R66") (pin "1") (pinfunction "1_1") (pintype "passive"))
      (node (ref "SJ1") (pin "1") (pinfunction "1_1") (pintype "passive"))
      (node (ref "TP55") (pin "1") (pinfunction "P$1_1") (pintype "bidirectional"))
      (node (ref "U3") (pin "19") (pinfunction "D1/SPI_SDIN/I2C_SDA_19") (pintype "bidirectional"))
    )
    (net (code "152") (name "SD_MISO") (class "Default")
      (node (ref "IC2") (pin "56") (pinfunction "PB4/JNTRST/SPI3_MISO/TIM3_CH1/SPI1_MISO_56") (pintype "input"))
      (node (ref "R62") (pin "1") (pinfunction "1_1") (pintype "passive"))
      (node (ref "TP11") (pin "1") (pinfunction "P$1_1") (pintype "bidirectional"))
      (node (ref "U4") (pin "7") (pinfunction "DO_7") (pintype "bidirectional"))
    )
    (net (code "153") (name "SD_MOSI") (class "Default")
      (node (ref "IC2") (pin "57") (pinfunction "PB5/I2C1_SMBA/SPI3_MOSI/I2S3_SD/TIM3_CH2/SPI1_MOSI_57") (pintype "bidirectional"))
      (node (ref "R63") (pin "1") (pinfunction "1_1") (pintype "passive"))
      (node (ref "TP32") (pin "1") (pinfunction "P$1_1") (pintype "bidirectional"))
      (node (ref "U4") (pin "3") (pinfunction "DI_3") (pintype "bidirectional"))
    )
    (net (code "154") (name "SD_RSV") (class "Default")
      (node (ref "R61") (pin "1") (pinfunction "1_1") (pintype "passive"))
      (node (ref "U4") (pin "8") (pinfunction "RSV_8") (pintype "bidirectional"))
    )
    (net (code "155") (name "SD_SCK{slash}TDO") (class "Default")
      (node (ref "IC2") (pin "55") (pinfunction "PB3/JTDO/SPI3_SCK/I2S3_CK/TIM2_CH2/SPI1_SCK/TRACESWO_55") (pintype "output"))
      (node (ref "JP4") (pin "3") (pinfunction "3_3") (pintype "passive"))
      (node (ref "TP6") (pin "1") (pinfunction "P$1_1") (pintype "bidirectional"))
      (node (ref "U4") (pin "5") (pinfunction "SCK_5") (pintype "bidirectional"))
    )
    (net (code "156") (name "SPCK") (class "Default")
      (node (ref "IC2") (pin "2") (pinfunction "PC13/TAMPER-RTC_2") (pintype "bidirectional"))
      (node (ref "SPCK_TP") (pin "1") (pinfunction "P$1_1") (pintype "bidirectional"))
      (node (ref "U2") (pin "1") (pinfunction "L01P_7/VRN_7_1") (pintype "bidirectional"))
    )
    (net (code "157") (name "SPEAKER") (class "Default")
      (node (ref "IC2") (pin "37") (pinfunction "PC6/I2S2_MCK/TIM8_CH1/SDIO_D6/TIM3_CH1/FT_37") (pintype "bidirectional"))
      (node (ref "R319") (pin "2") (pinfunction "2_2") (pintype "passive"))
    )
    (net (code "158") (name "SSP_CLK") (class "Default")
      (node (ref "IC2") (pin "34") (pinfunction "PB13/SPI2_SCK/I2S2_CK/USART3_CTS/TIM1_CH1N/FT_34") (pintype "bidirectional"))
      (node (ref "TP50") (pin "1") (pinfunction "P$1_1") (pintype "bidirectional"))
      (node (ref "U2") (pin "9") (pinfunction "L23N_7_9") (pintype "bidirectional"))
    )
    (net (code "159") (name "SSP_MISO") (class "Default")
      (node (ref "IC2") (pin "35") (pinfunction "PB14/SPI2_MISO/TIM1_CH2N/USART3_RTS/FT_35") (pintype "bidirectional"))
      (node (ref "TP49") (pin "1") (pinfunction "P$1_1") (pintype "bidirectional"))
      (node (ref "U2") (pin "8") (pinfunction "L23P_7_8") (pintype "bidirectional"))
    )
    (net (code "160") (name "SSP_MOSI") (class "Default")
      (node (ref "IC2") (pin "36") (pinfunction "PB15/SPI2_MOSI/TIM1_CH3N/I2S2_SD/FT_36") (pintype "bidirectional"))
      (node (ref "TP48") (pin "1") (pinfunction "P$1_1") (pintype "bidirectional"))
      (node (ref "U2") (pin "5") (pinfunction "L21N_7_5") (pintype "bidirectional"))
    )
    (net (code "161") (name "SSP_NSS") (class "Default")
      (node (ref "IC2") (pin "33") (pinfunction "PB12/SPI2_NSS/I2C2_WS/I2C2_SMBA/USART3_CK/TIM1_BKIN/FT_33") (pintype "bidirectional"))
      (node (ref "TP51") (pin "1") (pinfunction "P$1_1") (pintype "bidirectional"))
      (node (ref "U2") (pin "4") (pinfunction "L21P_7_4") (pintype "bidirectional"))
    )
    (net (code "162") (name "SW_K1") (class "Default")
      (node (ref "IC2") (pin "62") (pinfunction "PB9/TIM4_CH4/SDIO_D5/I2C1_SDA/CAN_TX/FT_62") (pintype "bidirectional"))
      (node (ref "K1") (pin "2") (pinfunction "S_2") (pintype "passive"))
      (node (ref "R71") (pin "1") (pinfunction "1_1") (pintype "passive"))
    )
    (net (code "163") (name "SW_K2") (class "Default")
      (node (ref "IC2") (pin "17") (pinfunction "PA3/USART2_RX/TIM5_CH4/ADC123_IN3/TIM2_CH4_17") (pintype "bidirectional"))
      (node (ref "K2") (pin "2") (pinfunction "S_2") (pintype "passive"))
      (node (ref "R70") (pin "1") (pinfunction "1_1") (pintype "passive"))
    )
    (net (code "164") (name "SW_K3") (class "Default")
      (node (ref "IC2") (pin "16") (pinfunction "PA2/USART2_TX/TIM5_CH3/ADC123_IN2/TIM2_CH3_16") (pintype "bidirectional"))
      (node (ref "K3") (pin "2") (pinfunction "S_2") (pintype "passive"))
      (node (ref "R69") (pin "1") (pinfunction "1_1") (pintype "passive"))
    )
    (net (code "165") (name "USBD_N") (class "Default")
      (node (ref "D6") (pin "2") (pinfunction "P$2_2") (pintype "passive"))
      (node (ref "R7") (pin "1") (pinfunction "1_1") (pintype "passive"))
      (node (ref "SV1") (pin "2") (pinfunction "D-/2_2") (pintype "bidirectional"))
      (node (ref "USB-MICRO") (pin "D-") (pinfunction "D-_D-") (pintype "bidirectional"))
    )
    (net (code "166") (name "USBD_P") (class "Default")
      (node (ref "D6") (pin "3") (pinfunction "P$3_3") (pintype "passive"))
      (node (ref "R68") (pin "1") (pinfunction "1_1") (pintype "passive"))
      (node (ref "R8") (pin "1") (pinfunction "1_1") (pintype "passive"))
      (node (ref "SV1") (pin "3") (pinfunction "D+/3_3") (pintype "bidirectional"))
      (node (ref "USB-MICRO") (pin "D+") (pinfunction "D+_D+") (pintype "bidirectional"))
    )
    (net (code "167") (name "USB_ON") (class "Default")
      (node (ref "IC2") (pin "29") (pinfunction "PB10/I2C2_SCL/USART3_TX/TIM2_CH3/FT_29") (pintype "bidirectional"))
      (node (ref "R58") (pin "1") (pinfunction "1_1") (pintype "passive"))
      (node (ref "TP23") (pin "1") (pinfunction "P$1_1") (pintype "bidirectional"))
    )
    (net (code "168") (name "VBAT+") (class "Default")
      (node (ref "C61") (pin "1") (pinfunction "1_1") (pintype "passive"))
      (node (ref "C62") (pin "1") (pinfunction "1_1") (pintype "passive"))
      (node (ref "IC1") (pin "5") (pinfunction "VIN_5") (pintype "input"))
      (node (ref "JP2") (pin "3") (pinfunction "3_3") (pintype "passive"))
      (node (ref "L2") (pin "P$1") (pinfunction "1_P$1") (pintype "passive"))
      (node (ref "R55") (pin "2") (pinfunction "2_2") (pintype "passive"))
      (node (ref "S1") (pin "3") (pinfunction "S_3") (pintype "passive"))
      (node (ref "TP9") (pin "1") (pinfunction "P$1_1") (pintype "bidirectional"))
      (node (ref "U$7") (pin "8") (pinfunction "BAT_8") (pintype "bidirectional"))
      (node (ref "U$9") (pin "3") (pinfunction "POS_3") (pintype "power_in"))
    )
    (net (code "169") (name "VBUS") (class "Default")
      (node (ref "C1") (pin "1") (pinfunction "1_1") (pintype "passive"))
      (node (ref "C59") (pin "1") (pinfunction "1_1") (pintype "passive"))
      (node (ref "LED1") (pin "A") (pinfunction "A_A") (pintype "passive"))
      (node (ref "LED2") (pin "A") (pinfunction "A_A") (pintype "passive"))
      (node (ref "R56") (pin "1") (pinfunction "1_1") (pintype "passive"))
      (node (ref "TP8") (pin "1") (pinfunction "P$1_1") (pintype "bidirectional"))
      (node (ref "U$7") (pin "1") (pinfunction "VIN_1") (pintype "bidirectional"))
      (node (ref "U1") (pin "2") (pinfunction "B_2") (pintype "bidirectional"))
    )
    (net (code "170") (name "VDD") (class "Default")
      (node (ref "C21") (pin "1") (pinfunction "1_1") (pintype "passive"))
      (node (ref "C22") (pin "1") (pinfunction "1_1") (pintype "passive"))
      (node (ref "C23") (pin "1") (pinfunction "1_1") (pintype "passive"))
      (node (ref "C24") (pin "1") (pinfunction "1_1") (pintype "passive"))
      (node (ref "C37") (pin "+") (pinfunction "+_+") (pintype "passive"))
      (node (ref "C38") (pin "+") (pinfunction "+_+") (pintype "passive"))
      (node (ref "C44") (pin "1") (pinfunction "1_1") (pintype "passive"))
      (node (ref "C46") (pin "1") (pinfunction "1_1") (pintype "passive"))
      (node (ref "C64") (pin "1") (pinfunction "1_1") (pintype "passive"))
      (node (ref "C71") (pin "1") (pinfunction "1_1") (pintype "passive"))
      (node (ref "C72") (pin "1") (pinfunction "1_1") (pintype "passive"))
      (node (ref "C73") (pin "+") (pinfunction "+_+") (pintype "passive"))
      (node (ref "D7") (pin "3") (pinfunction "C_3") (pintype "passive"))
      (node (ref "FB1") (pin "2") (pinfunction "B_2") (pintype "bidirectional"))
      (node (ref "FB2\\") (pin "2") (pinfunction "B_2") (pintype "bidirectional"))
      (node (ref "FB3") (pin "2") (pinfunction "B_2") (pintype "bidirectional"))
      (node (ref "IC1") (pin "10") (pinfunction "FB_10") (pintype "input"))
      (node (ref "IC1") (pin "2") (pinfunction "VOUT_2") (pintype "output"))
      (node (ref "IC10") (pin "20") (pinfunction "VDD_20") (pintype "bidirectional"))
      (node (ref "IC105") (pin "1") (pinfunction "VIN_1") (pintype "bidirectional"))
      (node (ref "IC106") (pin "1") (pinfunction "VIN_1") (pintype "bidirectional"))
      (node (ref "IC11") (pin "14") (pinfunction "VDD_14") (pintype "bidirectional"))
      (node (ref "IC13") (pin "1") (pinfunction "VIN_1") (pintype "bidirectional"))
      (node (ref "IC14") (pin "8") (pinfunction "V+_8") (pintype "bidirectional"))
      (node (ref "IC3") (pin "1") (pinfunction "VIN_1") (pintype "bidirectional"))
      (node (ref "IC3") (pin "3") (pinfunction "VC_3") (pintype "bidirectional"))
      (node (ref "IC5") (pin "8") (pinfunction "V+_8") (pintype "bidirectional"))
      (node (ref "IC6") (pin "4") (pinfunction "V+_4") (pintype "bidirectional"))
      (node (ref "IC8") (pin "11") (pinfunction "VDDD0_11") (pintype "bidirectional"))
      (node (ref "IC8") (pin "13") (pinfunction "VDDD1_13") (pintype "bidirectional"))
      (node (ref "IC9") (pin "20") (pinfunction "VDD_20") (pintype "bidirectional"))
      (node (ref "R47") (pin "1") (pinfunction "1_1") (pintype "passive"))
      (node (ref "R52") (pin "2") (pinfunction "2_2") (pintype "passive"))
      (node (ref "R9") (pin "2") (pinfunction "2_2") (pintype "passive"))
      (node (ref "RLY1") (pin "1") (pinfunction "P$1_1") (pintype "passive"))
      (node (ref "TP10") (pin "1") (pinfunction "P$1_1") (pintype "bidirectional"))
    )
    (net (code "171") (name "VDDA") (class "Default")
      (node (ref "C52") (pin "1") (pinfunction "1_1") (pintype "passive"))
      (node (ref "C55") (pin "A") (pinfunction "+_A") (pintype "passive"))
      (node (ref "IC2") (pin "13") (pinfunction "VDDA_13") (pintype "power_in"))
      (node (ref "L1") (pin "2") (pinfunction "P$2_2") (pintype "bidirectional"))
    )
    (net (code "172") (name "VMID") (class "Default")
      (node (ref "C10") (pin "1") (pinfunction "1_1") (pintype "passive"))
      (node (ref "C45") (pin "1") (pinfunction "1_1") (pintype "passive"))
      (node (ref "IC6") (pin "1") (pinfunction "OUT_1") (pintype "output"))
      (node (ref "IC6") (pin "2") (pinfunction "-IN_2") (pintype "input"))
      (node (ref "R12") (pin "1") (pinfunction "1_1") (pintype "passive"))
      (node (ref "R13") (pin "1") (pinfunction "1_1") (pintype "passive"))
      (node (ref "R17") (pin "1") (pinfunction "1_1") (pintype "passive"))
      (node (ref "R19") (pin "1") (pinfunction "1_1") (pintype "passive"))
      (node (ref "R36") (pin "1") (pinfunction "1_1") (pintype "passive"))
      (node (ref "R38") (pin "1") (pinfunction "1_1") (pintype "passive"))
      (node (ref "R48") (pin "1") (pinfunction "1_1") (pintype "passive"))
      (node (ref "R49") (pin "1") (pinfunction "1_1") (pintype "passive"))
      (node (ref "R50") (pin "1") (pinfunction "1_1") (pintype "passive"))
      (node (ref "R51") (pin "1") (pinfunction "1_1") (pintype "passive"))
    )
    (net (code "173") (name "unconnected-(IC2-PC0{slash}ADC123_IN10-Pad8)") (class "Default")
      (node (ref "IC2") (pin "8") (pinfunction "PC0/ADC123_IN10_8") (pintype "bidirectional"))
    )
    (net (code "174") (name "unconnected-(IC2-PC1{slash}ADC123_IN11-Pad9)") (class "Default")
      (node (ref "IC2") (pin "9") (pinfunction "PC1/ADC123_IN11_9") (pintype "bidirectional"))
    )
    (net (code "175") (name "unconnected-(IC2-PC2{slash}ADC123_IN12-Pad10)") (class "Default")
      (node (ref "IC2") (pin "10") (pinfunction "PC2/ADC123_IN12_10") (pintype "bidirectional"))
    )
    (net (code "176") (name "unconnected-(IC2-PC10{slash}UART4_TX{slash}SDIO_D2{slash}USART3_TX{slash}FT-Pad51)") (class "Default")
      (node (ref "IC2") (pin "51") (pinfunction "PC10/UART4_TX/SDIO_D2/USART3_TX/FT_51") (pintype "bidirectional"))
    )
    (net (code "177") (name "unconnected-(IC6D-OUT-Pad14)") (class "Default")
      (node (ref "IC6") (pin "14") (pinfunction "OUT_14") (pintype "output"))
    )
    (net (code "178") (name "unconnected-(IC8-REFBS-Pad22)") (class "Default")
      (node (ref "IC8") (pin "22") (pinfunction "REFBS_22") (pintype "bidirectional"))
    )
    (net (code "179") (name "unconnected-(IC8-REFTS-Pad16)") (class "Default")
      (node (ref "IC8") (pin "16") (pinfunction "REFTS_16") (pintype "bidirectional"))
    )
    (net (code "180") (name "unconnected-(IC105-NR-Pad4)") (class "Default")
      (node (ref "IC105") (pin "4") (pinfunction "NR_4") (pintype "bidirectional"))
    )
    (net (code "181") (name "unconnected-(IC106-NR-Pad4)") (class "Default")
      (node (ref "IC106") (pin "4") (pinfunction "NR_4") (pintype "bidirectional"))
    )
    (net (code "182") (name "unconnected-(SV1-ID{slash}4-Pad4)") (class "Default")
      (node (ref "SV1") (pin "4") (pinfunction "ID/4_4") (pintype "bidirectional"))
    )
    (net (code "183") (name "unconnected-(U2A-IO0_3-Pad55)") (class "Default")
      (node (ref "U2") (pin "55") (pinfunction "IO0_3_55") (pintype "bidirectional"))
    )
    (net (code "184") (name "unconnected-(U2A-IO0_6-Pad17)") (class "Default")
      (node (ref "U2") (pin "17") (pinfunction "IO0_6_17") (pintype "bidirectional"))
    )
    (net (code "185") (name "unconnected-(U2A-IO1_3-Pad59)") (class "Default")
      (node (ref "U2") (pin "59") (pinfunction "IO1_3_59") (pintype "bidirectional"))
    )
    (net (code "186") (name "unconnected-(U2A-IO1_6-Pad21)") (class "Default")
      (node (ref "U2") (pin "21") (pinfunction "IO1_6_21") (pintype "bidirectional"))
    )
    (net (code "187") (name "unconnected-(U2A-IO_1-Pad81)") (class "Default")
      (node (ref "U2") (pin "81") (pinfunction "IO_1_81") (pintype "bidirectional"))
    )
    (net (code "188") (name "unconnected-(U2A-L01N_0{slash}VRP_0-Pad97)") (class "Default")
      (node (ref "U2") (pin "97") (pinfunction "L01N_0/VRP_0_97") (pintype "bidirectional"))
    )
    (net (code "189") (name "unconnected-(U2A-L01N_1{slash}VRP_1-Pad80)") (class "Default")
      (node (ref "U2") (pin "80") (pinfunction "L01N_1/VRP_1_80") (pintype "bidirectional"))
    )
    (net (code "190") (name "unconnected-(U2A-L01N_3{slash}VRP_3-Pad54)") (class "Default")
      (node (ref "U2") (pin "54") (pinfunction "L01N_3/VRP_3_54") (pintype "bidirectional"))
    )
    (net (code "191") (name "unconnected-(U2A-L01N_6{slash}VRP_6-Pad23)") (class "Default")
      (node (ref "U2") (pin "23") (pinfunction "L01N_6/VRP_6_23") (pintype "bidirectional"))
    )
    (net (code "192") (name "unconnected-(U2A-L01N_7{slash}VRP_7-Pad2)") (class "Default")
      (node (ref "U2") (pin "2") (pinfunction "L01N_7/VRP_7_2") (pintype "bidirectional"))
    )
    (net (code "193") (name "unconnected-(U2A-L01P_0{slash}VRN_0-Pad96)") (class "Default")
      (node (ref "U2") (pin "96") (pinfunction "L01P_0/VRN_0_96") (pintype "bidirectional"))
    )
    (net (code "194") (name "unconnected-(U2A-L01P_1{slash}VRN_1-Pad79)") (class "Default")
      (node (ref "U2") (pin "79") (pinfunction "L01P_1/VRN_1_79") (pintype "bidirectional"))
    )
    (net (code "195") (name "unconnected-(U2A-L01P_2{slash}VRN_2-Pad74)") (class "Default")
      (node (ref "U2") (pin "74") (pinfunction "L01P_2/VRN_2_74") (pintype "bidirectional"))
    )
    (net (code "196") (name "unconnected-(U2A-L01P_3{slash}VRN_3-Pad53)") (class "Default")
      (node (ref "U2") (pin "53") (pinfunction "L01P_3/VRN_3_53") (pintype "bidirectional"))
    )
    (net (code "197") (name "unconnected-(U2A-L01P_6{slash}VRN_6-Pad22)") (class "Default")
      (node (ref "U2") (pin "22") (pinfunction "L01P_6/VRN_6_22") (pintype "bidirectional"))
    )
    (net (code "198") (name "unconnected-(U2A-L24N_2-Pad68)") (class "Default")
      (node (ref "U2") (pin "68") (pinfunction "L24N_2_68") (pintype "bidirectional"))
    )
    (net (code "199") (name "unconnected-(U2A-L24N_6{slash}VREF_6-Pad16)") (class "Default")
      (node (ref "U2") (pin "16") (pinfunction "L24N_6/VREF_6_16") (pintype "bidirectional"))
    )
    (net (code "200") (name "unconnected-(U2A-L24P_2-Pad67)") (class "Default")
      (node (ref "U2") (pin "67") (pinfunction "L24P_2_67") (pintype "bidirectional"))
    )
    (net (code "201") (name "unconnected-(U2A-L24P_3-Pad60)") (class "Default")
      (node (ref "U2") (pin "60") (pinfunction "L24P_3_60") (pintype "bidirectional"))
    )
    (net (code "202") (name "unconnected-(U2A-L31N_0-Pad92)") (class "Default")
      (node (ref "U2") (pin "92") (pinfunction "L31N_0_92") (pintype "bidirectional"))
    )
    (net (code "203") (name "unconnected-(U2A-L31N_1{slash}VREF_1-Pad86)") (class "Default")
      (node (ref "U2") (pin "86") (pinfunction "L31N_1/VREF_1_86") (pintype "bidirectional"))
    )
    (net (code "204") (name "unconnected-(U2A-L31P_0{slash}VREF_0-Pad91)") (class "Default")
      (node (ref "U2") (pin "91") (pinfunction "L31P_0/VREF_0_91") (pintype "bidirectional"))
    )
    (net (code "205") (name "unconnected-(U2A-L31P_1-Pad85)") (class "Default")
      (node (ref "U2") (pin "85") (pinfunction "L31P_1_85") (pintype "bidirectional"))
    )
    (net (code "206") (name "unconnected-(U2A-L32N_4{slash}GCLK1-Pad39)") (class "Default")
      (node (ref "U2") (pin "39") (pinfunction "L32N_4/GCLK1_39") (pintype "bidirectional"))
    )
    (net (code "207") (name "unconnected-(U2A-L32P_1{slash}GCLK4-Pad87)") (class "Default")
      (node (ref "U2") (pin "87") (pinfunction "L32P_1/GCLK4_87") (pintype "bidirectional"))
    )
    (net (code "208") (name "unconnected-(U2A-L40N_3{slash}VREF_3-Pad63)") (class "Default")
      (node (ref "U2") (pin "63") (pinfunction "L40N_3/VREF_3_63") (pintype "bidirectional"))
    )
    (net (code "209") (name "unconnected-(U2A-L40N_7{slash}VREF_7-Pad12)") (class "Default")
      (node (ref "U2") (pin "12") (pinfunction "L40N_7/VREF_7_12") (pintype "bidirectional"))
    )
    (net (code "210") (name "unconnected-(U2A-L40P_6{slash}VREF_6-Pad13)") (class "Default")
      (node (ref "U2") (pin "13") (pinfunction "L40P_6/VREF_6_13") (pintype "bidirectional"))
    )
    (net (code "211") (name "unconnected-(U2A-L40P_7-Pad11)") (class "Default")
      (node (ref "U2") (pin "11") (pinfunction "L40P_7_11") (pintype "bidirectional"))
    )
    (net (code "212") (name "unconnected-(U2B-HSWAP_EN-Pad98)") (class "Default")
      (node (ref "U2") (pin "98") (pinfunction "HSWAP_EN_98") (pintype "bidirectional"))
    )
    (net (code "213") (name "unconnected-(U2B-M0-Pad25)") (class "Default")
      (node (ref "U2") (pin "25") (pinfunction "M0_25") (pintype "bidirectional"))
    )
    (net (code "214") (name "unconnected-(U2B-M1-Pad24)") (class "Default")
      (node (ref "U2") (pin "24") (pinfunction "M1_24") (pintype "bidirectional"))
    )
    (net (code "215") (name "unconnected-(U2B-M2-Pad26)") (class "Default")
      (node (ref "U2") (pin "26") (pinfunction "M2_26") (pintype "bidirectional"))
    )
    (net (code "216") (name "unconnected-(U3-D3-Pad21)") (class "Default")
      (node (ref "U3") (pin "21") (pinfunction "D3_21") (pintype "bidirectional"))
    )
    (net (code "217") (name "unconnected-(U3-D4-Pad22)") (class "Default")
      (node (ref "U3") (pin "22") (pinfunction "D4_22") (pintype "bidirectional"))
    )
    (net (code "218") (name "unconnected-(U3-D5-Pad23)") (class "Default")
      (node (ref "U3") (pin "23") (pinfunction "D5_23") (pintype "bidirectional"))
    )
    (net (code "219") (name "unconnected-(U3-D6-Pad24)") (class "Default")
      (node (ref "U3") (pin "24") (pinfunction "D6_24") (pintype "bidirectional"))
    )
    (net (code "220") (name "unconnected-(U3-D7-Pad25)") (class "Default")
      (node (ref "U3") (pin "25") (pinfunction "D7_25") (pintype "bidirectional"))
    )
    (net (code "221") (name "unconnected-(U3-E{slash}RD-Pad17)") (class "Default")
      (node (ref "U3") (pin "17") (pinfunction "E/RD_17") (pintype "input"))
    )
    (net (code "222") (name "unconnected-(U3-NC-Pad7)") (class "Default")
      (node (ref "U3") (pin "7") (pinfunction "NC_7") (pintype "no_connect"))
    )
    (net (code "223") (name "unconnected-(U3-R{slash}W-Pad16)") (class "Default")
      (node (ref "U3") (pin "16") (pinfunction "R/W_16") (pintype "input"))
    )
    (net (code "224") (name "unconnected-(U4-NC-Pad1)") (class "Default")
      (node (ref "U4") (pin "1") (pinfunction "NC_1") (pintype "bidirectional"))
    )
    (net (code "225") (name "~{OLED_CS}") (class "Default")
      (node (ref "IC2") (pin "20") (pinfunction "PA4/SPI1_NSS/USART2_CK/DAC_OUT1/ADC12_IN4_20") (pintype "bidirectional"))
      (node (ref "TP28") (pin "1") (pinfunction "P$1_1") (pintype "bidirectional"))
      (node (ref "U3") (pin "13") (pinfunction "/CS_13") (pintype "input"))
    )
    (net (code "226") (name "~{RES}") (class "Default")
      (node (ref "IC2") (pin "61") (pinfunction "PB8/TIM4_CH3/SDIO_D4/I2C1_SCL/CAN_RX/FT_61") (pintype "bidirectional"))
      (node (ref "TP29") (pin "1") (pinfunction "P$1_1") (pintype "bidirectional"))
      (node (ref "U3") (pin "14") (pinfunction "/RES_14") (pintype "input"))
    )
    (net (code "227") (name "~{SD_CS{slash}JTAG_TDI}") (class "Default")
      (node (ref "IC2") (pin "50") (pinfunction "PA15/JTDI/SPI3_NSS/I2S3_WS/TIM2_CH1_ETR/SPI1_NSS_50") (pintype "input"))
      (node (ref "JP4") (pin "2") (pinfunction "2_2") (pintype "passive"))
      (node (ref "R64") (pin "1") (pinfunction "1_1") (pintype "passive"))
      (node (ref "U4") (pin "2") (pinfunction "CS_2") (pintype "bidirectional"))
    )
  )
)
